# LED-plus-SHIM.net
KiCad netlist of a schematic drawn in EAGLE
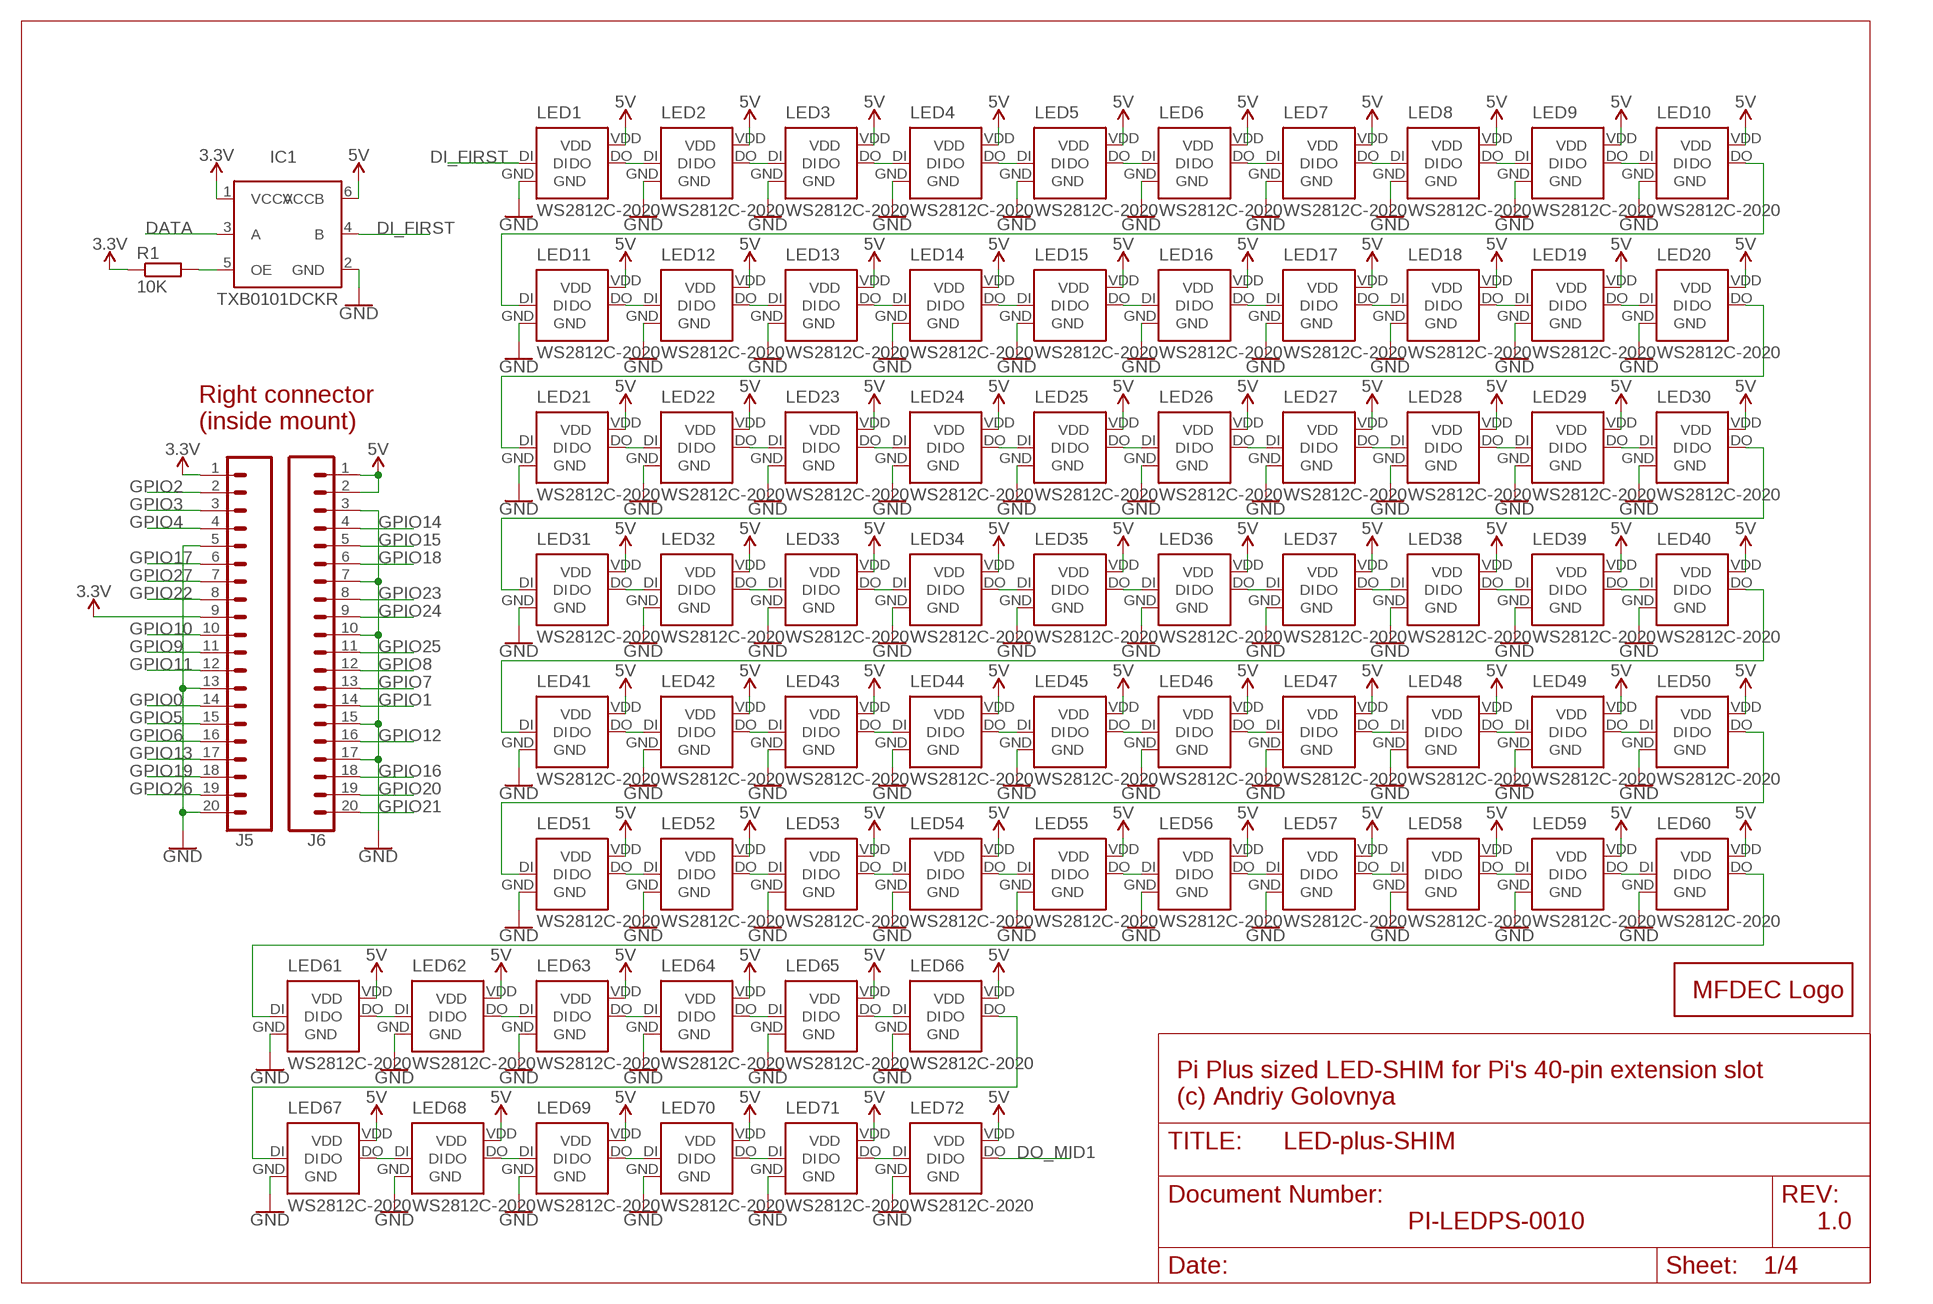
[diagram p0: schematic, sheet 1]
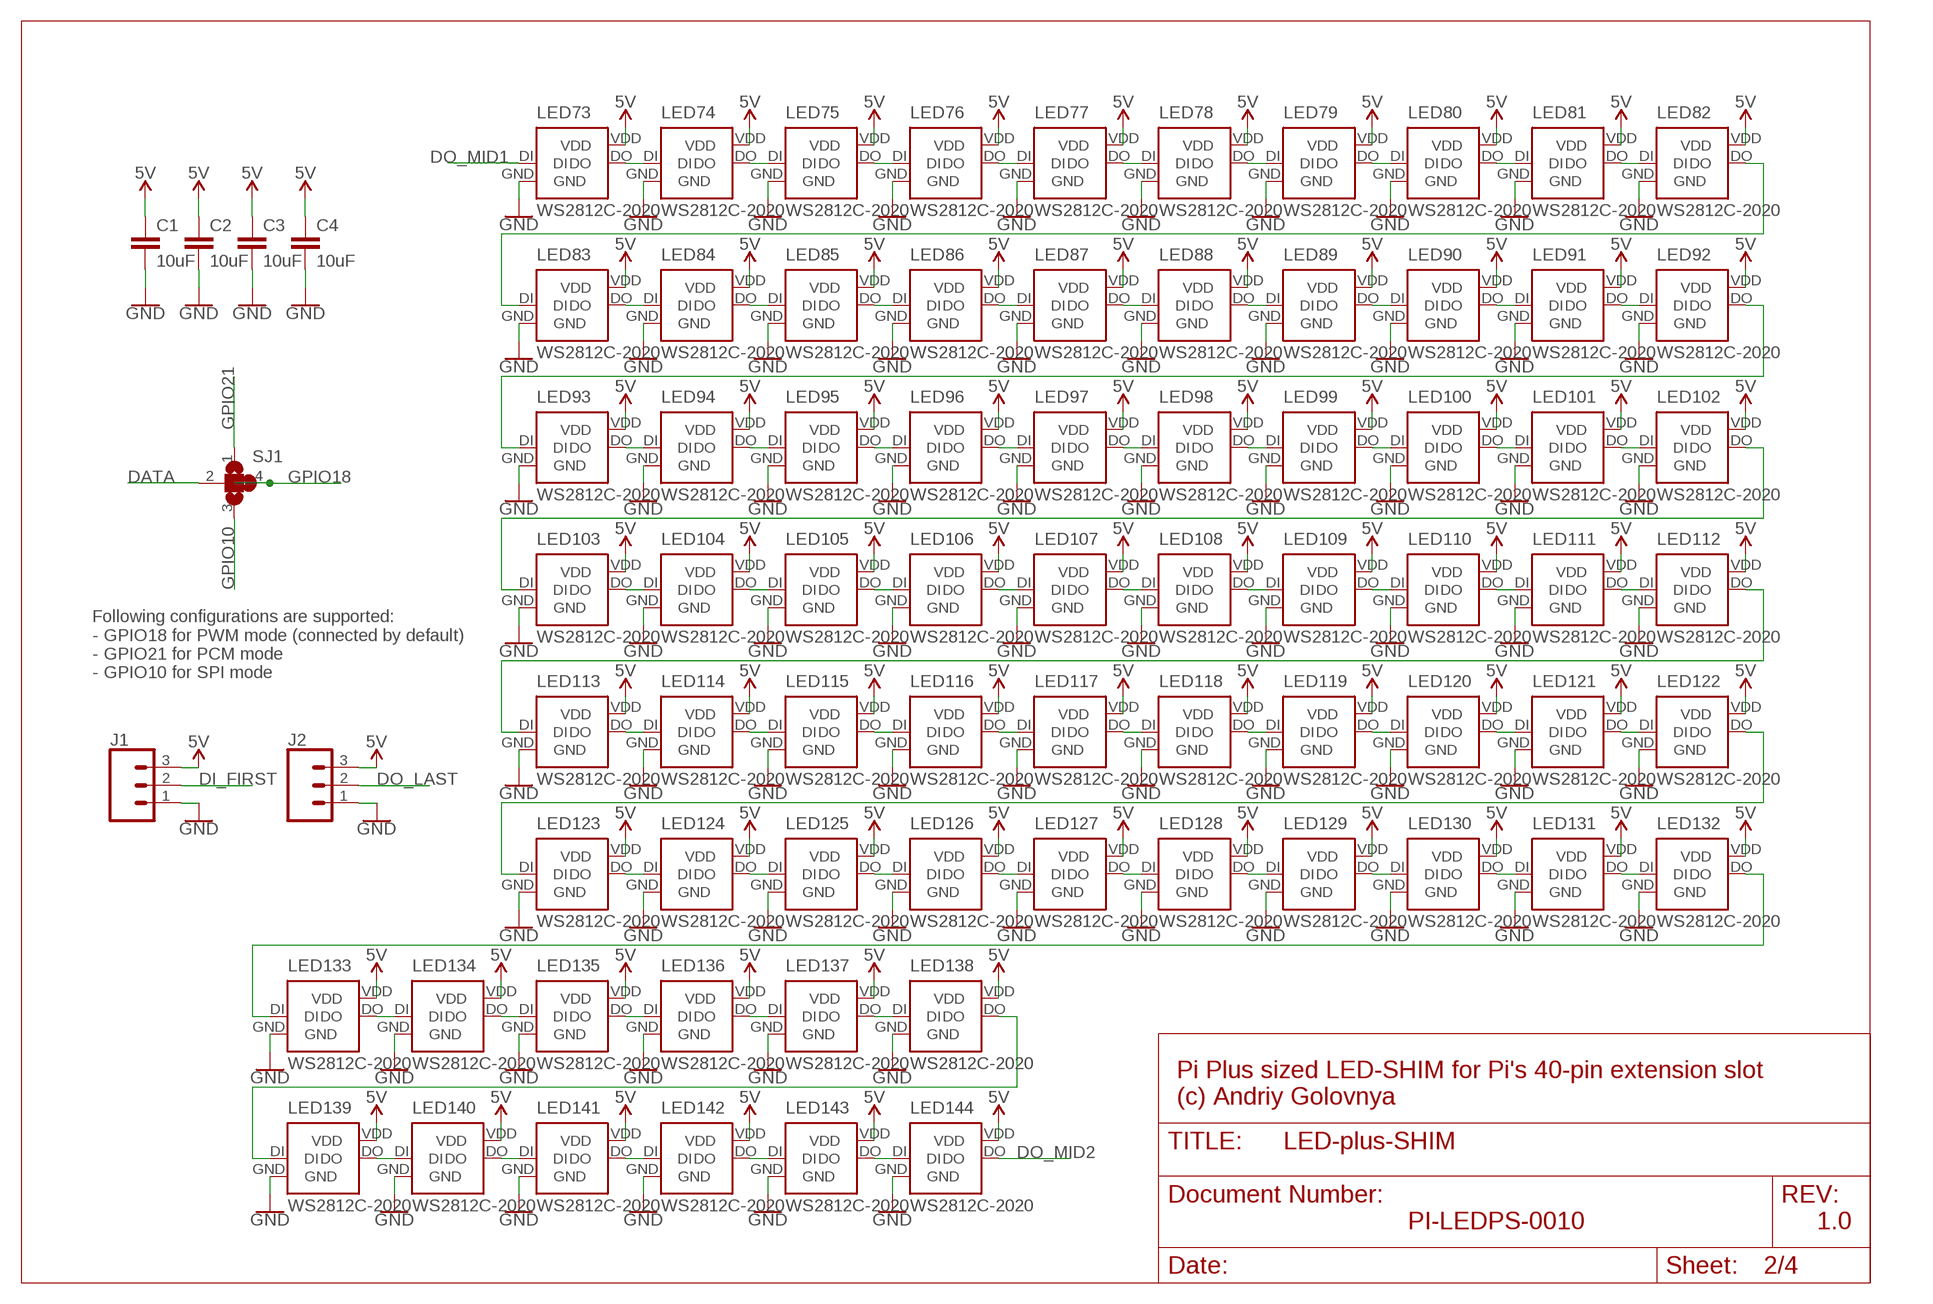
[diagram p1: schematic, sheet 2]
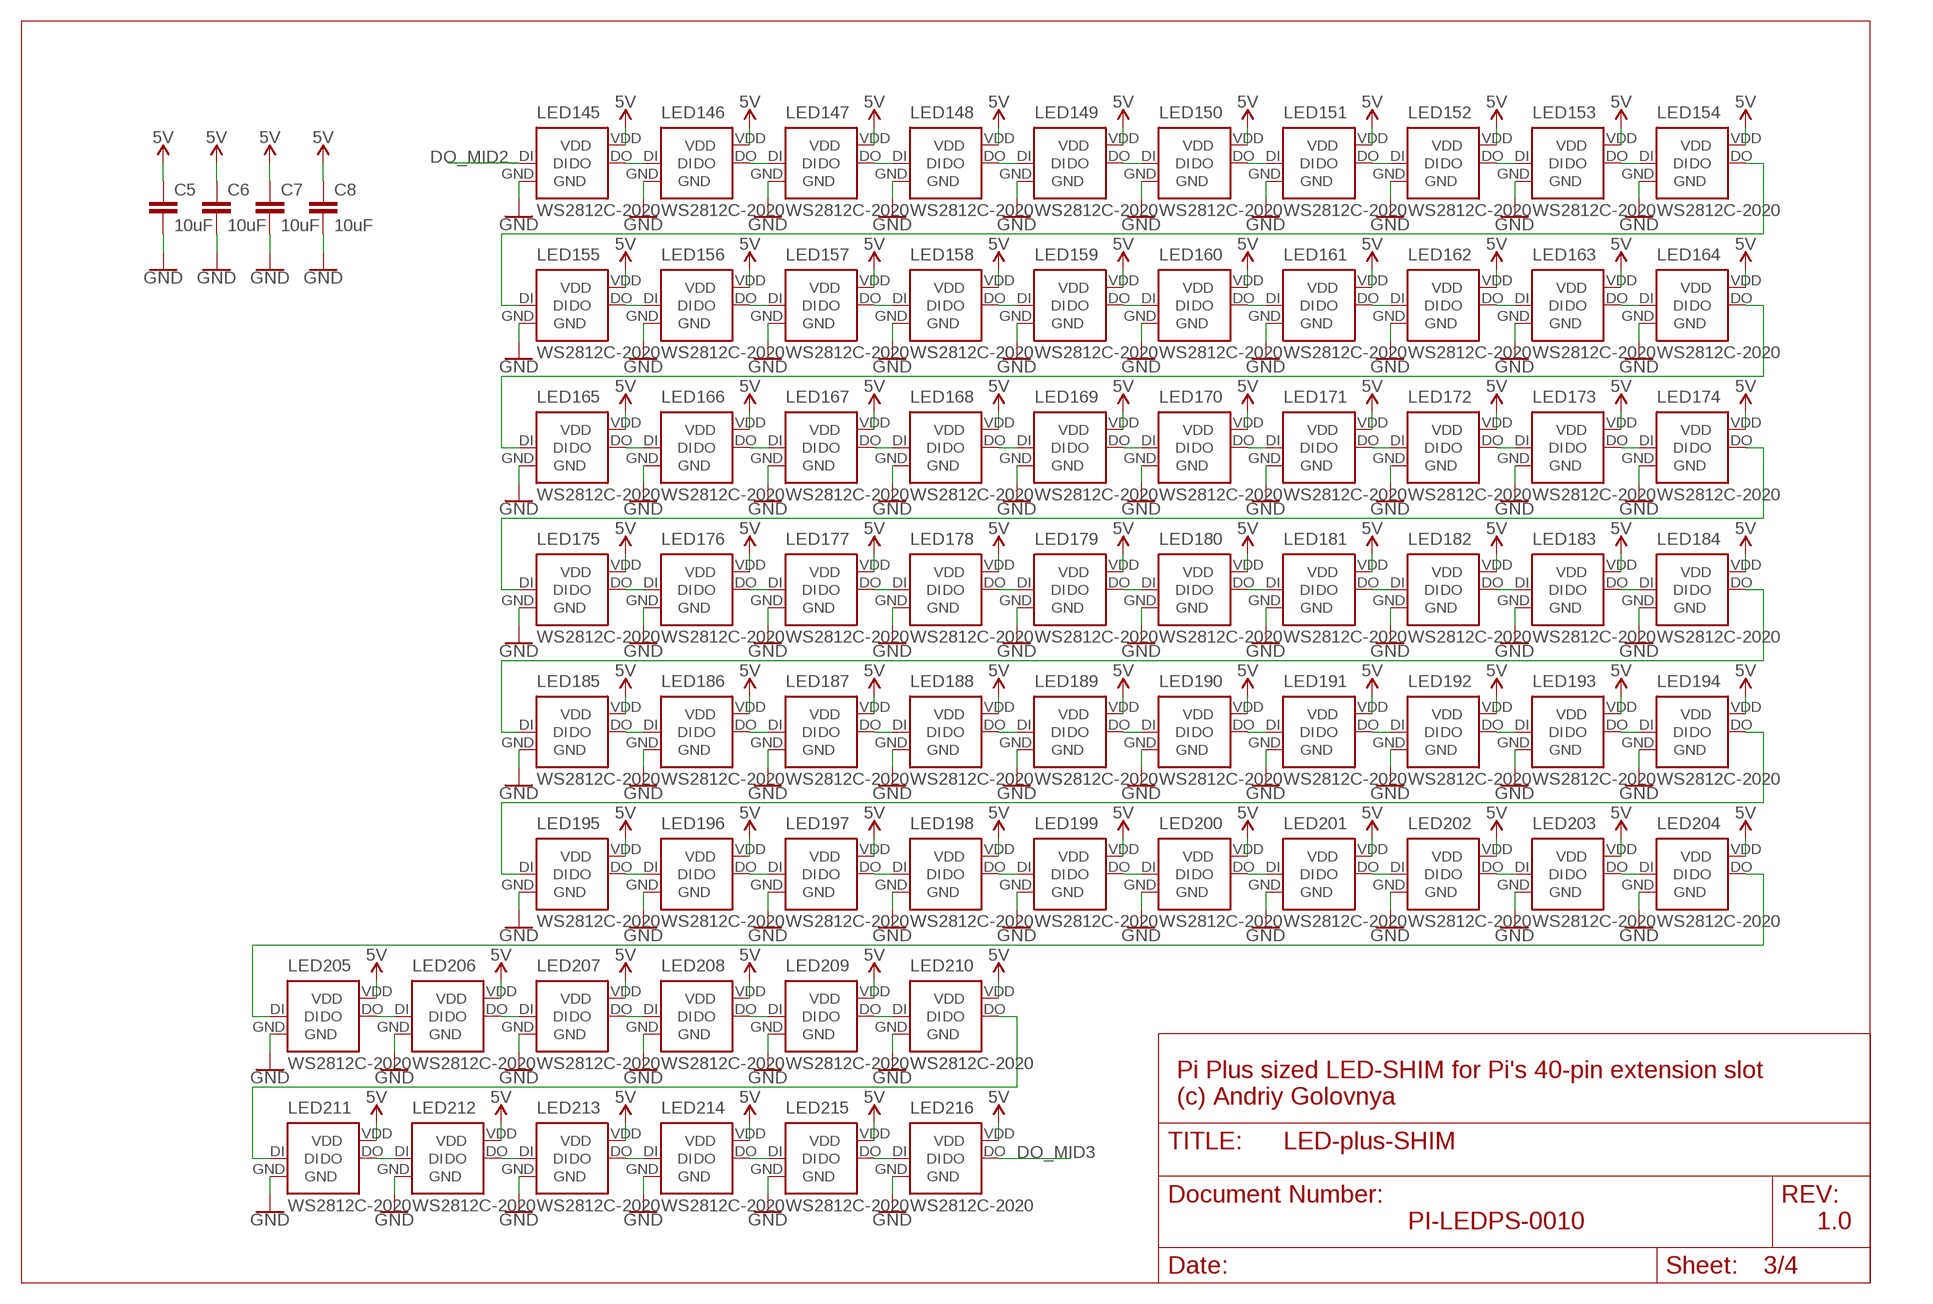
[diagram p2: schematic, sheet 3]
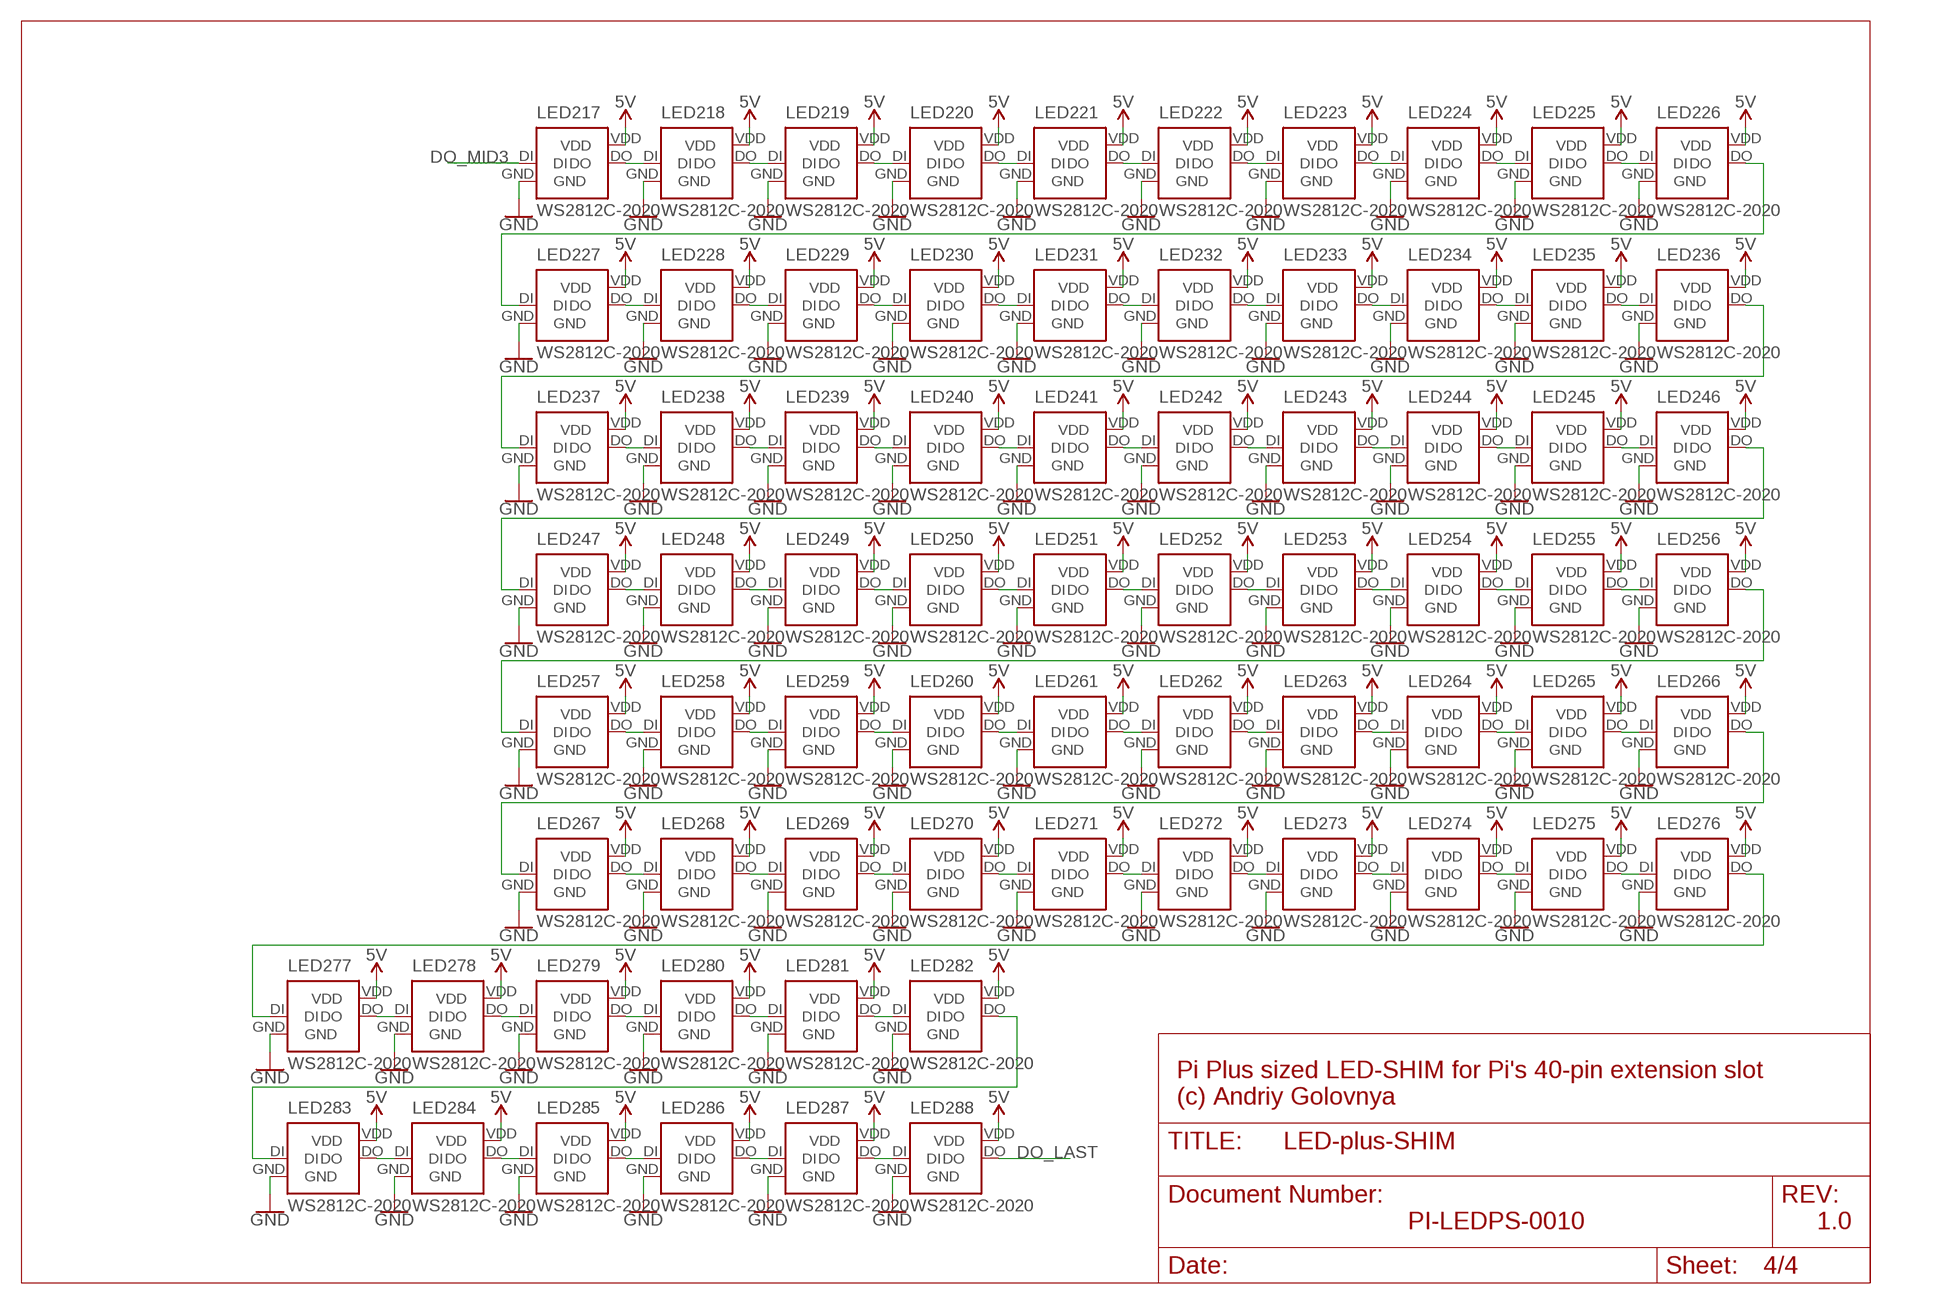
[diagram p3: schematic, sheet 4]

(export (version "E")
  (design (tool "Eeschema 10.0.6"))
  (components
    (comp (ref "IC1")
      (value "TXB0101DCKR")
      (footprint "eagle-import:SOT65P210X110-6N")
      (libsource (lib "eagle-import") (part "TXB0101DCKR"))
    )
    (comp (ref "J5")
      (value "CONN_20LOCK")
      (footprint "eagle-import:1X20_LOCK")
      (libsource (lib "eagle-import") (part "CONN_20LOCK"))
    )
    (comp (ref "J6")
      (value "CONN_20LOCK")
      (footprint "eagle-import:1X20_LOCK")
      (libsource (lib "eagle-import") (part "CONN_20LOCK"))
    )
    (comp (ref "LED1")
      (value "WS2812C-2020")
      (footprint "eagle-import:WS2812X-2020")
      (libsource (lib "eagle-import") (part "WS2812C-2020"))
    )
    (comp (ref "LED2")
      (value "WS2812C-2020")
      (footprint "eagle-import:WS2812X-2020")
      (libsource (lib "eagle-import") (part "WS2812C-2020"))
    )
    (comp (ref "LED3")
      (value "WS2812C-2020")
      (footprint "eagle-import:WS2812X-2020")
      (libsource (lib "eagle-import") (part "WS2812C-2020"))
    )
    (comp (ref "LED4")
      (value "WS2812C-2020")
      (footprint "eagle-import:WS2812X-2020")
      (libsource (lib "eagle-import") (part "WS2812C-2020"))
    )
    (comp (ref "LED5")
      (value "WS2812C-2020")
      (footprint "eagle-import:WS2812X-2020")
      (libsource (lib "eagle-import") (part "WS2812C-2020"))
    )
    (comp (ref "LED6")
      (value "WS2812C-2020")
      (footprint "eagle-import:WS2812X-2020")
      (libsource (lib "eagle-import") (part "WS2812C-2020"))
    )
    (comp (ref "LED7")
      (value "WS2812C-2020")
      (footprint "eagle-import:WS2812X-2020")
      (libsource (lib "eagle-import") (part "WS2812C-2020"))
    )
    (comp (ref "LED8")
      (value "WS2812C-2020")
      (footprint "eagle-import:WS2812X-2020")
      (libsource (lib "eagle-import") (part "WS2812C-2020"))
    )
    (comp (ref "LED9")
      (value "WS2812C-2020")
      (footprint "eagle-import:WS2812X-2020")
      (libsource (lib "eagle-import") (part "WS2812C-2020"))
    )
    (comp (ref "LED10")
      (value "WS2812C-2020")
      (footprint "eagle-import:WS2812X-2020")
      (libsource (lib "eagle-import") (part "WS2812C-2020"))
    )
    (comp (ref "LED11")
      (value "WS2812C-2020")
      (footprint "eagle-import:WS2812X-2020")
      (libsource (lib "eagle-import") (part "WS2812C-2020"))
    )
    (comp (ref "LED12")
      (value "WS2812C-2020")
      (footprint "eagle-import:WS2812X-2020")
      (libsource (lib "eagle-import") (part "WS2812C-2020"))
    )
    (comp (ref "LED13")
      (value "WS2812C-2020")
      (footprint "eagle-import:WS2812X-2020")
      (libsource (lib "eagle-import") (part "WS2812C-2020"))
    )
    (comp (ref "LED14")
      (value "WS2812C-2020")
      (footprint "eagle-import:WS2812X-2020")
      (libsource (lib "eagle-import") (part "WS2812C-2020"))
    )
    (comp (ref "LED15")
      (value "WS2812C-2020")
      (footprint "eagle-import:WS2812X-2020")
      (libsource (lib "eagle-import") (part "WS2812C-2020"))
    )
    (comp (ref "LED16")
      (value "WS2812C-2020")
      (footprint "eagle-import:WS2812X-2020")
      (libsource (lib "eagle-import") (part "WS2812C-2020"))
    )
    (comp (ref "LED17")
      (value "WS2812C-2020")
      (footprint "eagle-import:WS2812X-2020")
      (libsource (lib "eagle-import") (part "WS2812C-2020"))
    )
    (comp (ref "LED18")
      (value "WS2812C-2020")
      (footprint "eagle-import:WS2812X-2020")
      (libsource (lib "eagle-import") (part "WS2812C-2020"))
    )
    (comp (ref "LED19")
      (value "WS2812C-2020")
      (footprint "eagle-import:WS2812X-2020")
      (libsource (lib "eagle-import") (part "WS2812C-2020"))
    )
    (comp (ref "LED20")
      (value "WS2812C-2020")
      (footprint "eagle-import:WS2812X-2020")
      (libsource (lib "eagle-import") (part "WS2812C-2020"))
    )
    (comp (ref "LED21")
      (value "WS2812C-2020")
      (footprint "eagle-import:WS2812X-2020")
      (libsource (lib "eagle-import") (part "WS2812C-2020"))
    )
    (comp (ref "LED22")
      (value "WS2812C-2020")
      (footprint "eagle-import:WS2812X-2020")
      (libsource (lib "eagle-import") (part "WS2812C-2020"))
    )
    (comp (ref "LED23")
      (value "WS2812C-2020")
      (footprint "eagle-import:WS2812X-2020")
      (libsource (lib "eagle-import") (part "WS2812C-2020"))
    )
    (comp (ref "LED24")
      (value "WS2812C-2020")
      (footprint "eagle-import:WS2812X-2020")
      (libsource (lib "eagle-import") (part "WS2812C-2020"))
    )
    (comp (ref "LED25")
      (value "WS2812C-2020")
      (footprint "eagle-import:WS2812X-2020")
      (libsource (lib "eagle-import") (part "WS2812C-2020"))
    )
    (comp (ref "LED26")
      (value "WS2812C-2020")
      (footprint "eagle-import:WS2812X-2020")
      (libsource (lib "eagle-import") (part "WS2812C-2020"))
    )
    (comp (ref "LED27")
      (value "WS2812C-2020")
      (footprint "eagle-import:WS2812X-2020")
      (libsource (lib "eagle-import") (part "WS2812C-2020"))
    )
    (comp (ref "LED28")
      (value "WS2812C-2020")
      (footprint "eagle-import:WS2812X-2020")
      (libsource (lib "eagle-import") (part "WS2812C-2020"))
    )
    (comp (ref "LED29")
      (value "WS2812C-2020")
      (footprint "eagle-import:WS2812X-2020")
      (libsource (lib "eagle-import") (part "WS2812C-2020"))
    )
    (comp (ref "LED30")
      (value "WS2812C-2020")
      (footprint "eagle-import:WS2812X-2020")
      (libsource (lib "eagle-import") (part "WS2812C-2020"))
    )
    (comp (ref "LED31")
      (value "WS2812C-2020")
      (footprint "eagle-import:WS2812X-2020")
      (libsource (lib "eagle-import") (part "WS2812C-2020"))
    )
    (comp (ref "LED32")
      (value "WS2812C-2020")
      (footprint "eagle-import:WS2812X-2020")
      (libsource (lib "eagle-import") (part "WS2812C-2020"))
    )
    (comp (ref "LED33")
      (value "WS2812C-2020")
      (footprint "eagle-import:WS2812X-2020")
      (libsource (lib "eagle-import") (part "WS2812C-2020"))
    )
    (comp (ref "LED34")
      (value "WS2812C-2020")
      (footprint "eagle-import:WS2812X-2020")
      (libsource (lib "eagle-import") (part "WS2812C-2020"))
    )
    (comp (ref "LED35")
      (value "WS2812C-2020")
      (footprint "eagle-import:WS2812X-2020")
      (libsource (lib "eagle-import") (part "WS2812C-2020"))
    )
    (comp (ref "LED36")
      (value "WS2812C-2020")
      (footprint "eagle-import:WS2812X-2020")
      (libsource (lib "eagle-import") (part "WS2812C-2020"))
    )
    (comp (ref "LED37")
      (value "WS2812C-2020")
      (footprint "eagle-import:WS2812X-2020")
      (libsource (lib "eagle-import") (part "WS2812C-2020"))
    )
    (comp (ref "LED38")
      (value "WS2812C-2020")
      (footprint "eagle-import:WS2812X-2020")
      (libsource (lib "eagle-import") (part "WS2812C-2020"))
    )
    (comp (ref "LED39")
      (value "WS2812C-2020")
      (footprint "eagle-import:WS2812X-2020")
      (libsource (lib "eagle-import") (part "WS2812C-2020"))
    )
    (comp (ref "LED40")
      (value "WS2812C-2020")
      (footprint "eagle-import:WS2812X-2020")
      (libsource (lib "eagle-import") (part "WS2812C-2020"))
    )
    (comp (ref "LED41")
      (value "WS2812C-2020")
      (footprint "eagle-import:WS2812X-2020")
      (libsource (lib "eagle-import") (part "WS2812C-2020"))
    )
    (comp (ref "LED42")
      (value "WS2812C-2020")
      (footprint "eagle-import:WS2812X-2020")
      (libsource (lib "eagle-import") (part "WS2812C-2020"))
    )
    (comp (ref "LED43")
      (value "WS2812C-2020")
      (footprint "eagle-import:WS2812X-2020")
      (libsource (lib "eagle-import") (part "WS2812C-2020"))
    )
    (comp (ref "LED44")
      (value "WS2812C-2020")
      (footprint "eagle-import:WS2812X-2020")
      (libsource (lib "eagle-import") (part "WS2812C-2020"))
    )
    (comp (ref "LED45")
      (value "WS2812C-2020")
      (footprint "eagle-import:WS2812X-2020")
      (libsource (lib "eagle-import") (part "WS2812C-2020"))
    )
    (comp (ref "LED46")
      (value "WS2812C-2020")
      (footprint "eagle-import:WS2812X-2020")
      (libsource (lib "eagle-import") (part "WS2812C-2020"))
    )
    (comp (ref "LED47")
      (value "WS2812C-2020")
      (footprint "eagle-import:WS2812X-2020")
      (libsource (lib "eagle-import") (part "WS2812C-2020"))
    )
    (comp (ref "LED48")
      (value "WS2812C-2020")
      (footprint "eagle-import:WS2812X-2020")
      (libsource (lib "eagle-import") (part "WS2812C-2020"))
    )
    (comp (ref "LED49")
      (value "WS2812C-2020")
      (footprint "eagle-import:WS2812X-2020")
      (libsource (lib "eagle-import") (part "WS2812C-2020"))
    )
    (comp (ref "LED50")
      (value "WS2812C-2020")
      (footprint "eagle-import:WS2812X-2020")
      (libsource (lib "eagle-import") (part "WS2812C-2020"))
    )
    (comp (ref "LED51")
      (value "WS2812C-2020")
      (footprint "eagle-import:WS2812X-2020")
      (libsource (lib "eagle-import") (part "WS2812C-2020"))
    )
    (comp (ref "LED52")
      (value "WS2812C-2020")
      (footprint "eagle-import:WS2812X-2020")
      (libsource (lib "eagle-import") (part "WS2812C-2020"))
    )
    (comp (ref "LED53")
      (value "WS2812C-2020")
      (footprint "eagle-import:WS2812X-2020")
      (libsource (lib "eagle-import") (part "WS2812C-2020"))
    )
    (comp (ref "LED54")
      (value "WS2812C-2020")
      (footprint "eagle-import:WS2812X-2020")
      (libsource (lib "eagle-import") (part "WS2812C-2020"))
    )
    (comp (ref "LED55")
      (value "WS2812C-2020")
      (footprint "eagle-import:WS2812X-2020")
      (libsource (lib "eagle-import") (part "WS2812C-2020"))
    )
    (comp (ref "LED56")
      (value "WS2812C-2020")
      (footprint "eagle-import:WS2812X-2020")
      (libsource (lib "eagle-import") (part "WS2812C-2020"))
    )
    (comp (ref "LED57")
      (value "WS2812C-2020")
      (footprint "eagle-import:WS2812X-2020")
      (libsource (lib "eagle-import") (part "WS2812C-2020"))
    )
    (comp (ref "LED58")
      (value "WS2812C-2020")
      (footprint "eagle-import:WS2812X-2020")
      (libsource (lib "eagle-import") (part "WS2812C-2020"))
    )
    (comp (ref "LED59")
      (value "WS2812C-2020")
      (footprint "eagle-import:WS2812X-2020")
      (libsource (lib "eagle-import") (part "WS2812C-2020"))
    )
    (comp (ref "LED60")
      (value "WS2812C-2020")
      (footprint "eagle-import:WS2812X-2020")
      (libsource (lib "eagle-import") (part "WS2812C-2020"))
    )
    (comp (ref "LED61")
      (value "WS2812C-2020")
      (footprint "eagle-import:WS2812X-2020")
      (libsource (lib "eagle-import") (part "WS2812C-2020"))
    )
    (comp (ref "LED62")
      (value "WS2812C-2020")
      (footprint "eagle-import:WS2812X-2020")
      (libsource (lib "eagle-import") (part "WS2812C-2020"))
    )
    (comp (ref "LED63")
      (value "WS2812C-2020")
      (footprint "eagle-import:WS2812X-2020")
      (libsource (lib "eagle-import") (part "WS2812C-2020"))
    )
    (comp (ref "LED64")
      (value "WS2812C-2020")
      (footprint "eagle-import:WS2812X-2020")
      (libsource (lib "eagle-import") (part "WS2812C-2020"))
    )
    (comp (ref "LED65")
      (value "WS2812C-2020")
      (footprint "eagle-import:WS2812X-2020")
      (libsource (lib "eagle-import") (part "WS2812C-2020"))
    )
    (comp (ref "LED66")
      (value "WS2812C-2020")
      (footprint "eagle-import:WS2812X-2020")
      (libsource (lib "eagle-import") (part "WS2812C-2020"))
    )
    (comp (ref "LED67")
      (value "WS2812C-2020")
      (footprint "eagle-import:WS2812X-2020")
      (libsource (lib "eagle-import") (part "WS2812C-2020"))
    )
    (comp (ref "LED68")
      (value "WS2812C-2020")
      (footprint "eagle-import:WS2812X-2020")
      (libsource (lib "eagle-import") (part "WS2812C-2020"))
    )
    (comp (ref "LED69")
      (value "WS2812C-2020")
      (footprint "eagle-import:WS2812X-2020")
      (libsource (lib "eagle-import") (part "WS2812C-2020"))
    )
    (comp (ref "LED70")
      (value "WS2812C-2020")
      (footprint "eagle-import:WS2812X-2020")
      (libsource (lib "eagle-import") (part "WS2812C-2020"))
    )
    (comp (ref "LED71")
      (value "WS2812C-2020")
      (footprint "eagle-import:WS2812X-2020")
      (libsource (lib "eagle-import") (part "WS2812C-2020"))
    )
    (comp (ref "LED72")
      (value "WS2812C-2020")
      (footprint "eagle-import:WS2812X-2020")
      (libsource (lib "eagle-import") (part "WS2812C-2020"))
    )
    (comp (ref "LOGO1")
      (value "MFDECLOGO_L_30MM")
      (footprint "eagle-import:MFDEC_L_30MM")
      (libsource (lib "eagle-import") (part "MFDECLOGO_L_30MM"))
    )
    (comp (ref "R1")
      (value "10K")
      (footprint "eagle-import:R0402")
      (libsource (lib "eagle-import") (part "R-EU_R0402"))
    )
    (comp (ref "C1")
      (value "10uF")
      (footprint "eagle-import:C0805")
      (libsource (lib "eagle-import") (part "C-EUC0805"))
    )
    (comp (ref "C2")
      (value "10uF")
      (footprint "eagle-import:C0805")
      (libsource (lib "eagle-import") (part "C-EUC0805"))
    )
    (comp (ref "C3")
      (value "10uF")
      (footprint "eagle-import:C0805")
      (libsource (lib "eagle-import") (part "C-EUC0805"))
    )
    (comp (ref "C4")
      (value "10uF")
      (footprint "eagle-import:C0805")
      (libsource (lib "eagle-import") (part "C-EUC0805"))
    )
    (comp (ref "J1")
      (value "CONN_03")
      (footprint "eagle-import:1X03")
      (libsource (lib "eagle-import") (part "CONN_03"))
    )
    (comp (ref "J2")
      (value "CONN_03")
      (footprint "eagle-import:1X03")
      (libsource (lib "eagle-import") (part "CONN_03"))
    )
    (comp (ref "LED73")
      (value "WS2812C-2020")
      (footprint "eagle-import:WS2812X-2020")
      (libsource (lib "eagle-import") (part "WS2812C-2020"))
    )
    (comp (ref "LED74")
      (value "WS2812C-2020")
      (footprint "eagle-import:WS2812X-2020")
      (libsource (lib "eagle-import") (part "WS2812C-2020"))
    )
    (comp (ref "LED75")
      (value "WS2812C-2020")
      (footprint "eagle-import:WS2812X-2020")
      (libsource (lib "eagle-import") (part "WS2812C-2020"))
    )
    (comp (ref "LED76")
      (value "WS2812C-2020")
      (footprint "eagle-import:WS2812X-2020")
      (libsource (lib "eagle-import") (part "WS2812C-2020"))
    )
    (comp (ref "LED77")
      (value "WS2812C-2020")
      (footprint "eagle-import:WS2812X-2020")
      (libsource (lib "eagle-import") (part "WS2812C-2020"))
    )
    (comp (ref "LED78")
      (value "WS2812C-2020")
      (footprint "eagle-import:WS2812X-2020")
      (libsource (lib "eagle-import") (part "WS2812C-2020"))
    )
    (comp (ref "LED79")
      (value "WS2812C-2020")
      (footprint "eagle-import:WS2812X-2020")
      (libsource (lib "eagle-import") (part "WS2812C-2020"))
    )
    (comp (ref "LED80")
      (value "WS2812C-2020")
      (footprint "eagle-import:WS2812X-2020")
      (libsource (lib "eagle-import") (part "WS2812C-2020"))
    )
    (comp (ref "LED81")
      (value "WS2812C-2020")
      (footprint "eagle-import:WS2812X-2020")
      (libsource (lib "eagle-import") (part "WS2812C-2020"))
    )
    (comp (ref "LED82")
      (value "WS2812C-2020")
      (footprint "eagle-import:WS2812X-2020")
      (libsource (lib "eagle-import") (part "WS2812C-2020"))
    )
    (comp (ref "LED83")
      (value "WS2812C-2020")
      (footprint "eagle-import:WS2812X-2020")
      (libsource (lib "eagle-import") (part "WS2812C-2020"))
    )
    (comp (ref "LED84")
      (value "WS2812C-2020")
      (footprint "eagle-import:WS2812X-2020")
      (libsource (lib "eagle-import") (part "WS2812C-2020"))
    )
    (comp (ref "LED85")
      (value "WS2812C-2020")
      (footprint "eagle-import:WS2812X-2020")
      (libsource (lib "eagle-import") (part "WS2812C-2020"))
    )
    (comp (ref "LED86")
      (value "WS2812C-2020")
      (footprint "eagle-import:WS2812X-2020")
      (libsource (lib "eagle-import") (part "WS2812C-2020"))
    )
    (comp (ref "LED87")
      (value "WS2812C-2020")
      (footprint "eagle-import:WS2812X-2020")
      (libsource (lib "eagle-import") (part "WS2812C-2020"))
    )
    (comp (ref "LED88")
      (value "WS2812C-2020")
      (footprint "eagle-import:WS2812X-2020")
      (libsource (lib "eagle-import") (part "WS2812C-2020"))
    )
    (comp (ref "LED89")
      (value "WS2812C-2020")
      (footprint "eagle-import:WS2812X-2020")
      (libsource (lib "eagle-import") (part "WS2812C-2020"))
    )
    (comp (ref "LED90")
      (value "WS2812C-2020")
      (footprint "eagle-import:WS2812X-2020")
      (libsource (lib "eagle-import") (part "WS2812C-2020"))
    )
    (comp (ref "LED91")
      (value "WS2812C-2020")
      (footprint "eagle-import:WS2812X-2020")
      (libsource (lib "eagle-import") (part "WS2812C-2020"))
    )
    (comp (ref "LED92")
      (value "WS2812C-2020")
      (footprint "eagle-import:WS2812X-2020")
      (libsource (lib "eagle-import") (part "WS2812C-2020"))
    )
    (comp (ref "LED93")
      (value "WS2812C-2020")
      (footprint "eagle-import:WS2812X-2020")
      (libsource (lib "eagle-import") (part "WS2812C-2020"))
    )
    (comp (ref "LED94")
      (value "WS2812C-2020")
      (footprint "eagle-import:WS2812X-2020")
      (libsource (lib "eagle-import") (part "WS2812C-2020"))
    )
    (comp (ref "LED95")
      (value "WS2812C-2020")
      (footprint "eagle-import:WS2812X-2020")
      (libsource (lib "eagle-import") (part "WS2812C-2020"))
    )
    (comp (ref "LED96")
      (value "WS2812C-2020")
      (footprint "eagle-import:WS2812X-2020")
      (libsource (lib "eagle-import") (part "WS2812C-2020"))
    )
    (comp (ref "LED97")
      (value "WS2812C-2020")
      (footprint "eagle-import:WS2812X-2020")
      (libsource (lib "eagle-import") (part "WS2812C-2020"))
    )
    (comp (ref "LED98")
      (value "WS2812C-2020")
      (footprint "eagle-import:WS2812X-2020")
      (libsource (lib "eagle-import") (part "WS2812C-2020"))
    )
    (comp (ref "LED99")
      (value "WS2812C-2020")
      (footprint "eagle-import:WS2812X-2020")
      (libsource (lib "eagle-import") (part "WS2812C-2020"))
    )
    (comp (ref "LED100")
      (value "WS2812C-2020")
      (footprint "eagle-import:WS2812X-2020")
      (libsource (lib "eagle-import") (part "WS2812C-2020"))
    )
    (comp (ref "LED101")
      (value "WS2812C-2020")
      (footprint "eagle-import:WS2812X-2020")
      (libsource (lib "eagle-import") (part "WS2812C-2020"))
    )
    (comp (ref "LED102")
      (value "WS2812C-2020")
      (footprint "eagle-import:WS2812X-2020")
      (libsource (lib "eagle-import") (part "WS2812C-2020"))
    )
    (comp (ref "LED103")
      (value "WS2812C-2020")
      (footprint "eagle-import:WS2812X-2020")
      (libsource (lib "eagle-import") (part "WS2812C-2020"))
    )
    (comp (ref "LED104")
      (value "WS2812C-2020")
      (footprint "eagle-import:WS2812X-2020")
      (libsource (lib "eagle-import") (part "WS2812C-2020"))
    )
    (comp (ref "LED105")
      (value "WS2812C-2020")
      (footprint "eagle-import:WS2812X-2020")
      (libsource (lib "eagle-import") (part "WS2812C-2020"))
    )
    (comp (ref "LED106")
      (value "WS2812C-2020")
      (footprint "eagle-import:WS2812X-2020")
      (libsource (lib "eagle-import") (part "WS2812C-2020"))
    )
    (comp (ref "LED107")
      (value "WS2812C-2020")
      (footprint "eagle-import:WS2812X-2020")
      (libsource (lib "eagle-import") (part "WS2812C-2020"))
    )
    (comp (ref "LED108")
      (value "WS2812C-2020")
      (footprint "eagle-import:WS2812X-2020")
      (libsource (lib "eagle-import") (part "WS2812C-2020"))
    )
    (comp (ref "LED109")
      (value "WS2812C-2020")
      (footprint "eagle-import:WS2812X-2020")
      (libsource (lib "eagle-import") (part "WS2812C-2020"))
    )
    (comp (ref "LED110")
      (value "WS2812C-2020")
      (footprint "eagle-import:WS2812X-2020")
      (libsource (lib "eagle-import") (part "WS2812C-2020"))
    )
    (comp (ref "LED111")
      (value "WS2812C-2020")
      (footprint "eagle-import:WS2812X-2020")
      (libsource (lib "eagle-import") (part "WS2812C-2020"))
    )
    (comp (ref "LED112")
      (value "WS2812C-2020")
      (footprint "eagle-import:WS2812X-2020")
      (libsource (lib "eagle-import") (part "WS2812C-2020"))
    )
    (comp (ref "LED113")
      (value "WS2812C-2020")
      (footprint "eagle-import:WS2812X-2020")
      (libsource (lib "eagle-import") (part "WS2812C-2020"))
    )
    (comp (ref "LED114")
      (value "WS2812C-2020")
      (footprint "eagle-import:WS2812X-2020")
      (libsource (lib "eagle-import") (part "WS2812C-2020"))
    )
    (comp (ref "LED115")
      (value "WS2812C-2020")
      (footprint "eagle-import:WS2812X-2020")
      (libsource (lib "eagle-import") (part "WS2812C-2020"))
    )
    (comp (ref "LED116")
      (value "WS2812C-2020")
      (footprint "eagle-import:WS2812X-2020")
      (libsource (lib "eagle-import") (part "WS2812C-2020"))
    )
    (comp (ref "LED117")
      (value "WS2812C-2020")
      (footprint "eagle-import:WS2812X-2020")
      (libsource (lib "eagle-import") (part "WS2812C-2020"))
    )
    (comp (ref "LED118")
      (value "WS2812C-2020")
      (footprint "eagle-import:WS2812X-2020")
      (libsource (lib "eagle-import") (part "WS2812C-2020"))
    )
    (comp (ref "LED119")
      (value "WS2812C-2020")
      (footprint "eagle-import:WS2812X-2020")
      (libsource (lib "eagle-import") (part "WS2812C-2020"))
    )
    (comp (ref "LED120")
      (value "WS2812C-2020")
      (footprint "eagle-import:WS2812X-2020")
      (libsource (lib "eagle-import") (part "WS2812C-2020"))
    )
    (comp (ref "LED121")
      (value "WS2812C-2020")
      (footprint "eagle-import:WS2812X-2020")
      (libsource (lib "eagle-import") (part "WS2812C-2020"))
    )
    (comp (ref "LED122")
      (value "WS2812C-2020")
      (footprint "eagle-import:WS2812X-2020")
      (libsource (lib "eagle-import") (part "WS2812C-2020"))
    )
    (comp (ref "LED123")
      (value "WS2812C-2020")
      (footprint "eagle-import:WS2812X-2020")
      (libsource (lib "eagle-import") (part "WS2812C-2020"))
    )
    (comp (ref "LED124")
      (value "WS2812C-2020")
      (footprint "eagle-import:WS2812X-2020")
      (libsource (lib "eagle-import") (part "WS2812C-2020"))
    )
    (comp (ref "LED125")
      (value "WS2812C-2020")
      (footprint "eagle-import:WS2812X-2020")
      (libsource (lib "eagle-import") (part "WS2812C-2020"))
    )
    (comp (ref "LED126")
      (value "WS2812C-2020")
      (footprint "eagle-import:WS2812X-2020")
      (libsource (lib "eagle-import") (part "WS2812C-2020"))
    )
    (comp (ref "LED127")
      (value "WS2812C-2020")
      (footprint "eagle-import:WS2812X-2020")
      (libsource (lib "eagle-import") (part "WS2812C-2020"))
    )
    (comp (ref "LED128")
      (value "WS2812C-2020")
      (footprint "eagle-import:WS2812X-2020")
      (libsource (lib "eagle-import") (part "WS2812C-2020"))
    )
    (comp (ref "LED129")
      (value "WS2812C-2020")
      (footprint "eagle-import:WS2812X-2020")
      (libsource (lib "eagle-import") (part "WS2812C-2020"))
    )
    (comp (ref "LED130")
      (value "WS2812C-2020")
      (footprint "eagle-import:WS2812X-2020")
      (libsource (lib "eagle-import") (part "WS2812C-2020"))
    )
    (comp (ref "LED131")
      (value "WS2812C-2020")
      (footprint "eagle-import:WS2812X-2020")
      (libsource (lib "eagle-import") (part "WS2812C-2020"))
    )
    (comp (ref "LED132")
      (value "WS2812C-2020")
      (footprint "eagle-import:WS2812X-2020")
      (libsource (lib "eagle-import") (part "WS2812C-2020"))
    )
    (comp (ref "LED133")
      (value "WS2812C-2020")
      (footprint "eagle-import:WS2812X-2020")
      (libsource (lib "eagle-import") (part "WS2812C-2020"))
    )
    (comp (ref "LED134")
      (value "WS2812C-2020")
      (footprint "eagle-import:WS2812X-2020")
      (libsource (lib "eagle-import") (part "WS2812C-2020"))
    )
    (comp (ref "LED135")
      (value "WS2812C-2020")
      (footprint "eagle-import:WS2812X-2020")
      (libsource (lib "eagle-import") (part "WS2812C-2020"))
    )
    (comp (ref "LED136")
      (value "WS2812C-2020")
      (footprint "eagle-import:WS2812X-2020")
      (libsource (lib "eagle-import") (part "WS2812C-2020"))
    )
    (comp (ref "LED137")
      (value "WS2812C-2020")
      (footprint "eagle-import:WS2812X-2020")
      (libsource (lib "eagle-import") (part "WS2812C-2020"))
    )
    (comp (ref "LED138")
      (value "WS2812C-2020")
      (footprint "eagle-import:WS2812X-2020")
      (libsource (lib "eagle-import") (part "WS2812C-2020"))
    )
    (comp (ref "LED139")
      (value "WS2812C-2020")
      (footprint "eagle-import:WS2812X-2020")
      (libsource (lib "eagle-import") (part "WS2812C-2020"))
    )
    (comp (ref "LED140")
      (value "WS2812C-2020")
      (footprint "eagle-import:WS2812X-2020")
      (libsource (lib "eagle-import") (part "WS2812C-2020"))
    )
    (comp (ref "LED141")
      (value "WS2812C-2020")
      (footprint "eagle-import:WS2812X-2020")
      (libsource (lib "eagle-import") (part "WS2812C-2020"))
    )
    (comp (ref "LED142")
      (value "WS2812C-2020")
      (footprint "eagle-import:WS2812X-2020")
      (libsource (lib "eagle-import") (part "WS2812C-2020"))
    )
    (comp (ref "LED143")
      (value "WS2812C-2020")
      (footprint "eagle-import:WS2812X-2020")
      (libsource (lib "eagle-import") (part "WS2812C-2020"))
    )
    (comp (ref "LED144")
      (value "WS2812C-2020")
      (footprint "eagle-import:WS2812X-2020")
      (libsource (lib "eagle-import") (part "WS2812C-2020"))
    )
    (comp (ref "SJ1")
      (value "SJ3")
      (footprint "eagle-import:SJ_3")
      (libsource (lib "eagle-import") (part "SJ3"))
    )
    (comp (ref "C5")
      (value "10uF")
      (footprint "eagle-import:C0805")
      (libsource (lib "eagle-import") (part "C-EUC0805"))
    )
    (comp (ref "C6")
      (value "10uF")
      (footprint "eagle-import:C0805")
      (libsource (lib "eagle-import") (part "C-EUC0805"))
    )
    (comp (ref "C7")
      (value "10uF")
      (footprint "eagle-import:C0805")
      (libsource (lib "eagle-import") (part "C-EUC0805"))
    )
    (comp (ref "C8")
      (value "10uF")
      (footprint "eagle-import:C0805")
      (libsource (lib "eagle-import") (part "C-EUC0805"))
    )
    (comp (ref "LED145")
      (value "WS2812C-2020")
      (footprint "eagle-import:WS2812X-2020")
      (libsource (lib "eagle-import") (part "WS2812C-2020"))
    )
    (comp (ref "LED146")
      (value "WS2812C-2020")
      (footprint "eagle-import:WS2812X-2020")
      (libsource (lib "eagle-import") (part "WS2812C-2020"))
    )
    (comp (ref "LED147")
      (value "WS2812C-2020")
      (footprint "eagle-import:WS2812X-2020")
      (libsource (lib "eagle-import") (part "WS2812C-2020"))
    )
    (comp (ref "LED148")
      (value "WS2812C-2020")
      (footprint "eagle-import:WS2812X-2020")
      (libsource (lib "eagle-import") (part "WS2812C-2020"))
    )
    (comp (ref "LED149")
      (value "WS2812C-2020")
      (footprint "eagle-import:WS2812X-2020")
      (libsource (lib "eagle-import") (part "WS2812C-2020"))
    )
    (comp (ref "LED150")
      (value "WS2812C-2020")
      (footprint "eagle-import:WS2812X-2020")
      (libsource (lib "eagle-import") (part "WS2812C-2020"))
    )
    (comp (ref "LED151")
      (value "WS2812C-2020")
      (footprint "eagle-import:WS2812X-2020")
      (libsource (lib "eagle-import") (part "WS2812C-2020"))
    )
    (comp (ref "LED152")
      (value "WS2812C-2020")
      (footprint "eagle-import:WS2812X-2020")
      (libsource (lib "eagle-import") (part "WS2812C-2020"))
    )
    (comp (ref "LED153")
      (value "WS2812C-2020")
      (footprint "eagle-import:WS2812X-2020")
      (libsource (lib "eagle-import") (part "WS2812C-2020"))
    )
    (comp (ref "LED154")
      (value "WS2812C-2020")
      (footprint "eagle-import:WS2812X-2020")
      (libsource (lib "eagle-import") (part "WS2812C-2020"))
    )
    (comp (ref "LED155")
      (value "WS2812C-2020")
      (footprint "eagle-import:WS2812X-2020")
      (libsource (lib "eagle-import") (part "WS2812C-2020"))
    )
    (comp (ref "LED156")
      (value "WS2812C-2020")
      (footprint "eagle-import:WS2812X-2020")
      (libsource (lib "eagle-import") (part "WS2812C-2020"))
    )
    (comp (ref "LED157")
      (value "WS2812C-2020")
      (footprint "eagle-import:WS2812X-2020")
      (libsource (lib "eagle-import") (part "WS2812C-2020"))
    )
    (comp (ref "LED158")
      (value "WS2812C-2020")
      (footprint "eagle-import:WS2812X-2020")
      (libsource (lib "eagle-import") (part "WS2812C-2020"))
    )
    (comp (ref "LED159")
      (value "WS2812C-2020")
      (footprint "eagle-import:WS2812X-2020")
      (libsource (lib "eagle-import") (part "WS2812C-2020"))
    )
    (comp (ref "LED160")
      (value "WS2812C-2020")
      (footprint "eagle-import:WS2812X-2020")
      (libsource (lib "eagle-import") (part "WS2812C-2020"))
    )
    (comp (ref "LED161")
      (value "WS2812C-2020")
      (footprint "eagle-import:WS2812X-2020")
      (libsource (lib "eagle-import") (part "WS2812C-2020"))
    )
    (comp (ref "LED162")
      (value "WS2812C-2020")
      (footprint "eagle-import:WS2812X-2020")
      (libsource (lib "eagle-import") (part "WS2812C-2020"))
    )
    (comp (ref "LED163")
      (value "WS2812C-2020")
      (footprint "eagle-import:WS2812X-2020")
      (libsource (lib "eagle-import") (part "WS2812C-2020"))
    )
    (comp (ref "LED164")
      (value "WS2812C-2020")
      (footprint "eagle-import:WS2812X-2020")
      (libsource (lib "eagle-import") (part "WS2812C-2020"))
    )
    (comp (ref "LED165")
      (value "WS2812C-2020")
      (footprint "eagle-import:WS2812X-2020")
      (libsource (lib "eagle-import") (part "WS2812C-2020"))
    )
    (comp (ref "LED166")
      (value "WS2812C-2020")
      (footprint "eagle-import:WS2812X-2020")
      (libsource (lib "eagle-import") (part "WS2812C-2020"))
    )
    (comp (ref "LED167")
      (value "WS2812C-2020")
      (footprint "eagle-import:WS2812X-2020")
      (libsource (lib "eagle-import") (part "WS2812C-2020"))
    )
    (comp (ref "LED168")
      (value "WS2812C-2020")
      (footprint "eagle-import:WS2812X-2020")
      (libsource (lib "eagle-import") (part "WS2812C-2020"))
    )
    (comp (ref "LED169")
      (value "WS2812C-2020")
      (footprint "eagle-import:WS2812X-2020")
      (libsource (lib "eagle-import") (part "WS2812C-2020"))
    )
    (comp (ref "LED170")
      (value "WS2812C-2020")
      (footprint "eagle-import:WS2812X-2020")
      (libsource (lib "eagle-import") (part "WS2812C-2020"))
    )
    (comp (ref "LED171")
      (value "WS2812C-2020")
      (footprint "eagle-import:WS2812X-2020")
      (libsource (lib "eagle-import") (part "WS2812C-2020"))
    )
    (comp (ref "LED172")
      (value "WS2812C-2020")
      (footprint "eagle-import:WS2812X-2020")
      (libsource (lib "eagle-import") (part "WS2812C-2020"))
    )
    (comp (ref "LED173")
      (value "WS2812C-2020")
      (footprint "eagle-import:WS2812X-2020")
      (libsource (lib "eagle-import") (part "WS2812C-2020"))
    )
    (comp (ref "LED174")
      (value "WS2812C-2020")
      (footprint "eagle-import:WS2812X-2020")
      (libsource (lib "eagle-import") (part "WS2812C-2020"))
    )
    (comp (ref "LED175")
      (value "WS2812C-2020")
      (footprint "eagle-import:WS2812X-2020")
      (libsource (lib "eagle-import") (part "WS2812C-2020"))
    )
    (comp (ref "LED176")
      (value "WS2812C-2020")
      (footprint "eagle-import:WS2812X-2020")
      (libsource (lib "eagle-import") (part "WS2812C-2020"))
    )
    (comp (ref "LED177")
      (value "WS2812C-2020")
      (footprint "eagle-import:WS2812X-2020")
      (libsource (lib "eagle-import") (part "WS2812C-2020"))
    )
    (comp (ref "LED178")
      (value "WS2812C-2020")
      (footprint "eagle-import:WS2812X-2020")
      (libsource (lib "eagle-import") (part "WS2812C-2020"))
    )
    (comp (ref "LED179")
      (value "WS2812C-2020")
      (footprint "eagle-import:WS2812X-2020")
      (libsource (lib "eagle-import") (part "WS2812C-2020"))
    )
    (comp (ref "LED180")
      (value "WS2812C-2020")
      (footprint "eagle-import:WS2812X-2020")
      (libsource (lib "eagle-import") (part "WS2812C-2020"))
    )
    (comp (ref "LED181")
      (value "WS2812C-2020")
      (footprint "eagle-import:WS2812X-2020")
      (libsource (lib "eagle-import") (part "WS2812C-2020"))
    )
    (comp (ref "LED182")
      (value "WS2812C-2020")
      (footprint "eagle-import:WS2812X-2020")
      (libsource (lib "eagle-import") (part "WS2812C-2020"))
    )
    (comp (ref "LED183")
      (value "WS2812C-2020")
      (footprint "eagle-import:WS2812X-2020")
      (libsource (lib "eagle-import") (part "WS2812C-2020"))
    )
    (comp (ref "LED184")
      (value "WS2812C-2020")
      (footprint "eagle-import:WS2812X-2020")
      (libsource (lib "eagle-import") (part "WS2812C-2020"))
    )
    (comp (ref "LED185")
      (value "WS2812C-2020")
      (footprint "eagle-import:WS2812X-2020")
      (libsource (lib "eagle-import") (part "WS2812C-2020"))
    )
    (comp (ref "LED186")
      (value "WS2812C-2020")
      (footprint "eagle-import:WS2812X-2020")
      (libsource (lib "eagle-import") (part "WS2812C-2020"))
    )
    (comp (ref "LED187")
      (value "WS2812C-2020")
      (footprint "eagle-import:WS2812X-2020")
      (libsource (lib "eagle-import") (part "WS2812C-2020"))
    )
    (comp (ref "LED188")
      (value "WS2812C-2020")
      (footprint "eagle-import:WS2812X-2020")
      (libsource (lib "eagle-import") (part "WS2812C-2020"))
    )
    (comp (ref "LED189")
      (value "WS2812C-2020")
      (footprint "eagle-import:WS2812X-2020")
      (libsource (lib "eagle-import") (part "WS2812C-2020"))
    )
    (comp (ref "LED190")
      (value "WS2812C-2020")
      (footprint "eagle-import:WS2812X-2020")
      (libsource (lib "eagle-import") (part "WS2812C-2020"))
    )
    (comp (ref "LED191")
      (value "WS2812C-2020")
      (footprint "eagle-import:WS2812X-2020")
      (libsource (lib "eagle-import") (part "WS2812C-2020"))
    )
    (comp (ref "LED192")
      (value "WS2812C-2020")
      (footprint "eagle-import:WS2812X-2020")
      (libsource (lib "eagle-import") (part "WS2812C-2020"))
    )
    (comp (ref "LED193")
      (value "WS2812C-2020")
      (footprint "eagle-import:WS2812X-2020")
      (libsource (lib "eagle-import") (part "WS2812C-2020"))
    )
    (comp (ref "LED194")
      (value "WS2812C-2020")
      (footprint "eagle-import:WS2812X-2020")
      (libsource (lib "eagle-import") (part "WS2812C-2020"))
    )
    (comp (ref "LED195")
      (value "WS2812C-2020")
      (footprint "eagle-import:WS2812X-2020")
      (libsource (lib "eagle-import") (part "WS2812C-2020"))
    )
    (comp (ref "LED196")
      (value "WS2812C-2020")
      (footprint "eagle-import:WS2812X-2020")
      (libsource (lib "eagle-import") (part "WS2812C-2020"))
    )
    (comp (ref "LED197")
      (value "WS2812C-2020")
      (footprint "eagle-import:WS2812X-2020")
      (libsource (lib "eagle-import") (part "WS2812C-2020"))
    )
    (comp (ref "LED198")
      (value "WS2812C-2020")
      (footprint "eagle-import:WS2812X-2020")
      (libsource (lib "eagle-import") (part "WS2812C-2020"))
    )
    (comp (ref "LED199")
      (value "WS2812C-2020")
      (footprint "eagle-import:WS2812X-2020")
      (libsource (lib "eagle-import") (part "WS2812C-2020"))
    )
    (comp (ref "LED200")
      (value "WS2812C-2020")
      (footprint "eagle-import:WS2812X-2020")
      (libsource (lib "eagle-import") (part "WS2812C-2020"))
    )
    (comp (ref "LED201")
      (value "WS2812C-2020")
      (footprint "eagle-import:WS2812X-2020")
      (libsource (lib "eagle-import") (part "WS2812C-2020"))
    )
    (comp (ref "LED202")
      (value "WS2812C-2020")
      (footprint "eagle-import:WS2812X-2020")
      (libsource (lib "eagle-import") (part "WS2812C-2020"))
    )
    (comp (ref "LED203")
      (value "WS2812C-2020")
      (footprint "eagle-import:WS2812X-2020")
      (libsource (lib "eagle-import") (part "WS2812C-2020"))
    )
    (comp (ref "LED204")
      (value "WS2812C-2020")
      (footprint "eagle-import:WS2812X-2020")
      (libsource (lib "eagle-import") (part "WS2812C-2020"))
    )
    (comp (ref "LED205")
      (value "WS2812C-2020")
      (footprint "eagle-import:WS2812X-2020")
      (libsource (lib "eagle-import") (part "WS2812C-2020"))
    )
    (comp (ref "LED206")
      (value "WS2812C-2020")
      (footprint "eagle-import:WS2812X-2020")
      (libsource (lib "eagle-import") (part "WS2812C-2020"))
    )
    (comp (ref "LED207")
      (value "WS2812C-2020")
      (footprint "eagle-import:WS2812X-2020")
      (libsource (lib "eagle-import") (part "WS2812C-2020"))
    )
    (comp (ref "LED208")
      (value "WS2812C-2020")
      (footprint "eagle-import:WS2812X-2020")
      (libsource (lib "eagle-import") (part "WS2812C-2020"))
    )
    (comp (ref "LED209")
      (value "WS2812C-2020")
      (footprint "eagle-import:WS2812X-2020")
      (libsource (lib "eagle-import") (part "WS2812C-2020"))
    )
    (comp (ref "LED210")
      (value "WS2812C-2020")
      (footprint "eagle-import:WS2812X-2020")
      (libsource (lib "eagle-import") (part "WS2812C-2020"))
    )
    (comp (ref "LED211")
      (value "WS2812C-2020")
      (footprint "eagle-import:WS2812X-2020")
      (libsource (lib "eagle-import") (part "WS2812C-2020"))
    )
    (comp (ref "LED212")
      (value "WS2812C-2020")
      (footprint "eagle-import:WS2812X-2020")
      (libsource (lib "eagle-import") (part "WS2812C-2020"))
    )
    (comp (ref "LED213")
      (value "WS2812C-2020")
      (footprint "eagle-import:WS2812X-2020")
      (libsource (lib "eagle-import") (part "WS2812C-2020"))
    )
    (comp (ref "LED214")
      (value "WS2812C-2020")
      (footprint "eagle-import:WS2812X-2020")
      (libsource (lib "eagle-import") (part "WS2812C-2020"))
    )
    (comp (ref "LED215")
      (value "WS2812C-2020")
      (footprint "eagle-import:WS2812X-2020")
      (libsource (lib "eagle-import") (part "WS2812C-2020"))
    )
    (comp (ref "LED216")
      (value "WS2812C-2020")
      (footprint "eagle-import:WS2812X-2020")
      (libsource (lib "eagle-import") (part "WS2812C-2020"))
    )
    (comp (ref "LED217")
      (value "WS2812C-2020")
      (footprint "eagle-import:WS2812X-2020")
      (libsource (lib "eagle-import") (part "WS2812C-2020"))
    )
    (comp (ref "LED218")
      (value "WS2812C-2020")
      (footprint "eagle-import:WS2812X-2020")
      (libsource (lib "eagle-import") (part "WS2812C-2020"))
    )
    (comp (ref "LED219")
      (value "WS2812C-2020")
      (footprint "eagle-import:WS2812X-2020")
      (libsource (lib "eagle-import") (part "WS2812C-2020"))
    )
    (comp (ref "LED220")
      (value "WS2812C-2020")
      (footprint "eagle-import:WS2812X-2020")
      (libsource (lib "eagle-import") (part "WS2812C-2020"))
    )
    (comp (ref "LED221")
      (value "WS2812C-2020")
      (footprint "eagle-import:WS2812X-2020")
      (libsource (lib "eagle-import") (part "WS2812C-2020"))
    )
    (comp (ref "LED222")
      (value "WS2812C-2020")
      (footprint "eagle-import:WS2812X-2020")
      (libsource (lib "eagle-import") (part "WS2812C-2020"))
    )
    (comp (ref "LED223")
      (value "WS2812C-2020")
      (footprint "eagle-import:WS2812X-2020")
      (libsource (lib "eagle-import") (part "WS2812C-2020"))
    )
    (comp (ref "LED224")
      (value "WS2812C-2020")
      (footprint "eagle-import:WS2812X-2020")
      (libsource (lib "eagle-import") (part "WS2812C-2020"))
    )
    (comp (ref "LED225")
      (value "WS2812C-2020")
      (footprint "eagle-import:WS2812X-2020")
      (libsource (lib "eagle-import") (part "WS2812C-2020"))
    )
    (comp (ref "LED226")
      (value "WS2812C-2020")
      (footprint "eagle-import:WS2812X-2020")
      (libsource (lib "eagle-import") (part "WS2812C-2020"))
    )
    (comp (ref "LED227")
      (value "WS2812C-2020")
      (footprint "eagle-import:WS2812X-2020")
      (libsource (lib "eagle-import") (part "WS2812C-2020"))
    )
    (comp (ref "LED228")
      (value "WS2812C-2020")
      (footprint "eagle-import:WS2812X-2020")
      (libsource (lib "eagle-import") (part "WS2812C-2020"))
    )
    (comp (ref "LED229")
      (value "WS2812C-2020")
      (footprint "eagle-import:WS2812X-2020")
      (libsource (lib "eagle-import") (part "WS2812C-2020"))
    )
    (comp (ref "LED230")
      (value "WS2812C-2020")
      (footprint "eagle-import:WS2812X-2020")
      (libsource (lib "eagle-import") (part "WS2812C-2020"))
    )
    (comp (ref "LED231")
      (value "WS2812C-2020")
      (footprint "eagle-import:WS2812X-2020")
      (libsource (lib "eagle-import") (part "WS2812C-2020"))
    )
    (comp (ref "LED232")
      (value "WS2812C-2020")
      (footprint "eagle-import:WS2812X-2020")
      (libsource (lib "eagle-import") (part "WS2812C-2020"))
    )
    (comp (ref "LED233")
      (value "WS2812C-2020")
      (footprint "eagle-import:WS2812X-2020")
      (libsource (lib "eagle-import") (part "WS2812C-2020"))
    )
    (comp (ref "LED234")
      (value "WS2812C-2020")
      (footprint "eagle-import:WS2812X-2020")
      (libsource (lib "eagle-import") (part "WS2812C-2020"))
    )
    (comp (ref "LED235")
      (value "WS2812C-2020")
      (footprint "eagle-import:WS2812X-2020")
      (libsource (lib "eagle-import") (part "WS2812C-2020"))
    )
    (comp (ref "LED236")
      (value "WS2812C-2020")
      (footprint "eagle-import:WS2812X-2020")
      (libsource (lib "eagle-import") (part "WS2812C-2020"))
    )
    (comp (ref "LED237")
      (value "WS2812C-2020")
      (footprint "eagle-import:WS2812X-2020")
      (libsource (lib "eagle-import") (part "WS2812C-2020"))
    )
    (comp (ref "LED238")
      (value "WS2812C-2020")
      (footprint "eagle-import:WS2812X-2020")
      (libsource (lib "eagle-import") (part "WS2812C-2020"))
    )
    (comp (ref "LED239")
      (value "WS2812C-2020")
      (footprint "eagle-import:WS2812X-2020")
      (libsource (lib "eagle-import") (part "WS2812C-2020"))
    )
    (comp (ref "LED240")
      (value "WS2812C-2020")
      (footprint "eagle-import:WS2812X-2020")
      (libsource (lib "eagle-import") (part "WS2812C-2020"))
    )
    (comp (ref "LED241")
      (value "WS2812C-2020")
      (footprint "eagle-import:WS2812X-2020")
      (libsource (lib "eagle-import") (part "WS2812C-2020"))
    )
    (comp (ref "LED242")
      (value "WS2812C-2020")
      (footprint "eagle-import:WS2812X-2020")
      (libsource (lib "eagle-import") (part "WS2812C-2020"))
    )
    (comp (ref "LED243")
      (value "WS2812C-2020")
      (footprint "eagle-import:WS2812X-2020")
      (libsource (lib "eagle-import") (part "WS2812C-2020"))
    )
    (comp (ref "LED244")
      (value "WS2812C-2020")
      (footprint "eagle-import:WS2812X-2020")
      (libsource (lib "eagle-import") (part "WS2812C-2020"))
    )
    (comp (ref "LED245")
      (value "WS2812C-2020")
      (footprint "eagle-import:WS2812X-2020")
      (libsource (lib "eagle-import") (part "WS2812C-2020"))
    )
    (comp (ref "LED246")
      (value "WS2812C-2020")
      (footprint "eagle-import:WS2812X-2020")
      (libsource (lib "eagle-import") (part "WS2812C-2020"))
    )
    (comp (ref "LED247")
      (value "WS2812C-2020")
      (footprint "eagle-import:WS2812X-2020")
      (libsource (lib "eagle-import") (part "WS2812C-2020"))
    )
    (comp (ref "LED248")
      (value "WS2812C-2020")
      (footprint "eagle-import:WS2812X-2020")
      (libsource (lib "eagle-import") (part "WS2812C-2020"))
    )
    (comp (ref "LED249")
      (value "WS2812C-2020")
      (footprint "eagle-import:WS2812X-2020")
      (libsource (lib "eagle-import") (part "WS2812C-2020"))
    )
    (comp (ref "LED250")
      (value "WS2812C-2020")
      (footprint "eagle-import:WS2812X-2020")
      (libsource (lib "eagle-import") (part "WS2812C-2020"))
    )
    (comp (ref "LED251")
      (value "WS2812C-2020")
      (footprint "eagle-import:WS2812X-2020")
      (libsource (lib "eagle-import") (part "WS2812C-2020"))
    )
    (comp (ref "LED252")
      (value "WS2812C-2020")
      (footprint "eagle-import:WS2812X-2020")
      (libsource (lib "eagle-import") (part "WS2812C-2020"))
    )
    (comp (ref "LED253")
      (value "WS2812C-2020")
      (footprint "eagle-import:WS2812X-2020")
      (libsource (lib "eagle-import") (part "WS2812C-2020"))
    )
    (comp (ref "LED254")
      (value "WS2812C-2020")
      (footprint "eagle-import:WS2812X-2020")
      (libsource (lib "eagle-import") (part "WS2812C-2020"))
    )
    (comp (ref "LED255")
      (value "WS2812C-2020")
      (footprint "eagle-import:WS2812X-2020")
      (libsource (lib "eagle-import") (part "WS2812C-2020"))
    )
    (comp (ref "LED256")
      (value "WS2812C-2020")
      (footprint "eagle-import:WS2812X-2020")
      (libsource (lib "eagle-import") (part "WS2812C-2020"))
    )
    (comp (ref "LED257")
      (value "WS2812C-2020")
      (footprint "eagle-import:WS2812X-2020")
      (libsource (lib "eagle-import") (part "WS2812C-2020"))
    )
    (comp (ref "LED258")
      (value "WS2812C-2020")
      (footprint "eagle-import:WS2812X-2020")
      (libsource (lib "eagle-import") (part "WS2812C-2020"))
    )
    (comp (ref "LED259")
      (value "WS2812C-2020")
      (footprint "eagle-import:WS2812X-2020")
      (libsource (lib "eagle-import") (part "WS2812C-2020"))
    )
    (comp (ref "LED260")
      (value "WS2812C-2020")
      (footprint "eagle-import:WS2812X-2020")
      (libsource (lib "eagle-import") (part "WS2812C-2020"))
    )
    (comp (ref "LED261")
      (value "WS2812C-2020")
      (footprint "eagle-import:WS2812X-2020")
      (libsource (lib "eagle-import") (part "WS2812C-2020"))
    )
    (comp (ref "LED262")
      (value "WS2812C-2020")
      (footprint "eagle-import:WS2812X-2020")
      (libsource (lib "eagle-import") (part "WS2812C-2020"))
    )
    (comp (ref "LED263")
      (value "WS2812C-2020")
      (footprint "eagle-import:WS2812X-2020")
      (libsource (lib "eagle-import") (part "WS2812C-2020"))
    )
    (comp (ref "LED264")
      (value "WS2812C-2020")
      (footprint "eagle-import:WS2812X-2020")
      (libsource (lib "eagle-import") (part "WS2812C-2020"))
    )
    (comp (ref "LED265")
      (value "WS2812C-2020")
      (footprint "eagle-import:WS2812X-2020")
      (libsource (lib "eagle-import") (part "WS2812C-2020"))
    )
    (comp (ref "LED266")
      (value "WS2812C-2020")
      (footprint "eagle-import:WS2812X-2020")
      (libsource (lib "eagle-import") (part "WS2812C-2020"))
    )
    (comp (ref "LED267")
      (value "WS2812C-2020")
      (footprint "eagle-import:WS2812X-2020")
      (libsource (lib "eagle-import") (part "WS2812C-2020"))
    )
    (comp (ref "LED268")
      (value "WS2812C-2020")
      (footprint "eagle-import:WS2812X-2020")
      (libsource (lib "eagle-import") (part "WS2812C-2020"))
    )
    (comp (ref "LED269")
      (value "WS2812C-2020")
      (footprint "eagle-import:WS2812X-2020")
      (libsource (lib "eagle-import") (part "WS2812C-2020"))
    )
    (comp (ref "LED270")
      (value "WS2812C-2020")
      (footprint "eagle-import:WS2812X-2020")
      (libsource (lib "eagle-import") (part "WS2812C-2020"))
    )
    (comp (ref "LED271")
      (value "WS2812C-2020")
      (footprint "eagle-import:WS2812X-2020")
      (libsource (lib "eagle-import") (part "WS2812C-2020"))
    )
    (comp (ref "LED272")
      (value "WS2812C-2020")
      (footprint "eagle-import:WS2812X-2020")
      (libsource (lib "eagle-import") (part "WS2812C-2020"))
    )
    (comp (ref "LED273")
      (value "WS2812C-2020")
      (footprint "eagle-import:WS2812X-2020")
      (libsource (lib "eagle-import") (part "WS2812C-2020"))
    )
    (comp (ref "LED274")
      (value "WS2812C-2020")
      (footprint "eagle-import:WS2812X-2020")
      (libsource (lib "eagle-import") (part "WS2812C-2020"))
    )
    (comp (ref "LED275")
      (value "WS2812C-2020")
      (footprint "eagle-import:WS2812X-2020")
      (libsource (lib "eagle-import") (part "WS2812C-2020"))
    )
    (comp (ref "LED276")
      (value "WS2812C-2020")
      (footprint "eagle-import:WS2812X-2020")
      (libsource (lib "eagle-import") (part "WS2812C-2020"))
    )
    (comp (ref "LED277")
      (value "WS2812C-2020")
      (footprint "eagle-import:WS2812X-2020")
      (libsource (lib "eagle-import") (part "WS2812C-2020"))
    )
    (comp (ref "LED278")
      (value "WS2812C-2020")
      (footprint "eagle-import:WS2812X-2020")
      (libsource (lib "eagle-import") (part "WS2812C-2020"))
    )
    (comp (ref "LED279")
      (value "WS2812C-2020")
      (footprint "eagle-import:WS2812X-2020")
      (libsource (lib "eagle-import") (part "WS2812C-2020"))
    )
    (comp (ref "LED280")
      (value "WS2812C-2020")
      (footprint "eagle-import:WS2812X-2020")
      (libsource (lib "eagle-import") (part "WS2812C-2020"))
    )
    (comp (ref "LED281")
      (value "WS2812C-2020")
      (footprint "eagle-import:WS2812X-2020")
      (libsource (lib "eagle-import") (part "WS2812C-2020"))
    )
    (comp (ref "LED282")
      (value "WS2812C-2020")
      (footprint "eagle-import:WS2812X-2020")
      (libsource (lib "eagle-import") (part "WS2812C-2020"))
    )
    (comp (ref "LED283")
      (value "WS2812C-2020")
      (footprint "eagle-import:WS2812X-2020")
      (libsource (lib "eagle-import") (part "WS2812C-2020"))
    )
    (comp (ref "LED284")
      (value "WS2812C-2020")
      (footprint "eagle-import:WS2812X-2020")
      (libsource (lib "eagle-import") (part "WS2812C-2020"))
    )
    (comp (ref "LED285")
      (value "WS2812C-2020")
      (footprint "eagle-import:WS2812X-2020")
      (libsource (lib "eagle-import") (part "WS2812C-2020"))
    )
    (comp (ref "LED286")
      (value "WS2812C-2020")
      (footprint "eagle-import:WS2812X-2020")
      (libsource (lib "eagle-import") (part "WS2812C-2020"))
    )
    (comp (ref "LED287")
      (value "WS2812C-2020")
      (footprint "eagle-import:WS2812X-2020")
      (libsource (lib "eagle-import") (part "WS2812C-2020"))
    )
    (comp (ref "LED288")
      (value "WS2812C-2020")
      (footprint "eagle-import:WS2812X-2020")
      (libsource (lib "eagle-import") (part "WS2812C-2020"))
    )
  )
  (nets
    (net (code "1") (name "3.3V") (class "Default")
      (node (ref "IC1") (pin "1") (pinfunction "VCCA_1") (pintype "power_in"))
      (node (ref "J5") (pin "1") (pinfunction "1_1") (pintype "passive"))
      (node (ref "J5") (pin "9") (pinfunction "9_9") (pintype "passive"))
      (node (ref "R1") (pin "1") (pinfunction "1_1") (pintype "passive"))
    )
    (net (code "2") (name "5V") (class "Default")
      (node (ref "C1") (pin "1") (pinfunction "1_1") (pintype "passive"))
      (node (ref "C2") (pin "1") (pinfunction "1_1") (pintype "passive"))
      (node (ref "C3") (pin "1") (pinfunction "1_1") (pintype "passive"))
      (node (ref "C4") (pin "1") (pinfunction "1_1") (pintype "passive"))
      (node (ref "C5") (pin "1") (pinfunction "1_1") (pintype "passive"))
      (node (ref "C6") (pin "1") (pinfunction "1_1") (pintype "passive"))
      (node (ref "C7") (pin "1") (pinfunction "1_1") (pintype "passive"))
      (node (ref "C8") (pin "1") (pinfunction "1_1") (pintype "passive"))
      (node (ref "IC1") (pin "6") (pinfunction "VCCB_6") (pintype "power_in"))
      (node (ref "J1") (pin "3") (pinfunction "3_3") (pintype "passive"))
      (node (ref "J2") (pin "3") (pinfunction "3_3") (pintype "passive"))
      (node (ref "J6") (pin "1") (pinfunction "1_1") (pintype "passive"))
      (node (ref "J6") (pin "2") (pinfunction "2_2") (pintype "passive"))
      (node (ref "LED1") (pin "VDD") (pinfunction "VDD_VDD") (pintype "power_in"))
      (node (ref "LED10") (pin "VDD") (pinfunction "VDD_VDD") (pintype "power_in"))
      (node (ref "LED100") (pin "VDD") (pinfunction "VDD_VDD") (pintype "power_in"))
      (node (ref "LED101") (pin "VDD") (pinfunction "VDD_VDD") (pintype "power_in"))
      (node (ref "LED102") (pin "VDD") (pinfunction "VDD_VDD") (pintype "power_in"))
      (node (ref "LED103") (pin "VDD") (pinfunction "VDD_VDD") (pintype "power_in"))
      (node (ref "LED104") (pin "VDD") (pinfunction "VDD_VDD") (pintype "power_in"))
      (node (ref "LED105") (pin "VDD") (pinfunction "VDD_VDD") (pintype "power_in"))
      (node (ref "LED106") (pin "VDD") (pinfunction "VDD_VDD") (pintype "power_in"))
      (node (ref "LED107") (pin "VDD") (pinfunction "VDD_VDD") (pintype "power_in"))
      (node (ref "LED108") (pin "VDD") (pinfunction "VDD_VDD") (pintype "power_in"))
      (node (ref "LED109") (pin "VDD") (pinfunction "VDD_VDD") (pintype "power_in"))
      (node (ref "LED11") (pin "VDD") (pinfunction "VDD_VDD") (pintype "power_in"))
      (node (ref "LED110") (pin "VDD") (pinfunction "VDD_VDD") (pintype "power_in"))
      (node (ref "LED111") (pin "VDD") (pinfunction "VDD_VDD") (pintype "power_in"))
      (node (ref "LED112") (pin "VDD") (pinfunction "VDD_VDD") (pintype "power_in"))
      (node (ref "LED113") (pin "VDD") (pinfunction "VDD_VDD") (pintype "power_in"))
      (node (ref "LED114") (pin "VDD") (pinfunction "VDD_VDD") (pintype "power_in"))
      (node (ref "LED115") (pin "VDD") (pinfunction "VDD_VDD") (pintype "power_in"))
      (node (ref "LED116") (pin "VDD") (pinfunction "VDD_VDD") (pintype "power_in"))
      (node (ref "LED117") (pin "VDD") (pinfunction "VDD_VDD") (pintype "power_in"))
      (node (ref "LED118") (pin "VDD") (pinfunction "VDD_VDD") (pintype "power_in"))
      (node (ref "LED119") (pin "VDD") (pinfunction "VDD_VDD") (pintype "power_in"))
      (node (ref "LED12") (pin "VDD") (pinfunction "VDD_VDD") (pintype "power_in"))
      (node (ref "LED120") (pin "VDD") (pinfunction "VDD_VDD") (pintype "power_in"))
      (node (ref "LED121") (pin "VDD") (pinfunction "VDD_VDD") (pintype "power_in"))
      (node (ref "LED122") (pin "VDD") (pinfunction "VDD_VDD") (pintype "power_in"))
      (node (ref "LED123") (pin "VDD") (pinfunction "VDD_VDD") (pintype "power_in"))
      (node (ref "LED124") (pin "VDD") (pinfunction "VDD_VDD") (pintype "power_in"))
      (node (ref "LED125") (pin "VDD") (pinfunction "VDD_VDD") (pintype "power_in"))
      (node (ref "LED126") (pin "VDD") (pinfunction "VDD_VDD") (pintype "power_in"))
      (node (ref "LED127") (pin "VDD") (pinfunction "VDD_VDD") (pintype "power_in"))
      (node (ref "LED128") (pin "VDD") (pinfunction "VDD_VDD") (pintype "power_in"))
      (node (ref "LED129") (pin "VDD") (pinfunction "VDD_VDD") (pintype "power_in"))
      (node (ref "LED13") (pin "VDD") (pinfunction "VDD_VDD") (pintype "power_in"))
      (node (ref "LED130") (pin "VDD") (pinfunction "VDD_VDD") (pintype "power_in"))
      (node (ref "LED131") (pin "VDD") (pinfunction "VDD_VDD") (pintype "power_in"))
      (node (ref "LED132") (pin "VDD") (pinfunction "VDD_VDD") (pintype "power_in"))
      (node (ref "LED133") (pin "VDD") (pinfunction "VDD_VDD") (pintype "power_in"))
      (node (ref "LED134") (pin "VDD") (pinfunction "VDD_VDD") (pintype "power_in"))
      (node (ref "LED135") (pin "VDD") (pinfunction "VDD_VDD") (pintype "power_in"))
      (node (ref "LED136") (pin "VDD") (pinfunction "VDD_VDD") (pintype "power_in"))
      (node (ref "LED137") (pin "VDD") (pinfunction "VDD_VDD") (pintype "power_in"))
      (node (ref "LED138") (pin "VDD") (pinfunction "VDD_VDD") (pintype "power_in"))
      (node (ref "LED139") (pin "VDD") (pinfunction "VDD_VDD") (pintype "power_in"))
      (node (ref "LED14") (pin "VDD") (pinfunction "VDD_VDD") (pintype "power_in"))
      (node (ref "LED140") (pin "VDD") (pinfunction "VDD_VDD") (pintype "power_in"))
      (node (ref "LED141") (pin "VDD") (pinfunction "VDD_VDD") (pintype "power_in"))
      (node (ref "LED142") (pin "VDD") (pinfunction "VDD_VDD") (pintype "power_in"))
      (node (ref "LED143") (pin "VDD") (pinfunction "VDD_VDD") (pintype "power_in"))
      (node (ref "LED144") (pin "VDD") (pinfunction "VDD_VDD") (pintype "power_in"))
      (node (ref "LED145") (pin "VDD") (pinfunction "VDD_VDD") (pintype "power_in"))
      (node (ref "LED146") (pin "VDD") (pinfunction "VDD_VDD") (pintype "power_in"))
      (node (ref "LED147") (pin "VDD") (pinfunction "VDD_VDD") (pintype "power_in"))
      (node (ref "LED148") (pin "VDD") (pinfunction "VDD_VDD") (pintype "power_in"))
      (node (ref "LED149") (pin "VDD") (pinfunction "VDD_VDD") (pintype "power_in"))
      (node (ref "LED15") (pin "VDD") (pinfunction "VDD_VDD") (pintype "power_in"))
      (node (ref "LED150") (pin "VDD") (pinfunction "VDD_VDD") (pintype "power_in"))
      (node (ref "LED151") (pin "VDD") (pinfunction "VDD_VDD") (pintype "power_in"))
      (node (ref "LED152") (pin "VDD") (pinfunction "VDD_VDD") (pintype "power_in"))
      (node (ref "LED153") (pin "VDD") (pinfunction "VDD_VDD") (pintype "power_in"))
      (node (ref "LED154") (pin "VDD") (pinfunction "VDD_VDD") (pintype "power_in"))
      (node (ref "LED155") (pin "VDD") (pinfunction "VDD_VDD") (pintype "power_in"))
      (node (ref "LED156") (pin "VDD") (pinfunction "VDD_VDD") (pintype "power_in"))
      (node (ref "LED157") (pin "VDD") (pinfunction "VDD_VDD") (pintype "power_in"))
      (node (ref "LED158") (pin "VDD") (pinfunction "VDD_VDD") (pintype "power_in"))
      (node (ref "LED159") (pin "VDD") (pinfunction "VDD_VDD") (pintype "power_in"))
      (node (ref "LED16") (pin "VDD") (pinfunction "VDD_VDD") (pintype "power_in"))
      (node (ref "LED160") (pin "VDD") (pinfunction "VDD_VDD") (pintype "power_in"))
      (node (ref "LED161") (pin "VDD") (pinfunction "VDD_VDD") (pintype "power_in"))
      (node (ref "LED162") (pin "VDD") (pinfunction "VDD_VDD") (pintype "power_in"))
      (node (ref "LED163") (pin "VDD") (pinfunction "VDD_VDD") (pintype "power_in"))
      (node (ref "LED164") (pin "VDD") (pinfunction "VDD_VDD") (pintype "power_in"))
      (node (ref "LED165") (pin "VDD") (pinfunction "VDD_VDD") (pintype "power_in"))
      (node (ref "LED166") (pin "VDD") (pinfunction "VDD_VDD") (pintype "power_in"))
      (node (ref "LED167") (pin "VDD") (pinfunction "VDD_VDD") (pintype "power_in"))
      (node (ref "LED168") (pin "VDD") (pinfunction "VDD_VDD") (pintype "power_in"))
      (node (ref "LED169") (pin "VDD") (pinfunction "VDD_VDD") (pintype "power_in"))
      (node (ref "LED17") (pin "VDD") (pinfunction "VDD_VDD") (pintype "power_in"))
      (node (ref "LED170") (pin "VDD") (pinfunction "VDD_VDD") (pintype "power_in"))
      (node (ref "LED171") (pin "VDD") (pinfunction "VDD_VDD") (pintype "power_in"))
      (node (ref "LED172") (pin "VDD") (pinfunction "VDD_VDD") (pintype "power_in"))
      (node (ref "LED173") (pin "VDD") (pinfunction "VDD_VDD") (pintype "power_in"))
      (node (ref "LED174") (pin "VDD") (pinfunction "VDD_VDD") (pintype "power_in"))
      (node (ref "LED175") (pin "VDD") (pinfunction "VDD_VDD") (pintype "power_in"))
      (node (ref "LED176") (pin "VDD") (pinfunction "VDD_VDD") (pintype "power_in"))
      (node (ref "LED177") (pin "VDD") (pinfunction "VDD_VDD") (pintype "power_in"))
      (node (ref "LED178") (pin "VDD") (pinfunction "VDD_VDD") (pintype "power_in"))
      (node (ref "LED179") (pin "VDD") (pinfunction "VDD_VDD") (pintype "power_in"))
      (node (ref "LED18") (pin "VDD") (pinfunction "VDD_VDD") (pintype "power_in"))
      (node (ref "LED180") (pin "VDD") (pinfunction "VDD_VDD") (pintype "power_in"))
      (node (ref "LED181") (pin "VDD") (pinfunction "VDD_VDD") (pintype "power_in"))
      (node (ref "LED182") (pin "VDD") (pinfunction "VDD_VDD") (pintype "power_in"))
      (node (ref "LED183") (pin "VDD") (pinfunction "VDD_VDD") (pintype "power_in"))
      (node (ref "LED184") (pin "VDD") (pinfunction "VDD_VDD") (pintype "power_in"))
      (node (ref "LED185") (pin "VDD") (pinfunction "VDD_VDD") (pintype "power_in"))
      (node (ref "LED186") (pin "VDD") (pinfunction "VDD_VDD") (pintype "power_in"))
      (node (ref "LED187") (pin "VDD") (pinfunction "VDD_VDD") (pintype "power_in"))
      (node (ref "LED188") (pin "VDD") (pinfunction "VDD_VDD") (pintype "power_in"))
      (node (ref "LED189") (pin "VDD") (pinfunction "VDD_VDD") (pintype "power_in"))
      (node (ref "LED19") (pin "VDD") (pinfunction "VDD_VDD") (pintype "power_in"))
      (node (ref "LED190") (pin "VDD") (pinfunction "VDD_VDD") (pintype "power_in"))
      (node (ref "LED191") (pin "VDD") (pinfunction "VDD_VDD") (pintype "power_in"))
      (node (ref "LED192") (pin "VDD") (pinfunction "VDD_VDD") (pintype "power_in"))
      (node (ref "LED193") (pin "VDD") (pinfunction "VDD_VDD") (pintype "power_in"))
      (node (ref "LED194") (pin "VDD") (pinfunction "VDD_VDD") (pintype "power_in"))
      (node (ref "LED195") (pin "VDD") (pinfunction "VDD_VDD") (pintype "power_in"))
      (node (ref "LED196") (pin "VDD") (pinfunction "VDD_VDD") (pintype "power_in"))
      (node (ref "LED197") (pin "VDD") (pinfunction "VDD_VDD") (pintype "power_in"))
      (node (ref "LED198") (pin "VDD") (pinfunction "VDD_VDD") (pintype "power_in"))
      (node (ref "LED199") (pin "VDD") (pinfunction "VDD_VDD") (pintype "power_in"))
      (node (ref "LED2") (pin "VDD") (pinfunction "VDD_VDD") (pintype "power_in"))
      (node (ref "LED20") (pin "VDD") (pinfunction "VDD_VDD") (pintype "power_in"))
      (node (ref "LED200") (pin "VDD") (pinfunction "VDD_VDD") (pintype "power_in"))
      (node (ref "LED201") (pin "VDD") (pinfunction "VDD_VDD") (pintype "power_in"))
      (node (ref "LED202") (pin "VDD") (pinfunction "VDD_VDD") (pintype "power_in"))
      (node (ref "LED203") (pin "VDD") (pinfunction "VDD_VDD") (pintype "power_in"))
      (node (ref "LED204") (pin "VDD") (pinfunction "VDD_VDD") (pintype "power_in"))
      (node (ref "LED205") (pin "VDD") (pinfunction "VDD_VDD") (pintype "power_in"))
      (node (ref "LED206") (pin "VDD") (pinfunction "VDD_VDD") (pintype "power_in"))
      (node (ref "LED207") (pin "VDD") (pinfunction "VDD_VDD") (pintype "power_in"))
      (node (ref "LED208") (pin "VDD") (pinfunction "VDD_VDD") (pintype "power_in"))
      (node (ref "LED209") (pin "VDD") (pinfunction "VDD_VDD") (pintype "power_in"))
      (node (ref "LED21") (pin "VDD") (pinfunction "VDD_VDD") (pintype "power_in"))
      (node (ref "LED210") (pin "VDD") (pinfunction "VDD_VDD") (pintype "power_in"))
      (node (ref "LED211") (pin "VDD") (pinfunction "VDD_VDD") (pintype "power_in"))
      (node (ref "LED212") (pin "VDD") (pinfunction "VDD_VDD") (pintype "power_in"))
      (node (ref "LED213") (pin "VDD") (pinfunction "VDD_VDD") (pintype "power_in"))
      (node (ref "LED214") (pin "VDD") (pinfunction "VDD_VDD") (pintype "power_in"))
      (node (ref "LED215") (pin "VDD") (pinfunction "VDD_VDD") (pintype "power_in"))
      (node (ref "LED216") (pin "VDD") (pinfunction "VDD_VDD") (pintype "power_in"))
      (node (ref "LED217") (pin "VDD") (pinfunction "VDD_VDD") (pintype "power_in"))
      (node (ref "LED218") (pin "VDD") (pinfunction "VDD_VDD") (pintype "power_in"))
      (node (ref "LED219") (pin "VDD") (pinfunction "VDD_VDD") (pintype "power_in"))
      (node (ref "LED22") (pin "VDD") (pinfunction "VDD_VDD") (pintype "power_in"))
      (node (ref "LED220") (pin "VDD") (pinfunction "VDD_VDD") (pintype "power_in"))
      (node (ref "LED221") (pin "VDD") (pinfunction "VDD_VDD") (pintype "power_in"))
      (node (ref "LED222") (pin "VDD") (pinfunction "VDD_VDD") (pintype "power_in"))
      (node (ref "LED223") (pin "VDD") (pinfunction "VDD_VDD") (pintype "power_in"))
      (node (ref "LED224") (pin "VDD") (pinfunction "VDD_VDD") (pintype "power_in"))
      (node (ref "LED225") (pin "VDD") (pinfunction "VDD_VDD") (pintype "power_in"))
      (node (ref "LED226") (pin "VDD") (pinfunction "VDD_VDD") (pintype "power_in"))
      (node (ref "LED227") (pin "VDD") (pinfunction "VDD_VDD") (pintype "power_in"))
      (node (ref "LED228") (pin "VDD") (pinfunction "VDD_VDD") (pintype "power_in"))
      (node (ref "LED229") (pin "VDD") (pinfunction "VDD_VDD") (pintype "power_in"))
      (node (ref "LED23") (pin "VDD") (pinfunction "VDD_VDD") (pintype "power_in"))
      (node (ref "LED230") (pin "VDD") (pinfunction "VDD_VDD") (pintype "power_in"))
      (node (ref "LED231") (pin "VDD") (pinfunction "VDD_VDD") (pintype "power_in"))
      (node (ref "LED232") (pin "VDD") (pinfunction "VDD_VDD") (pintype "power_in"))
      (node (ref "LED233") (pin "VDD") (pinfunction "VDD_VDD") (pintype "power_in"))
      (node (ref "LED234") (pin "VDD") (pinfunction "VDD_VDD") (pintype "power_in"))
      (node (ref "LED235") (pin "VDD") (pinfunction "VDD_VDD") (pintype "power_in"))
      (node (ref "LED236") (pin "VDD") (pinfunction "VDD_VDD") (pintype "power_in"))
      (node (ref "LED237") (pin "VDD") (pinfunction "VDD_VDD") (pintype "power_in"))
      (node (ref "LED238") (pin "VDD") (pinfunction "VDD_VDD") (pintype "power_in"))
      (node (ref "LED239") (pin "VDD") (pinfunction "VDD_VDD") (pintype "power_in"))
      (node (ref "LED24") (pin "VDD") (pinfunction "VDD_VDD") (pintype "power_in"))
      (node (ref "LED240") (pin "VDD") (pinfunction "VDD_VDD") (pintype "power_in"))
      (node (ref "LED241") (pin "VDD") (pinfunction "VDD_VDD") (pintype "power_in"))
      (node (ref "LED242") (pin "VDD") (pinfunction "VDD_VDD") (pintype "power_in"))
      (node (ref "LED243") (pin "VDD") (pinfunction "VDD_VDD") (pintype "power_in"))
      (node (ref "LED244") (pin "VDD") (pinfunction "VDD_VDD") (pintype "power_in"))
      (node (ref "LED245") (pin "VDD") (pinfunction "VDD_VDD") (pintype "power_in"))
      (node (ref "LED246") (pin "VDD") (pinfunction "VDD_VDD") (pintype "power_in"))
      (node (ref "LED247") (pin "VDD") (pinfunction "VDD_VDD") (pintype "power_in"))
      (node (ref "LED248") (pin "VDD") (pinfunction "VDD_VDD") (pintype "power_in"))
      (node (ref "LED249") (pin "VDD") (pinfunction "VDD_VDD") (pintype "power_in"))
      (node (ref "LED25") (pin "VDD") (pinfunction "VDD_VDD") (pintype "power_in"))
      (node (ref "LED250") (pin "VDD") (pinfunction "VDD_VDD") (pintype "power_in"))
      (node (ref "LED251") (pin "VDD") (pinfunction "VDD_VDD") (pintype "power_in"))
      (node (ref "LED252") (pin "VDD") (pinfunction "VDD_VDD") (pintype "power_in"))
      (node (ref "LED253") (pin "VDD") (pinfunction "VDD_VDD") (pintype "power_in"))
      (node (ref "LED254") (pin "VDD") (pinfunction "VDD_VDD") (pintype "power_in"))
      (node (ref "LED255") (pin "VDD") (pinfunction "VDD_VDD") (pintype "power_in"))
      (node (ref "LED256") (pin "VDD") (pinfunction "VDD_VDD") (pintype "power_in"))
      (node (ref "LED257") (pin "VDD") (pinfunction "VDD_VDD") (pintype "power_in"))
      (node (ref "LED258") (pin "VDD") (pinfunction "VDD_VDD") (pintype "power_in"))
      (node (ref "LED259") (pin "VDD") (pinfunction "VDD_VDD") (pintype "power_in"))
      (node (ref "LED26") (pin "VDD") (pinfunction "VDD_VDD") (pintype "power_in"))
      (node (ref "LED260") (pin "VDD") (pinfunction "VDD_VDD") (pintype "power_in"))
      (node (ref "LED261") (pin "VDD") (pinfunction "VDD_VDD") (pintype "power_in"))
      (node (ref "LED262") (pin "VDD") (pinfunction "VDD_VDD") (pintype "power_in"))
      (node (ref "LED263") (pin "VDD") (pinfunction "VDD_VDD") (pintype "power_in"))
      (node (ref "LED264") (pin "VDD") (pinfunction "VDD_VDD") (pintype "power_in"))
      (node (ref "LED265") (pin "VDD") (pinfunction "VDD_VDD") (pintype "power_in"))
      (node (ref "LED266") (pin "VDD") (pinfunction "VDD_VDD") (pintype "power_in"))
      (node (ref "LED267") (pin "VDD") (pinfunction "VDD_VDD") (pintype "power_in"))
      (node (ref "LED268") (pin "VDD") (pinfunction "VDD_VDD") (pintype "power_in"))
      (node (ref "LED269") (pin "VDD") (pinfunction "VDD_VDD") (pintype "power_in"))
      (node (ref "LED27") (pin "VDD") (pinfunction "VDD_VDD") (pintype "power_in"))
      (node (ref "LED270") (pin "VDD") (pinfunction "VDD_VDD") (pintype "power_in"))
      (node (ref "LED271") (pin "VDD") (pinfunction "VDD_VDD") (pintype "power_in"))
      (node (ref "LED272") (pin "VDD") (pinfunction "VDD_VDD") (pintype "power_in"))
      (node (ref "LED273") (pin "VDD") (pinfunction "VDD_VDD") (pintype "power_in"))
      (node (ref "LED274") (pin "VDD") (pinfunction "VDD_VDD") (pintype "power_in"))
      (node (ref "LED275") (pin "VDD") (pinfunction "VDD_VDD") (pintype "power_in"))
      (node (ref "LED276") (pin "VDD") (pinfunction "VDD_VDD") (pintype "power_in"))
      (node (ref "LED277") (pin "VDD") (pinfunction "VDD_VDD") (pintype "power_in"))
      (node (ref "LED278") (pin "VDD") (pinfunction "VDD_VDD") (pintype "power_in"))
      (node (ref "LED279") (pin "VDD") (pinfunction "VDD_VDD") (pintype "power_in"))
      (node (ref "LED28") (pin "VDD") (pinfunction "VDD_VDD") (pintype "power_in"))
      (node (ref "LED280") (pin "VDD") (pinfunction "VDD_VDD") (pintype "power_in"))
      (node (ref "LED281") (pin "VDD") (pinfunction "VDD_VDD") (pintype "power_in"))
      (node (ref "LED282") (pin "VDD") (pinfunction "VDD_VDD") (pintype "power_in"))
      (node (ref "LED283") (pin "VDD") (pinfunction "VDD_VDD") (pintype "power_in"))
      (node (ref "LED284") (pin "VDD") (pinfunction "VDD_VDD") (pintype "power_in"))
      (node (ref "LED285") (pin "VDD") (pinfunction "VDD_VDD") (pintype "power_in"))
      (node (ref "LED286") (pin "VDD") (pinfunction "VDD_VDD") (pintype "power_in"))
      (node (ref "LED287") (pin "VDD") (pinfunction "VDD_VDD") (pintype "power_in"))
      (node (ref "LED288") (pin "VDD") (pinfunction "VDD_VDD") (pintype "power_in"))
      (node (ref "LED29") (pin "VDD") (pinfunction "VDD_VDD") (pintype "power_in"))
      (node (ref "LED3") (pin "VDD") (pinfunction "VDD_VDD") (pintype "power_in"))
      (node (ref "LED30") (pin "VDD") (pinfunction "VDD_VDD") (pintype "power_in"))
      (node (ref "LED31") (pin "VDD") (pinfunction "VDD_VDD") (pintype "power_in"))
      (node (ref "LED32") (pin "VDD") (pinfunction "VDD_VDD") (pintype "power_in"))
      (node (ref "LED33") (pin "VDD") (pinfunction "VDD_VDD") (pintype "power_in"))
      (node (ref "LED34") (pin "VDD") (pinfunction "VDD_VDD") (pintype "power_in"))
      (node (ref "LED35") (pin "VDD") (pinfunction "VDD_VDD") (pintype "power_in"))
      (node (ref "LED36") (pin "VDD") (pinfunction "VDD_VDD") (pintype "power_in"))
      (node (ref "LED37") (pin "VDD") (pinfunction "VDD_VDD") (pintype "power_in"))
      (node (ref "LED38") (pin "VDD") (pinfunction "VDD_VDD") (pintype "power_in"))
      (node (ref "LED39") (pin "VDD") (pinfunction "VDD_VDD") (pintype "power_in"))
      (node (ref "LED4") (pin "VDD") (pinfunction "VDD_VDD") (pintype "power_in"))
      (node (ref "LED40") (pin "VDD") (pinfunction "VDD_VDD") (pintype "power_in"))
      (node (ref "LED41") (pin "VDD") (pinfunction "VDD_VDD") (pintype "power_in"))
      (node (ref "LED42") (pin "VDD") (pinfunction "VDD_VDD") (pintype "power_in"))
      (node (ref "LED43") (pin "VDD") (pinfunction "VDD_VDD") (pintype "power_in"))
      (node (ref "LED44") (pin "VDD") (pinfunction "VDD_VDD") (pintype "power_in"))
      (node (ref "LED45") (pin "VDD") (pinfunction "VDD_VDD") (pintype "power_in"))
      (node (ref "LED46") (pin "VDD") (pinfunction "VDD_VDD") (pintype "power_in"))
      (node (ref "LED47") (pin "VDD") (pinfunction "VDD_VDD") (pintype "power_in"))
      (node (ref "LED48") (pin "VDD") (pinfunction "VDD_VDD") (pintype "power_in"))
      (node (ref "LED49") (pin "VDD") (pinfunction "VDD_VDD") (pintype "power_in"))
      (node (ref "LED5") (pin "VDD") (pinfunction "VDD_VDD") (pintype "power_in"))
      (node (ref "LED50") (pin "VDD") (pinfunction "VDD_VDD") (pintype "power_in"))
      (node (ref "LED51") (pin "VDD") (pinfunction "VDD_VDD") (pintype "power_in"))
      (node (ref "LED52") (pin "VDD") (pinfunction "VDD_VDD") (pintype "power_in"))
      (node (ref "LED53") (pin "VDD") (pinfunction "VDD_VDD") (pintype "power_in"))
      (node (ref "LED54") (pin "VDD") (pinfunction "VDD_VDD") (pintype "power_in"))
      (node (ref "LED55") (pin "VDD") (pinfunction "VDD_VDD") (pintype "power_in"))
      (node (ref "LED56") (pin "VDD") (pinfunction "VDD_VDD") (pintype "power_in"))
      (node (ref "LED57") (pin "VDD") (pinfunction "VDD_VDD") (pintype "power_in"))
      (node (ref "LED58") (pin "VDD") (pinfunction "VDD_VDD") (pintype "power_in"))
      (node (ref "LED59") (pin "VDD") (pinfunction "VDD_VDD") (pintype "power_in"))
      (node (ref "LED6") (pin "VDD") (pinfunction "VDD_VDD") (pintype "power_in"))
      (node (ref "LED60") (pin "VDD") (pinfunction "VDD_VDD") (pintype "power_in"))
      (node (ref "LED61") (pin "VDD") (pinfunction "VDD_VDD") (pintype "power_in"))
      (node (ref "LED62") (pin "VDD") (pinfunction "VDD_VDD") (pintype "power_in"))
      (node (ref "LED63") (pin "VDD") (pinfunction "VDD_VDD") (pintype "power_in"))
      (node (ref "LED64") (pin "VDD") (pinfunction "VDD_VDD") (pintype "power_in"))
      (node (ref "LED65") (pin "VDD") (pinfunction "VDD_VDD") (pintype "power_in"))
      (node (ref "LED66") (pin "VDD") (pinfunction "VDD_VDD") (pintype "power_in"))
      (node (ref "LED67") (pin "VDD") (pinfunction "VDD_VDD") (pintype "power_in"))
      (node (ref "LED68") (pin "VDD") (pinfunction "VDD_VDD") (pintype "power_in"))
      (node (ref "LED69") (pin "VDD") (pinfunction "VDD_VDD") (pintype "power_in"))
      (node (ref "LED7") (pin "VDD") (pinfunction "VDD_VDD") (pintype "power_in"))
      (node (ref "LED70") (pin "VDD") (pinfunction "VDD_VDD") (pintype "power_in"))
      (node (ref "LED71") (pin "VDD") (pinfunction "VDD_VDD") (pintype "power_in"))
      (node (ref "LED72") (pin "VDD") (pinfunction "VDD_VDD") (pintype "power_in"))
      (node (ref "LED73") (pin "VDD") (pinfunction "VDD_VDD") (pintype "power_in"))
      (node (ref "LED74") (pin "VDD") (pinfunction "VDD_VDD") (pintype "power_in"))
      (node (ref "LED75") (pin "VDD") (pinfunction "VDD_VDD") (pintype "power_in"))
      (node (ref "LED76") (pin "VDD") (pinfunction "VDD_VDD") (pintype "power_in"))
      (node (ref "LED77") (pin "VDD") (pinfunction "VDD_VDD") (pintype "power_in"))
      (node (ref "LED78") (pin "VDD") (pinfunction "VDD_VDD") (pintype "power_in"))
      (node (ref "LED79") (pin "VDD") (pinfunction "VDD_VDD") (pintype "power_in"))
      (node (ref "LED8") (pin "VDD") (pinfunction "VDD_VDD") (pintype "power_in"))
      (node (ref "LED80") (pin "VDD") (pinfunction "VDD_VDD") (pintype "power_in"))
      (node (ref "LED81") (pin "VDD") (pinfunction "VDD_VDD") (pintype "power_in"))
      (node (ref "LED82") (pin "VDD") (pinfunction "VDD_VDD") (pintype "power_in"))
      (node (ref "LED83") (pin "VDD") (pinfunction "VDD_VDD") (pintype "power_in"))
      (node (ref "LED84") (pin "VDD") (pinfunction "VDD_VDD") (pintype "power_in"))
      (node (ref "LED85") (pin "VDD") (pinfunction "VDD_VDD") (pintype "power_in"))
      (node (ref "LED86") (pin "VDD") (pinfunction "VDD_VDD") (pintype "power_in"))
      (node (ref "LED87") (pin "VDD") (pinfunction "VDD_VDD") (pintype "power_in"))
      (node (ref "LED88") (pin "VDD") (pinfunction "VDD_VDD") (pintype "power_in"))
      (node (ref "LED89") (pin "VDD") (pinfunction "VDD_VDD") (pintype "power_in"))
      (node (ref "LED9") (pin "VDD") (pinfunction "VDD_VDD") (pintype "power_in"))
      (node (ref "LED90") (pin "VDD") (pinfunction "VDD_VDD") (pintype "power_in"))
      (node (ref "LED91") (pin "VDD") (pinfunction "VDD_VDD") (pintype "power_in"))
      (node (ref "LED92") (pin "VDD") (pinfunction "VDD_VDD") (pintype "power_in"))
      (node (ref "LED93") (pin "VDD") (pinfunction "VDD_VDD") (pintype "power_in"))
      (node (ref "LED94") (pin "VDD") (pinfunction "VDD_VDD") (pintype "power_in"))
      (node (ref "LED95") (pin "VDD") (pinfunction "VDD_VDD") (pintype "power_in"))
      (node (ref "LED96") (pin "VDD") (pinfunction "VDD_VDD") (pintype "power_in"))
      (node (ref "LED97") (pin "VDD") (pinfunction "VDD_VDD") (pintype "power_in"))
      (node (ref "LED98") (pin "VDD") (pinfunction "VDD_VDD") (pintype "power_in"))
      (node (ref "LED99") (pin "VDD") (pinfunction "VDD_VDD") (pintype "power_in"))
    )
    (net (code "3") (name "DATA") (class "Default")
      (node (ref "IC1") (pin "3") (pinfunction "A_3") (pintype "bidirectional"))
      (node (ref "SJ1") (pin "2") (pinfunction "2_2") (pintype "passive"))
    )
    (net (code "4") (name "DI_FIRST") (class "Default")
      (node (ref "IC1") (pin "4") (pinfunction "B_4") (pintype "bidirectional"))
      (node (ref "J1") (pin "2") (pinfunction "2_2") (pintype "passive"))
      (node (ref "LED1") (pin "DI") (pinfunction "DI_DI") (pintype "input"))
    )
    (net (code "5") (name "DO_LAST") (class "Default")
      (node (ref "J2") (pin "2") (pinfunction "2_2") (pintype "passive"))
      (node (ref "LED288") (pin "DO") (pinfunction "DO_DO") (pintype "output"))
    )
    (net (code "6") (name "DO_MID1") (class "Default")
      (node (ref "LED72") (pin "DO") (pinfunction "DO_DO") (pintype "output"))
      (node (ref "LED73") (pin "DI") (pinfunction "DI_DI") (pintype "input"))
    )
    (net (code "7") (name "DO_MID2") (class "Default")
      (node (ref "LED144") (pin "DO") (pinfunction "DO_DO") (pintype "output"))
      (node (ref "LED145") (pin "DI") (pinfunction "DI_DI") (pintype "input"))
    )
    (net (code "8") (name "DO_MID3") (class "Default")
      (node (ref "LED216") (pin "DO") (pinfunction "DO_DO") (pintype "output"))
      (node (ref "LED217") (pin "DI") (pinfunction "DI_DI") (pintype "input"))
    )
    (net (code "9") (name "GND") (class "Default")
      (node (ref "C1") (pin "2") (pinfunction "2_2") (pintype "passive"))
      (node (ref "C2") (pin "2") (pinfunction "2_2") (pintype "passive"))
      (node (ref "C3") (pin "2") (pinfunction "2_2") (pintype "passive"))
      (node (ref "C4") (pin "2") (pinfunction "2_2") (pintype "passive"))
      (node (ref "C5") (pin "2") (pinfunction "2_2") (pintype "passive"))
      (node (ref "C6") (pin "2") (pinfunction "2_2") (pintype "passive"))
      (node (ref "C7") (pin "2") (pinfunction "2_2") (pintype "passive"))
      (node (ref "C8") (pin "2") (pinfunction "2_2") (pintype "passive"))
      (node (ref "IC1") (pin "2") (pinfunction "GND_2") (pintype "power_in"))
      (node (ref "J1") (pin "1") (pinfunction "1_1") (pintype "passive"))
      (node (ref "J2") (pin "1") (pinfunction "1_1") (pintype "passive"))
      (node (ref "J5") (pin "13") (pinfunction "13_13") (pintype "passive"))
      (node (ref "J5") (pin "20") (pinfunction "20_20") (pintype "passive"))
      (node (ref "J5") (pin "5") (pinfunction "5_5") (pintype "passive"))
      (node (ref "J6") (pin "10") (pinfunction "10_10") (pintype "passive"))
      (node (ref "J6") (pin "15") (pinfunction "15_15") (pintype "passive"))
      (node (ref "J6") (pin "17") (pinfunction "17_17") (pintype "passive"))
      (node (ref "J6") (pin "3") (pinfunction "3_3") (pintype "passive"))
      (node (ref "J6") (pin "7") (pinfunction "7_7") (pintype "passive"))
      (node (ref "LED1") (pin "GND") (pinfunction "GND_GND") (pintype "power_in"))
      (node (ref "LED10") (pin "GND") (pinfunction "GND_GND") (pintype "power_in"))
      (node (ref "LED100") (pin "GND") (pinfunction "GND_GND") (pintype "power_in"))
      (node (ref "LED101") (pin "GND") (pinfunction "GND_GND") (pintype "power_in"))
      (node (ref "LED102") (pin "GND") (pinfunction "GND_GND") (pintype "power_in"))
      (node (ref "LED103") (pin "GND") (pinfunction "GND_GND") (pintype "power_in"))
      (node (ref "LED104") (pin "GND") (pinfunction "GND_GND") (pintype "power_in"))
      (node (ref "LED105") (pin "GND") (pinfunction "GND_GND") (pintype "power_in"))
      (node (ref "LED106") (pin "GND") (pinfunction "GND_GND") (pintype "power_in"))
      (node (ref "LED107") (pin "GND") (pinfunction "GND_GND") (pintype "power_in"))
      (node (ref "LED108") (pin "GND") (pinfunction "GND_GND") (pintype "power_in"))
      (node (ref "LED109") (pin "GND") (pinfunction "GND_GND") (pintype "power_in"))
      (node (ref "LED11") (pin "GND") (pinfunction "GND_GND") (pintype "power_in"))
      (node (ref "LED110") (pin "GND") (pinfunction "GND_GND") (pintype "power_in"))
      (node (ref "LED111") (pin "GND") (pinfunction "GND_GND") (pintype "power_in"))
      (node (ref "LED112") (pin "GND") (pinfunction "GND_GND") (pintype "power_in"))
      (node (ref "LED113") (pin "GND") (pinfunction "GND_GND") (pintype "power_in"))
      (node (ref "LED114") (pin "GND") (pinfunction "GND_GND") (pintype "power_in"))
      (node (ref "LED115") (pin "GND") (pinfunction "GND_GND") (pintype "power_in"))
      (node (ref "LED116") (pin "GND") (pinfunction "GND_GND") (pintype "power_in"))
      (node (ref "LED117") (pin "GND") (pinfunction "GND_GND") (pintype "power_in"))
      (node (ref "LED118") (pin "GND") (pinfunction "GND_GND") (pintype "power_in"))
      (node (ref "LED119") (pin "GND") (pinfunction "GND_GND") (pintype "power_in"))
      (node (ref "LED12") (pin "GND") (pinfunction "GND_GND") (pintype "power_in"))
      (node (ref "LED120") (pin "GND") (pinfunction "GND_GND") (pintype "power_in"))
      (node (ref "LED121") (pin "GND") (pinfunction "GND_GND") (pintype "power_in"))
      (node (ref "LED122") (pin "GND") (pinfunction "GND_GND") (pintype "power_in"))
      (node (ref "LED123") (pin "GND") (pinfunction "GND_GND") (pintype "power_in"))
      (node (ref "LED124") (pin "GND") (pinfunction "GND_GND") (pintype "power_in"))
      (node (ref "LED125") (pin "GND") (pinfunction "GND_GND") (pintype "power_in"))
      (node (ref "LED126") (pin "GND") (pinfunction "GND_GND") (pintype "power_in"))
      (node (ref "LED127") (pin "GND") (pinfunction "GND_GND") (pintype "power_in"))
      (node (ref "LED128") (pin "GND") (pinfunction "GND_GND") (pintype "power_in"))
      (node (ref "LED129") (pin "GND") (pinfunction "GND_GND") (pintype "power_in"))
      (node (ref "LED13") (pin "GND") (pinfunction "GND_GND") (pintype "power_in"))
      (node (ref "LED130") (pin "GND") (pinfunction "GND_GND") (pintype "power_in"))
      (node (ref "LED131") (pin "GND") (pinfunction "GND_GND") (pintype "power_in"))
      (node (ref "LED132") (pin "GND") (pinfunction "GND_GND") (pintype "power_in"))
      (node (ref "LED133") (pin "GND") (pinfunction "GND_GND") (pintype "power_in"))
      (node (ref "LED134") (pin "GND") (pinfunction "GND_GND") (pintype "power_in"))
      (node (ref "LED135") (pin "GND") (pinfunction "GND_GND") (pintype "power_in"))
      (node (ref "LED136") (pin "GND") (pinfunction "GND_GND") (pintype "power_in"))
      (node (ref "LED137") (pin "GND") (pinfunction "GND_GND") (pintype "power_in"))
      (node (ref "LED138") (pin "GND") (pinfunction "GND_GND") (pintype "power_in"))
      (node (ref "LED139") (pin "GND") (pinfunction "GND_GND") (pintype "power_in"))
      (node (ref "LED14") (pin "GND") (pinfunction "GND_GND") (pintype "power_in"))
      (node (ref "LED140") (pin "GND") (pinfunction "GND_GND") (pintype "power_in"))
      (node (ref "LED141") (pin "GND") (pinfunction "GND_GND") (pintype "power_in"))
      (node (ref "LED142") (pin "GND") (pinfunction "GND_GND") (pintype "power_in"))
      (node (ref "LED143") (pin "GND") (pinfunction "GND_GND") (pintype "power_in"))
      (node (ref "LED144") (pin "GND") (pinfunction "GND_GND") (pintype "power_in"))
      (node (ref "LED145") (pin "GND") (pinfunction "GND_GND") (pintype "power_in"))
      (node (ref "LED146") (pin "GND") (pinfunction "GND_GND") (pintype "power_in"))
      (node (ref "LED147") (pin "GND") (pinfunction "GND_GND") (pintype "power_in"))
      (node (ref "LED148") (pin "GND") (pinfunction "GND_GND") (pintype "power_in"))
      (node (ref "LED149") (pin "GND") (pinfunction "GND_GND") (pintype "power_in"))
      (node (ref "LED15") (pin "GND") (pinfunction "GND_GND") (pintype "power_in"))
      (node (ref "LED150") (pin "GND") (pinfunction "GND_GND") (pintype "power_in"))
      (node (ref "LED151") (pin "GND") (pinfunction "GND_GND") (pintype "power_in"))
      (node (ref "LED152") (pin "GND") (pinfunction "GND_GND") (pintype "power_in"))
      (node (ref "LED153") (pin "GND") (pinfunction "GND_GND") (pintype "power_in"))
      (node (ref "LED154") (pin "GND") (pinfunction "GND_GND") (pintype "power_in"))
      (node (ref "LED155") (pin "GND") (pinfunction "GND_GND") (pintype "power_in"))
      (node (ref "LED156") (pin "GND") (pinfunction "GND_GND") (pintype "power_in"))
      (node (ref "LED157") (pin "GND") (pinfunction "GND_GND") (pintype "power_in"))
      (node (ref "LED158") (pin "GND") (pinfunction "GND_GND") (pintype "power_in"))
      (node (ref "LED159") (pin "GND") (pinfunction "GND_GND") (pintype "power_in"))
      (node (ref "LED16") (pin "GND") (pinfunction "GND_GND") (pintype "power_in"))
      (node (ref "LED160") (pin "GND") (pinfunction "GND_GND") (pintype "power_in"))
      (node (ref "LED161") (pin "GND") (pinfunction "GND_GND") (pintype "power_in"))
      (node (ref "LED162") (pin "GND") (pinfunction "GND_GND") (pintype "power_in"))
      (node (ref "LED163") (pin "GND") (pinfunction "GND_GND") (pintype "power_in"))
      (node (ref "LED164") (pin "GND") (pinfunction "GND_GND") (pintype "power_in"))
      (node (ref "LED165") (pin "GND") (pinfunction "GND_GND") (pintype "power_in"))
      (node (ref "LED166") (pin "GND") (pinfunction "GND_GND") (pintype "power_in"))
      (node (ref "LED167") (pin "GND") (pinfunction "GND_GND") (pintype "power_in"))
      (node (ref "LED168") (pin "GND") (pinfunction "GND_GND") (pintype "power_in"))
      (node (ref "LED169") (pin "GND") (pinfunction "GND_GND") (pintype "power_in"))
      (node (ref "LED17") (pin "GND") (pinfunction "GND_GND") (pintype "power_in"))
      (node (ref "LED170") (pin "GND") (pinfunction "GND_GND") (pintype "power_in"))
      (node (ref "LED171") (pin "GND") (pinfunction "GND_GND") (pintype "power_in"))
      (node (ref "LED172") (pin "GND") (pinfunction "GND_GND") (pintype "power_in"))
      (node (ref "LED173") (pin "GND") (pinfunction "GND_GND") (pintype "power_in"))
      (node (ref "LED174") (pin "GND") (pinfunction "GND_GND") (pintype "power_in"))
      (node (ref "LED175") (pin "GND") (pinfunction "GND_GND") (pintype "power_in"))
      (node (ref "LED176") (pin "GND") (pinfunction "GND_GND") (pintype "power_in"))
      (node (ref "LED177") (pin "GND") (pinfunction "GND_GND") (pintype "power_in"))
      (node (ref "LED178") (pin "GND") (pinfunction "GND_GND") (pintype "power_in"))
      (node (ref "LED179") (pin "GND") (pinfunction "GND_GND") (pintype "power_in"))
      (node (ref "LED18") (pin "GND") (pinfunction "GND_GND") (pintype "power_in"))
      (node (ref "LED180") (pin "GND") (pinfunction "GND_GND") (pintype "power_in"))
      (node (ref "LED181") (pin "GND") (pinfunction "GND_GND") (pintype "power_in"))
      (node (ref "LED182") (pin "GND") (pinfunction "GND_GND") (pintype "power_in"))
      (node (ref "LED183") (pin "GND") (pinfunction "GND_GND") (pintype "power_in"))
      (node (ref "LED184") (pin "GND") (pinfunction "GND_GND") (pintype "power_in"))
      (node (ref "LED185") (pin "GND") (pinfunction "GND_GND") (pintype "power_in"))
      (node (ref "LED186") (pin "GND") (pinfunction "GND_GND") (pintype "power_in"))
      (node (ref "LED187") (pin "GND") (pinfunction "GND_GND") (pintype "power_in"))
      (node (ref "LED188") (pin "GND") (pinfunction "GND_GND") (pintype "power_in"))
      (node (ref "LED189") (pin "GND") (pinfunction "GND_GND") (pintype "power_in"))
      (node (ref "LED19") (pin "GND") (pinfunction "GND_GND") (pintype "power_in"))
      (node (ref "LED190") (pin "GND") (pinfunction "GND_GND") (pintype "power_in"))
      (node (ref "LED191") (pin "GND") (pinfunction "GND_GND") (pintype "power_in"))
      (node (ref "LED192") (pin "GND") (pinfunction "GND_GND") (pintype "power_in"))
      (node (ref "LED193") (pin "GND") (pinfunction "GND_GND") (pintype "power_in"))
      (node (ref "LED194") (pin "GND") (pinfunction "GND_GND") (pintype "power_in"))
      (node (ref "LED195") (pin "GND") (pinfunction "GND_GND") (pintype "power_in"))
      (node (ref "LED196") (pin "GND") (pinfunction "GND_GND") (pintype "power_in"))
      (node (ref "LED197") (pin "GND") (pinfunction "GND_GND") (pintype "power_in"))
      (node (ref "LED198") (pin "GND") (pinfunction "GND_GND") (pintype "power_in"))
      (node (ref "LED199") (pin "GND") (pinfunction "GND_GND") (pintype "power_in"))
      (node (ref "LED2") (pin "GND") (pinfunction "GND_GND") (pintype "power_in"))
      (node (ref "LED20") (pin "GND") (pinfunction "GND_GND") (pintype "power_in"))
      (node (ref "LED200") (pin "GND") (pinfunction "GND_GND") (pintype "power_in"))
      (node (ref "LED201") (pin "GND") (pinfunction "GND_GND") (pintype "power_in"))
      (node (ref "LED202") (pin "GND") (pinfunction "GND_GND") (pintype "power_in"))
      (node (ref "LED203") (pin "GND") (pinfunction "GND_GND") (pintype "power_in"))
      (node (ref "LED204") (pin "GND") (pinfunction "GND_GND") (pintype "power_in"))
      (node (ref "LED205") (pin "GND") (pinfunction "GND_GND") (pintype "power_in"))
      (node (ref "LED206") (pin "GND") (pinfunction "GND_GND") (pintype "power_in"))
      (node (ref "LED207") (pin "GND") (pinfunction "GND_GND") (pintype "power_in"))
      (node (ref "LED208") (pin "GND") (pinfunction "GND_GND") (pintype "power_in"))
      (node (ref "LED209") (pin "GND") (pinfunction "GND_GND") (pintype "power_in"))
      (node (ref "LED21") (pin "GND") (pinfunction "GND_GND") (pintype "power_in"))
      (node (ref "LED210") (pin "GND") (pinfunction "GND_GND") (pintype "power_in"))
      (node (ref "LED211") (pin "GND") (pinfunction "GND_GND") (pintype "power_in"))
      (node (ref "LED212") (pin "GND") (pinfunction "GND_GND") (pintype "power_in"))
      (node (ref "LED213") (pin "GND") (pinfunction "GND_GND") (pintype "power_in"))
      (node (ref "LED214") (pin "GND") (pinfunction "GND_GND") (pintype "power_in"))
      (node (ref "LED215") (pin "GND") (pinfunction "GND_GND") (pintype "power_in"))
      (node (ref "LED216") (pin "GND") (pinfunction "GND_GND") (pintype "power_in"))
      (node (ref "LED217") (pin "GND") (pinfunction "GND_GND") (pintype "power_in"))
      (node (ref "LED218") (pin "GND") (pinfunction "GND_GND") (pintype "power_in"))
      (node (ref "LED219") (pin "GND") (pinfunction "GND_GND") (pintype "power_in"))
      (node (ref "LED22") (pin "GND") (pinfunction "GND_GND") (pintype "power_in"))
      (node (ref "LED220") (pin "GND") (pinfunction "GND_GND") (pintype "power_in"))
      (node (ref "LED221") (pin "GND") (pinfunction "GND_GND") (pintype "power_in"))
      (node (ref "LED222") (pin "GND") (pinfunction "GND_GND") (pintype "power_in"))
      (node (ref "LED223") (pin "GND") (pinfunction "GND_GND") (pintype "power_in"))
      (node (ref "LED224") (pin "GND") (pinfunction "GND_GND") (pintype "power_in"))
      (node (ref "LED225") (pin "GND") (pinfunction "GND_GND") (pintype "power_in"))
      (node (ref "LED226") (pin "GND") (pinfunction "GND_GND") (pintype "power_in"))
      (node (ref "LED227") (pin "GND") (pinfunction "GND_GND") (pintype "power_in"))
      (node (ref "LED228") (pin "GND") (pinfunction "GND_GND") (pintype "power_in"))
      (node (ref "LED229") (pin "GND") (pinfunction "GND_GND") (pintype "power_in"))
      (node (ref "LED23") (pin "GND") (pinfunction "GND_GND") (pintype "power_in"))
      (node (ref "LED230") (pin "GND") (pinfunction "GND_GND") (pintype "power_in"))
      (node (ref "LED231") (pin "GND") (pinfunction "GND_GND") (pintype "power_in"))
      (node (ref "LED232") (pin "GND") (pinfunction "GND_GND") (pintype "power_in"))
      (node (ref "LED233") (pin "GND") (pinfunction "GND_GND") (pintype "power_in"))
      (node (ref "LED234") (pin "GND") (pinfunction "GND_GND") (pintype "power_in"))
      (node (ref "LED235") (pin "GND") (pinfunction "GND_GND") (pintype "power_in"))
      (node (ref "LED236") (pin "GND") (pinfunction "GND_GND") (pintype "power_in"))
      (node (ref "LED237") (pin "GND") (pinfunction "GND_GND") (pintype "power_in"))
      (node (ref "LED238") (pin "GND") (pinfunction "GND_GND") (pintype "power_in"))
      (node (ref "LED239") (pin "GND") (pinfunction "GND_GND") (pintype "power_in"))
      (node (ref "LED24") (pin "GND") (pinfunction "GND_GND") (pintype "power_in"))
      (node (ref "LED240") (pin "GND") (pinfunction "GND_GND") (pintype "power_in"))
      (node (ref "LED241") (pin "GND") (pinfunction "GND_GND") (pintype "power_in"))
      (node (ref "LED242") (pin "GND") (pinfunction "GND_GND") (pintype "power_in"))
      (node (ref "LED243") (pin "GND") (pinfunction "GND_GND") (pintype "power_in"))
      (node (ref "LED244") (pin "GND") (pinfunction "GND_GND") (pintype "power_in"))
      (node (ref "LED245") (pin "GND") (pinfunction "GND_GND") (pintype "power_in"))
      (node (ref "LED246") (pin "GND") (pinfunction "GND_GND") (pintype "power_in"))
      (node (ref "LED247") (pin "GND") (pinfunction "GND_GND") (pintype "power_in"))
      (node (ref "LED248") (pin "GND") (pinfunction "GND_GND") (pintype "power_in"))
      (node (ref "LED249") (pin "GND") (pinfunction "GND_GND") (pintype "power_in"))
      (node (ref "LED25") (pin "GND") (pinfunction "GND_GND") (pintype "power_in"))
      (node (ref "LED250") (pin "GND") (pinfunction "GND_GND") (pintype "power_in"))
      (node (ref "LED251") (pin "GND") (pinfunction "GND_GND") (pintype "power_in"))
      (node (ref "LED252") (pin "GND") (pinfunction "GND_GND") (pintype "power_in"))
      (node (ref "LED253") (pin "GND") (pinfunction "GND_GND") (pintype "power_in"))
      (node (ref "LED254") (pin "GND") (pinfunction "GND_GND") (pintype "power_in"))
      (node (ref "LED255") (pin "GND") (pinfunction "GND_GND") (pintype "power_in"))
      (node (ref "LED256") (pin "GND") (pinfunction "GND_GND") (pintype "power_in"))
      (node (ref "LED257") (pin "GND") (pinfunction "GND_GND") (pintype "power_in"))
      (node (ref "LED258") (pin "GND") (pinfunction "GND_GND") (pintype "power_in"))
      (node (ref "LED259") (pin "GND") (pinfunction "GND_GND") (pintype "power_in"))
      (node (ref "LED26") (pin "GND") (pinfunction "GND_GND") (pintype "power_in"))
      (node (ref "LED260") (pin "GND") (pinfunction "GND_GND") (pintype "power_in"))
      (node (ref "LED261") (pin "GND") (pinfunction "GND_GND") (pintype "power_in"))
      (node (ref "LED262") (pin "GND") (pinfunction "GND_GND") (pintype "power_in"))
      (node (ref "LED263") (pin "GND") (pinfunction "GND_GND") (pintype "power_in"))
      (node (ref "LED264") (pin "GND") (pinfunction "GND_GND") (pintype "power_in"))
      (node (ref "LED265") (pin "GND") (pinfunction "GND_GND") (pintype "power_in"))
      (node (ref "LED266") (pin "GND") (pinfunction "GND_GND") (pintype "power_in"))
      (node (ref "LED267") (pin "GND") (pinfunction "GND_GND") (pintype "power_in"))
      (node (ref "LED268") (pin "GND") (pinfunction "GND_GND") (pintype "power_in"))
      (node (ref "LED269") (pin "GND") (pinfunction "GND_GND") (pintype "power_in"))
      (node (ref "LED27") (pin "GND") (pinfunction "GND_GND") (pintype "power_in"))
      (node (ref "LED270") (pin "GND") (pinfunction "GND_GND") (pintype "power_in"))
      (node (ref "LED271") (pin "GND") (pinfunction "GND_GND") (pintype "power_in"))
      (node (ref "LED272") (pin "GND") (pinfunction "GND_GND") (pintype "power_in"))
      (node (ref "LED273") (pin "GND") (pinfunction "GND_GND") (pintype "power_in"))
      (node (ref "LED274") (pin "GND") (pinfunction "GND_GND") (pintype "power_in"))
      (node (ref "LED275") (pin "GND") (pinfunction "GND_GND") (pintype "power_in"))
      (node (ref "LED276") (pin "GND") (pinfunction "GND_GND") (pintype "power_in"))
      (node (ref "LED277") (pin "GND") (pinfunction "GND_GND") (pintype "power_in"))
      (node (ref "LED278") (pin "GND") (pinfunction "GND_GND") (pintype "power_in"))
      (node (ref "LED279") (pin "GND") (pinfunction "GND_GND") (pintype "power_in"))
      (node (ref "LED28") (pin "GND") (pinfunction "GND_GND") (pintype "power_in"))
      (node (ref "LED280") (pin "GND") (pinfunction "GND_GND") (pintype "power_in"))
      (node (ref "LED281") (pin "GND") (pinfunction "GND_GND") (pintype "power_in"))
      (node (ref "LED282") (pin "GND") (pinfunction "GND_GND") (pintype "power_in"))
      (node (ref "LED283") (pin "GND") (pinfunction "GND_GND") (pintype "power_in"))
      (node (ref "LED284") (pin "GND") (pinfunction "GND_GND") (pintype "power_in"))
      (node (ref "LED285") (pin "GND") (pinfunction "GND_GND") (pintype "power_in"))
      (node (ref "LED286") (pin "GND") (pinfunction "GND_GND") (pintype "power_in"))
      (node (ref "LED287") (pin "GND") (pinfunction "GND_GND") (pintype "power_in"))
      (node (ref "LED288") (pin "GND") (pinfunction "GND_GND") (pintype "power_in"))
      (node (ref "LED29") (pin "GND") (pinfunction "GND_GND") (pintype "power_in"))
      (node (ref "LED3") (pin "GND") (pinfunction "GND_GND") (pintype "power_in"))
      (node (ref "LED30") (pin "GND") (pinfunction "GND_GND") (pintype "power_in"))
      (node (ref "LED31") (pin "GND") (pinfunction "GND_GND") (pintype "power_in"))
      (node (ref "LED32") (pin "GND") (pinfunction "GND_GND") (pintype "power_in"))
      (node (ref "LED33") (pin "GND") (pinfunction "GND_GND") (pintype "power_in"))
      (node (ref "LED34") (pin "GND") (pinfunction "GND_GND") (pintype "power_in"))
      (node (ref "LED35") (pin "GND") (pinfunction "GND_GND") (pintype "power_in"))
      (node (ref "LED36") (pin "GND") (pinfunction "GND_GND") (pintype "power_in"))
      (node (ref "LED37") (pin "GND") (pinfunction "GND_GND") (pintype "power_in"))
      (node (ref "LED38") (pin "GND") (pinfunction "GND_GND") (pintype "power_in"))
      (node (ref "LED39") (pin "GND") (pinfunction "GND_GND") (pintype "power_in"))
      (node (ref "LED4") (pin "GND") (pinfunction "GND_GND") (pintype "power_in"))
      (node (ref "LED40") (pin "GND") (pinfunction "GND_GND") (pintype "power_in"))
      (node (ref "LED41") (pin "GND") (pinfunction "GND_GND") (pintype "power_in"))
      (node (ref "LED42") (pin "GND") (pinfunction "GND_GND") (pintype "power_in"))
      (node (ref "LED43") (pin "GND") (pinfunction "GND_GND") (pintype "power_in"))
      (node (ref "LED44") (pin "GND") (pinfunction "GND_GND") (pintype "power_in"))
      (node (ref "LED45") (pin "GND") (pinfunction "GND_GND") (pintype "power_in"))
      (node (ref "LED46") (pin "GND") (pinfunction "GND_GND") (pintype "power_in"))
      (node (ref "LED47") (pin "GND") (pinfunction "GND_GND") (pintype "power_in"))
      (node (ref "LED48") (pin "GND") (pinfunction "GND_GND") (pintype "power_in"))
      (node (ref "LED49") (pin "GND") (pinfunction "GND_GND") (pintype "power_in"))
      (node (ref "LED5") (pin "GND") (pinfunction "GND_GND") (pintype "power_in"))
      (node (ref "LED50") (pin "GND") (pinfunction "GND_GND") (pintype "power_in"))
      (node (ref "LED51") (pin "GND") (pinfunction "GND_GND") (pintype "power_in"))
      (node (ref "LED52") (pin "GND") (pinfunction "GND_GND") (pintype "power_in"))
      (node (ref "LED53") (pin "GND") (pinfunction "GND_GND") (pintype "power_in"))
      (node (ref "LED54") (pin "GND") (pinfunction "GND_GND") (pintype "power_in"))
      (node (ref "LED55") (pin "GND") (pinfunction "GND_GND") (pintype "power_in"))
      (node (ref "LED56") (pin "GND") (pinfunction "GND_GND") (pintype "power_in"))
      (node (ref "LED57") (pin "GND") (pinfunction "GND_GND") (pintype "power_in"))
      (node (ref "LED58") (pin "GND") (pinfunction "GND_GND") (pintype "power_in"))
      (node (ref "LED59") (pin "GND") (pinfunction "GND_GND") (pintype "power_in"))
      (node (ref "LED6") (pin "GND") (pinfunction "GND_GND") (pintype "power_in"))
      (node (ref "LED60") (pin "GND") (pinfunction "GND_GND") (pintype "power_in"))
      (node (ref "LED61") (pin "GND") (pinfunction "GND_GND") (pintype "power_in"))
      (node (ref "LED62") (pin "GND") (pinfunction "GND_GND") (pintype "power_in"))
      (node (ref "LED63") (pin "GND") (pinfunction "GND_GND") (pintype "power_in"))
      (node (ref "LED64") (pin "GND") (pinfunction "GND_GND") (pintype "power_in"))
      (node (ref "LED65") (pin "GND") (pinfunction "GND_GND") (pintype "power_in"))
      (node (ref "LED66") (pin "GND") (pinfunction "GND_GND") (pintype "power_in"))
      (node (ref "LED67") (pin "GND") (pinfunction "GND_GND") (pintype "power_in"))
      (node (ref "LED68") (pin "GND") (pinfunction "GND_GND") (pintype "power_in"))
      (node (ref "LED69") (pin "GND") (pinfunction "GND_GND") (pintype "power_in"))
      (node (ref "LED7") (pin "GND") (pinfunction "GND_GND") (pintype "power_in"))
      (node (ref "LED70") (pin "GND") (pinfunction "GND_GND") (pintype "power_in"))
      (node (ref "LED71") (pin "GND") (pinfunction "GND_GND") (pintype "power_in"))
      (node (ref "LED72") (pin "GND") (pinfunction "GND_GND") (pintype "power_in"))
      (node (ref "LED73") (pin "GND") (pinfunction "GND_GND") (pintype "power_in"))
      (node (ref "LED74") (pin "GND") (pinfunction "GND_GND") (pintype "power_in"))
      (node (ref "LED75") (pin "GND") (pinfunction "GND_GND") (pintype "power_in"))
      (node (ref "LED76") (pin "GND") (pinfunction "GND_GND") (pintype "power_in"))
      (node (ref "LED77") (pin "GND") (pinfunction "GND_GND") (pintype "power_in"))
      (node (ref "LED78") (pin "GND") (pinfunction "GND_GND") (pintype "power_in"))
      (node (ref "LED79") (pin "GND") (pinfunction "GND_GND") (pintype "power_in"))
      (node (ref "LED8") (pin "GND") (pinfunction "GND_GND") (pintype "power_in"))
      (node (ref "LED80") (pin "GND") (pinfunction "GND_GND") (pintype "power_in"))
      (node (ref "LED81") (pin "GND") (pinfunction "GND_GND") (pintype "power_in"))
      (node (ref "LED82") (pin "GND") (pinfunction "GND_GND") (pintype "power_in"))
      (node (ref "LED83") (pin "GND") (pinfunction "GND_GND") (pintype "power_in"))
      (node (ref "LED84") (pin "GND") (pinfunction "GND_GND") (pintype "power_in"))
      (node (ref "LED85") (pin "GND") (pinfunction "GND_GND") (pintype "power_in"))
      (node (ref "LED86") (pin "GND") (pinfunction "GND_GND") (pintype "power_in"))
      (node (ref "LED87") (pin "GND") (pinfunction "GND_GND") (pintype "power_in"))
      (node (ref "LED88") (pin "GND") (pinfunction "GND_GND") (pintype "power_in"))
      (node (ref "LED89") (pin "GND") (pinfunction "GND_GND") (pintype "power_in"))
      (node (ref "LED9") (pin "GND") (pinfunction "GND_GND") (pintype "power_in"))
      (node (ref "LED90") (pin "GND") (pinfunction "GND_GND") (pintype "power_in"))
      (node (ref "LED91") (pin "GND") (pinfunction "GND_GND") (pintype "power_in"))
      (node (ref "LED92") (pin "GND") (pinfunction "GND_GND") (pintype "power_in"))
      (node (ref "LED93") (pin "GND") (pinfunction "GND_GND") (pintype "power_in"))
      (node (ref "LED94") (pin "GND") (pinfunction "GND_GND") (pintype "power_in"))
      (node (ref "LED95") (pin "GND") (pinfunction "GND_GND") (pintype "power_in"))
      (node (ref "LED96") (pin "GND") (pinfunction "GND_GND") (pintype "power_in"))
      (node (ref "LED97") (pin "GND") (pinfunction "GND_GND") (pintype "power_in"))
      (node (ref "LED98") (pin "GND") (pinfunction "GND_GND") (pintype "power_in"))
      (node (ref "LED99") (pin "GND") (pinfunction "GND_GND") (pintype "power_in"))
    )
    (net (code "10") (name "GPIO0") (class "Default")
      (node (ref "J5") (pin "14") (pinfunction "14_14") (pintype "passive"))
    )
    (net (code "11") (name "GPIO1") (class "Default")
      (node (ref "J6") (pin "14") (pinfunction "14_14") (pintype "passive"))
    )
    (net (code "12") (name "GPIO2") (class "Default")
      (node (ref "J5") (pin "2") (pinfunction "2_2") (pintype "passive"))
    )
    (net (code "13") (name "GPIO3") (class "Default")
      (node (ref "J5") (pin "3") (pinfunction "3_3") (pintype "passive"))
    )
    (net (code "14") (name "GPIO4") (class "Default")
      (node (ref "J5") (pin "4") (pinfunction "4_4") (pintype "passive"))
    )
    (net (code "15") (name "GPIO5") (class "Default")
      (node (ref "J5") (pin "15") (pinfunction "15_15") (pintype "passive"))
    )
    (net (code "16") (name "GPIO6") (class "Default")
      (node (ref "J5") (pin "16") (pinfunction "16_16") (pintype "passive"))
    )
    (net (code "17") (name "GPIO7") (class "Default")
      (node (ref "J6") (pin "13") (pinfunction "13_13") (pintype "passive"))
    )
    (net (code "18") (name "GPIO8") (class "Default")
      (node (ref "J6") (pin "12") (pinfunction "12_12") (pintype "passive"))
    )
    (net (code "19") (name "GPIO9") (class "Default")
      (node (ref "J5") (pin "11") (pinfunction "11_11") (pintype "passive"))
    )
    (net (code "20") (name "GPIO10") (class "Default")
      (node (ref "J5") (pin "10") (pinfunction "10_10") (pintype "passive"))
      (node (ref "SJ1") (pin "3") (pinfunction "3_3") (pintype "passive"))
    )
    (net (code "21") (name "GPIO11") (class "Default")
      (node (ref "J5") (pin "12") (pinfunction "12_12") (pintype "passive"))
    )
    (net (code "22") (name "GPIO12") (class "Default")
      (node (ref "J6") (pin "16") (pinfunction "16_16") (pintype "passive"))
    )
    (net (code "23") (name "GPIO13") (class "Default")
      (node (ref "J5") (pin "17") (pinfunction "17_17") (pintype "passive"))
    )
    (net (code "24") (name "GPIO14") (class "Default")
      (node (ref "J6") (pin "4") (pinfunction "4_4") (pintype "passive"))
    )
    (net (code "25") (name "GPIO15") (class "Default")
      (node (ref "J6") (pin "5") (pinfunction "5_5") (pintype "passive"))
    )
    (net (code "26") (name "GPIO16") (class "Default")
      (node (ref "J6") (pin "18") (pinfunction "18_18") (pintype "passive"))
    )
    (net (code "27") (name "GPIO17") (class "Default")
      (node (ref "J5") (pin "6") (pinfunction "6_6") (pintype "passive"))
    )
    (net (code "28") (name "GPIO18") (class "Default")
      (node (ref "J6") (pin "6") (pinfunction "6_6") (pintype "passive"))
      (node (ref "SJ1") (pin "4") (pinfunction "4_4") (pintype "passive"))
    )
    (net (code "29") (name "GPIO19") (class "Default")
      (node (ref "J5") (pin "18") (pinfunction "18_18") (pintype "passive"))
    )
    (net (code "30") (name "GPIO20") (class "Default")
      (node (ref "J6") (pin "19") (pinfunction "19_19") (pintype "passive"))
    )
    (net (code "31") (name "GPIO21") (class "Default")
      (node (ref "J6") (pin "20") (pinfunction "20_20") (pintype "passive"))
      (node (ref "SJ1") (pin "1") (pinfunction "1_1") (pintype "passive"))
    )
    (net (code "32") (name "GPIO22") (class "Default")
      (node (ref "J5") (pin "8") (pinfunction "8_8") (pintype "passive"))
    )
    (net (code "33") (name "GPIO23") (class "Default")
      (node (ref "J6") (pin "8") (pinfunction "8_8") (pintype "passive"))
    )
    (net (code "34") (name "GPIO24") (class "Default")
      (node (ref "J6") (pin "9") (pinfunction "9_9") (pintype "passive"))
    )
    (net (code "35") (name "GPIO25") (class "Default")
      (node (ref "J6") (pin "11") (pinfunction "11_11") (pintype "passive"))
    )
    (net (code "36") (name "GPIO26") (class "Default")
      (node (ref "J5") (pin "19") (pinfunction "19_19") (pintype "passive"))
    )
    (net (code "37") (name "GPIO27") (class "Default")
      (node (ref "J5") (pin "7") (pinfunction "7_7") (pintype "passive"))
    )
    (net (code "38") (name "Net-(IC1-OE)") (class "Default")
      (node (ref "IC1") (pin "5") (pinfunction "OE_5") (pintype "input"))
      (node (ref "R1") (pin "2") (pinfunction "2_2") (pintype "passive"))
    )
    (net (code "39") (name "Net-(LED1-PadDO)") (class "Default")
      (node (ref "LED1") (pin "DO") (pinfunction "DO_DO") (pintype "output"))
      (node (ref "LED2") (pin "DI") (pinfunction "DI_DI") (pintype "input"))
    )
    (net (code "40") (name "Net-(LED2-PadDO)") (class "Default")
      (node (ref "LED2") (pin "DO") (pinfunction "DO_DO") (pintype "output"))
      (node (ref "LED3") (pin "DI") (pinfunction "DI_DI") (pintype "input"))
    )
    (net (code "41") (name "Net-(LED3-PadDO)") (class "Default")
      (node (ref "LED3") (pin "DO") (pinfunction "DO_DO") (pintype "output"))
      (node (ref "LED4") (pin "DI") (pinfunction "DI_DI") (pintype "input"))
    )
    (net (code "42") (name "Net-(LED4-PadDO)") (class "Default")
      (node (ref "LED4") (pin "DO") (pinfunction "DO_DO") (pintype "output"))
      (node (ref "LED5") (pin "DI") (pinfunction "DI_DI") (pintype "input"))
    )
    (net (code "43") (name "Net-(LED5-PadDO)") (class "Default")
      (node (ref "LED5") (pin "DO") (pinfunction "DO_DO") (pintype "output"))
      (node (ref "LED6") (pin "DI") (pinfunction "DI_DI") (pintype "input"))
    )
    (net (code "44") (name "Net-(LED6-PadDO)") (class "Default")
      (node (ref "LED6") (pin "DO") (pinfunction "DO_DO") (pintype "output"))
      (node (ref "LED7") (pin "DI") (pinfunction "DI_DI") (pintype "input"))
    )
    (net (code "45") (name "Net-(LED7-PadDO)") (class "Default")
      (node (ref "LED7") (pin "DO") (pinfunction "DO_DO") (pintype "output"))
      (node (ref "LED8") (pin "DI") (pinfunction "DI_DI") (pintype "input"))
    )
    (net (code "46") (name "Net-(LED8-PadDO)") (class "Default")
      (node (ref "LED8") (pin "DO") (pinfunction "DO_DO") (pintype "output"))
      (node (ref "LED9") (pin "DI") (pinfunction "DI_DI") (pintype "input"))
    )
    (net (code "47") (name "Net-(LED10-PadDI)") (class "Default")
      (node (ref "LED10") (pin "DI") (pinfunction "DI_DI") (pintype "input"))
      (node (ref "LED9") (pin "DO") (pinfunction "DO_DO") (pintype "output"))
    )
    (net (code "48") (name "Net-(LED10-PadDO)") (class "Default")
      (node (ref "LED10") (pin "DO") (pinfunction "DO_DO") (pintype "output"))
      (node (ref "LED11") (pin "DI") (pinfunction "DI_DI") (pintype "input"))
    )
    (net (code "49") (name "Net-(LED11-PadDO)") (class "Default")
      (node (ref "LED11") (pin "DO") (pinfunction "DO_DO") (pintype "output"))
      (node (ref "LED12") (pin "DI") (pinfunction "DI_DI") (pintype "input"))
    )
    (net (code "50") (name "Net-(LED12-PadDO)") (class "Default")
      (node (ref "LED12") (pin "DO") (pinfunction "DO_DO") (pintype "output"))
      (node (ref "LED13") (pin "DI") (pinfunction "DI_DI") (pintype "input"))
    )
    (net (code "51") (name "Net-(LED13-PadDO)") (class "Default")
      (node (ref "LED13") (pin "DO") (pinfunction "DO_DO") (pintype "output"))
      (node (ref "LED14") (pin "DI") (pinfunction "DI_DI") (pintype "input"))
    )
    (net (code "52") (name "Net-(LED14-PadDO)") (class "Default")
      (node (ref "LED14") (pin "DO") (pinfunction "DO_DO") (pintype "output"))
      (node (ref "LED15") (pin "DI") (pinfunction "DI_DI") (pintype "input"))
    )
    (net (code "53") (name "Net-(LED15-PadDO)") (class "Default")
      (node (ref "LED15") (pin "DO") (pinfunction "DO_DO") (pintype "output"))
      (node (ref "LED16") (pin "DI") (pinfunction "DI_DI") (pintype "input"))
    )
    (net (code "54") (name "Net-(LED16-PadDO)") (class "Default")
      (node (ref "LED16") (pin "DO") (pinfunction "DO_DO") (pintype "output"))
      (node (ref "LED17") (pin "DI") (pinfunction "DI_DI") (pintype "input"))
    )
    (net (code "55") (name "Net-(LED17-PadDO)") (class "Default")
      (node (ref "LED17") (pin "DO") (pinfunction "DO_DO") (pintype "output"))
      (node (ref "LED18") (pin "DI") (pinfunction "DI_DI") (pintype "input"))
    )
    (net (code "56") (name "Net-(LED18-PadDO)") (class "Default")
      (node (ref "LED18") (pin "DO") (pinfunction "DO_DO") (pintype "output"))
      (node (ref "LED19") (pin "DI") (pinfunction "DI_DI") (pintype "input"))
    )
    (net (code "57") (name "Net-(LED19-PadDO)") (class "Default")
      (node (ref "LED19") (pin "DO") (pinfunction "DO_DO") (pintype "output"))
      (node (ref "LED20") (pin "DI") (pinfunction "DI_DI") (pintype "input"))
    )
    (net (code "58") (name "Net-(LED20-PadDO)") (class "Default")
      (node (ref "LED20") (pin "DO") (pinfunction "DO_DO") (pintype "output"))
      (node (ref "LED21") (pin "DI") (pinfunction "DI_DI") (pintype "input"))
    )
    (net (code "59") (name "Net-(LED21-PadDO)") (class "Default")
      (node (ref "LED21") (pin "DO") (pinfunction "DO_DO") (pintype "output"))
      (node (ref "LED22") (pin "DI") (pinfunction "DI_DI") (pintype "input"))
    )
    (net (code "60") (name "Net-(LED22-PadDO)") (class "Default")
      (node (ref "LED22") (pin "DO") (pinfunction "DO_DO") (pintype "output"))
      (node (ref "LED23") (pin "DI") (pinfunction "DI_DI") (pintype "input"))
    )
    (net (code "61") (name "Net-(LED23-PadDO)") (class "Default")
      (node (ref "LED23") (pin "DO") (pinfunction "DO_DO") (pintype "output"))
      (node (ref "LED24") (pin "DI") (pinfunction "DI_DI") (pintype "input"))
    )
    (net (code "62") (name "Net-(LED24-PadDO)") (class "Default")
      (node (ref "LED24") (pin "DO") (pinfunction "DO_DO") (pintype "output"))
      (node (ref "LED25") (pin "DI") (pinfunction "DI_DI") (pintype "input"))
    )
    (net (code "63") (name "Net-(LED25-PadDO)") (class "Default")
      (node (ref "LED25") (pin "DO") (pinfunction "DO_DO") (pintype "output"))
      (node (ref "LED26") (pin "DI") (pinfunction "DI_DI") (pintype "input"))
    )
    (net (code "64") (name "Net-(LED26-PadDO)") (class "Default")
      (node (ref "LED26") (pin "DO") (pinfunction "DO_DO") (pintype "output"))
      (node (ref "LED27") (pin "DI") (pinfunction "DI_DI") (pintype "input"))
    )
    (net (code "65") (name "Net-(LED27-PadDO)") (class "Default")
      (node (ref "LED27") (pin "DO") (pinfunction "DO_DO") (pintype "output"))
      (node (ref "LED28") (pin "DI") (pinfunction "DI_DI") (pintype "input"))
    )
    (net (code "66") (name "Net-(LED28-PadDO)") (class "Default")
      (node (ref "LED28") (pin "DO") (pinfunction "DO_DO") (pintype "output"))
      (node (ref "LED29") (pin "DI") (pinfunction "DI_DI") (pintype "input"))
    )
    (net (code "67") (name "Net-(LED29-PadDO)") (class "Default")
      (node (ref "LED29") (pin "DO") (pinfunction "DO_DO") (pintype "output"))
      (node (ref "LED30") (pin "DI") (pinfunction "DI_DI") (pintype "input"))
    )
    (net (code "68") (name "Net-(LED30-PadDO)") (class "Default")
      (node (ref "LED30") (pin "DO") (pinfunction "DO_DO") (pintype "output"))
      (node (ref "LED31") (pin "DI") (pinfunction "DI_DI") (pintype "input"))
    )
    (net (code "69") (name "Net-(LED31-PadDO)") (class "Default")
      (node (ref "LED31") (pin "DO") (pinfunction "DO_DO") (pintype "output"))
      (node (ref "LED32") (pin "DI") (pinfunction "DI_DI") (pintype "input"))
    )
    (net (code "70") (name "Net-(LED32-PadDO)") (class "Default")
      (node (ref "LED32") (pin "DO") (pinfunction "DO_DO") (pintype "output"))
      (node (ref "LED33") (pin "DI") (pinfunction "DI_DI") (pintype "input"))
    )
    (net (code "71") (name "Net-(LED33-PadDO)") (class "Default")
      (node (ref "LED33") (pin "DO") (pinfunction "DO_DO") (pintype "output"))
      (node (ref "LED34") (pin "DI") (pinfunction "DI_DI") (pintype "input"))
    )
    (net (code "72") (name "Net-(LED34-PadDO)") (class "Default")
      (node (ref "LED34") (pin "DO") (pinfunction "DO_DO") (pintype "output"))
      (node (ref "LED35") (pin "DI") (pinfunction "DI_DI") (pintype "input"))
    )
    (net (code "73") (name "Net-(LED35-PadDO)") (class "Default")
      (node (ref "LED35") (pin "DO") (pinfunction "DO_DO") (pintype "output"))
      (node (ref "LED36") (pin "DI") (pinfunction "DI_DI") (pintype "input"))
    )
    (net (code "74") (name "Net-(LED36-PadDO)") (class "Default")
      (node (ref "LED36") (pin "DO") (pinfunction "DO_DO") (pintype "output"))
      (node (ref "LED37") (pin "DI") (pinfunction "DI_DI") (pintype "input"))
    )
    (net (code "75") (name "Net-(LED37-PadDO)") (class "Default")
      (node (ref "LED37") (pin "DO") (pinfunction "DO_DO") (pintype "output"))
      (node (ref "LED38") (pin "DI") (pinfunction "DI_DI") (pintype "input"))
    )
    (net (code "76") (name "Net-(LED38-PadDO)") (class "Default")
      (node (ref "LED38") (pin "DO") (pinfunction "DO_DO") (pintype "output"))
      (node (ref "LED39") (pin "DI") (pinfunction "DI_DI") (pintype "input"))
    )
    (net (code "77") (name "Net-(LED39-PadDO)") (class "Default")
      (node (ref "LED39") (pin "DO") (pinfunction "DO_DO") (pintype "output"))
      (node (ref "LED40") (pin "DI") (pinfunction "DI_DI") (pintype "input"))
    )
    (net (code "78") (name "Net-(LED40-PadDO)") (class "Default")
      (node (ref "LED40") (pin "DO") (pinfunction "DO_DO") (pintype "output"))
      (node (ref "LED41") (pin "DI") (pinfunction "DI_DI") (pintype "input"))
    )
    (net (code "79") (name "Net-(LED41-PadDO)") (class "Default")
      (node (ref "LED41") (pin "DO") (pinfunction "DO_DO") (pintype "output"))
      (node (ref "LED42") (pin "DI") (pinfunction "DI_DI") (pintype "input"))
    )
    (net (code "80") (name "Net-(LED42-PadDO)") (class "Default")
      (node (ref "LED42") (pin "DO") (pinfunction "DO_DO") (pintype "output"))
      (node (ref "LED43") (pin "DI") (pinfunction "DI_DI") (pintype "input"))
    )
    (net (code "81") (name "Net-(LED43-PadDO)") (class "Default")
      (node (ref "LED43") (pin "DO") (pinfunction "DO_DO") (pintype "output"))
      (node (ref "LED44") (pin "DI") (pinfunction "DI_DI") (pintype "input"))
    )
    (net (code "82") (name "Net-(LED44-PadDO)") (class "Default")
      (node (ref "LED44") (pin "DO") (pinfunction "DO_DO") (pintype "output"))
      (node (ref "LED45") (pin "DI") (pinfunction "DI_DI") (pintype "input"))
    )
    (net (code "83") (name "Net-(LED45-PadDO)") (class "Default")
      (node (ref "LED45") (pin "DO") (pinfunction "DO_DO") (pintype "output"))
      (node (ref "LED46") (pin "DI") (pinfunction "DI_DI") (pintype "input"))
    )
    (net (code "84") (name "Net-(LED46-PadDO)") (class "Default")
      (node (ref "LED46") (pin "DO") (pinfunction "DO_DO") (pintype "output"))
      (node (ref "LED47") (pin "DI") (pinfunction "DI_DI") (pintype "input"))
    )
    (net (code "85") (name "Net-(LED47-PadDO)") (class "Default")
      (node (ref "LED47") (pin "DO") (pinfunction "DO_DO") (pintype "output"))
      (node (ref "LED48") (pin "DI") (pinfunction "DI_DI") (pintype "input"))
    )
    (net (code "86") (name "Net-(LED48-PadDO)") (class "Default")
      (node (ref "LED48") (pin "DO") (pinfunction "DO_DO") (pintype "output"))
      (node (ref "LED49") (pin "DI") (pinfunction "DI_DI") (pintype "input"))
    )
    (net (code "87") (name "Net-(LED49-PadDO)") (class "Default")
      (node (ref "LED49") (pin "DO") (pinfunction "DO_DO") (pintype "output"))
      (node (ref "LED50") (pin "DI") (pinfunction "DI_DI") (pintype "input"))
    )
    (net (code "88") (name "Net-(LED50-PadDO)") (class "Default")
      (node (ref "LED50") (pin "DO") (pinfunction "DO_DO") (pintype "output"))
      (node (ref "LED51") (pin "DI") (pinfunction "DI_DI") (pintype "input"))
    )
    (net (code "89") (name "Net-(LED51-PadDO)") (class "Default")
      (node (ref "LED51") (pin "DO") (pinfunction "DO_DO") (pintype "output"))
      (node (ref "LED52") (pin "DI") (pinfunction "DI_DI") (pintype "input"))
    )
    (net (code "90") (name "Net-(LED52-PadDO)") (class "Default")
      (node (ref "LED52") (pin "DO") (pinfunction "DO_DO") (pintype "output"))
      (node (ref "LED53") (pin "DI") (pinfunction "DI_DI") (pintype "input"))
    )
    (net (code "91") (name "Net-(LED53-PadDO)") (class "Default")
      (node (ref "LED53") (pin "DO") (pinfunction "DO_DO") (pintype "output"))
      (node (ref "LED54") (pin "DI") (pinfunction "DI_DI") (pintype "input"))
    )
    (net (code "92") (name "Net-(LED54-PadDO)") (class "Default")
      (node (ref "LED54") (pin "DO") (pinfunction "DO_DO") (pintype "output"))
      (node (ref "LED55") (pin "DI") (pinfunction "DI_DI") (pintype "input"))
    )
    (net (code "93") (name "Net-(LED55-PadDO)") (class "Default")
      (node (ref "LED55") (pin "DO") (pinfunction "DO_DO") (pintype "output"))
      (node (ref "LED56") (pin "DI") (pinfunction "DI_DI") (pintype "input"))
    )
    (net (code "94") (name "Net-(LED56-PadDO)") (class "Default")
      (node (ref "LED56") (pin "DO") (pinfunction "DO_DO") (pintype "output"))
      (node (ref "LED57") (pin "DI") (pinfunction "DI_DI") (pintype "input"))
    )
    (net (code "95") (name "Net-(LED57-PadDO)") (class "Default")
      (node (ref "LED57") (pin "DO") (pinfunction "DO_DO") (pintype "output"))
      (node (ref "LED58") (pin "DI") (pinfunction "DI_DI") (pintype "input"))
    )
    (net (code "96") (name "Net-(LED58-PadDO)") (class "Default")
      (node (ref "LED58") (pin "DO") (pinfunction "DO_DO") (pintype "output"))
      (node (ref "LED59") (pin "DI") (pinfunction "DI_DI") (pintype "input"))
    )
    (net (code "97") (name "Net-(LED59-PadDO)") (class "Default")
      (node (ref "LED59") (pin "DO") (pinfunction "DO_DO") (pintype "output"))
      (node (ref "LED60") (pin "DI") (pinfunction "DI_DI") (pintype "input"))
    )
    (net (code "98") (name "Net-(LED60-PadDO)") (class "Default")
      (node (ref "LED60") (pin "DO") (pinfunction "DO_DO") (pintype "output"))
      (node (ref "LED61") (pin "DI") (pinfunction "DI_DI") (pintype "input"))
    )
    (net (code "99") (name "Net-(LED61-PadDO)") (class "Default")
      (node (ref "LED61") (pin "DO") (pinfunction "DO_DO") (pintype "output"))
      (node (ref "LED62") (pin "DI") (pinfunction "DI_DI") (pintype "input"))
    )
    (net (code "100") (name "Net-(LED62-PadDO)") (class "Default")
      (node (ref "LED62") (pin "DO") (pinfunction "DO_DO") (pintype "output"))
      (node (ref "LED63") (pin "DI") (pinfunction "DI_DI") (pintype "input"))
    )
    (net (code "101") (name "Net-(LED63-PadDO)") (class "Default")
      (node (ref "LED63") (pin "DO") (pinfunction "DO_DO") (pintype "output"))
      (node (ref "LED64") (pin "DI") (pinfunction "DI_DI") (pintype "input"))
    )
    (net (code "102") (name "Net-(LED64-PadDO)") (class "Default")
      (node (ref "LED64") (pin "DO") (pinfunction "DO_DO") (pintype "output"))
      (node (ref "LED65") (pin "DI") (pinfunction "DI_DI") (pintype "input"))
    )
    (net (code "103") (name "Net-(LED65-PadDO)") (class "Default")
      (node (ref "LED65") (pin "DO") (pinfunction "DO_DO") (pintype "output"))
      (node (ref "LED66") (pin "DI") (pinfunction "DI_DI") (pintype "input"))
    )
    (net (code "104") (name "Net-(LED66-PadDO)") (class "Default")
      (node (ref "LED66") (pin "DO") (pinfunction "DO_DO") (pintype "output"))
      (node (ref "LED67") (pin "DI") (pinfunction "DI_DI") (pintype "input"))
    )
    (net (code "105") (name "Net-(LED67-PadDO)") (class "Default")
      (node (ref "LED67") (pin "DO") (pinfunction "DO_DO") (pintype "output"))
      (node (ref "LED68") (pin "DI") (pinfunction "DI_DI") (pintype "input"))
    )
    (net (code "106") (name "Net-(LED68-PadDO)") (class "Default")
      (node (ref "LED68") (pin "DO") (pinfunction "DO_DO") (pintype "output"))
      (node (ref "LED69") (pin "DI") (pinfunction "DI_DI") (pintype "input"))
    )
    (net (code "107") (name "Net-(LED69-PadDO)") (class "Default")
      (node (ref "LED69") (pin "DO") (pinfunction "DO_DO") (pintype "output"))
      (node (ref "LED70") (pin "DI") (pinfunction "DI_DI") (pintype "input"))
    )
    (net (code "108") (name "Net-(LED70-PadDO)") (class "Default")
      (node (ref "LED70") (pin "DO") (pinfunction "DO_DO") (pintype "output"))
      (node (ref "LED71") (pin "DI") (pinfunction "DI_DI") (pintype "input"))
    )
    (net (code "109") (name "Net-(LED71-PadDO)") (class "Default")
      (node (ref "LED71") (pin "DO") (pinfunction "DO_DO") (pintype "output"))
      (node (ref "LED72") (pin "DI") (pinfunction "DI_DI") (pintype "input"))
    )
    (net (code "110") (name "Net-(LED73-PadDO)") (class "Default")
      (node (ref "LED73") (pin "DO") (pinfunction "DO_DO") (pintype "output"))
      (node (ref "LED74") (pin "DI") (pinfunction "DI_DI") (pintype "input"))
    )
    (net (code "111") (name "Net-(LED74-PadDO)") (class "Default")
      (node (ref "LED74") (pin "DO") (pinfunction "DO_DO") (pintype "output"))
      (node (ref "LED75") (pin "DI") (pinfunction "DI_DI") (pintype "input"))
    )
    (net (code "112") (name "Net-(LED75-PadDO)") (class "Default")
      (node (ref "LED75") (pin "DO") (pinfunction "DO_DO") (pintype "output"))
      (node (ref "LED76") (pin "DI") (pinfunction "DI_DI") (pintype "input"))
    )
    (net (code "113") (name "Net-(LED76-PadDO)") (class "Default")
      (node (ref "LED76") (pin "DO") (pinfunction "DO_DO") (pintype "output"))
      (node (ref "LED77") (pin "DI") (pinfunction "DI_DI") (pintype "input"))
    )
    (net (code "114") (name "Net-(LED77-PadDO)") (class "Default")
      (node (ref "LED77") (pin "DO") (pinfunction "DO_DO") (pintype "output"))
      (node (ref "LED78") (pin "DI") (pinfunction "DI_DI") (pintype "input"))
    )
    (net (code "115") (name "Net-(LED78-PadDO)") (class "Default")
      (node (ref "LED78") (pin "DO") (pinfunction "DO_DO") (pintype "output"))
      (node (ref "LED79") (pin "DI") (pinfunction "DI_DI") (pintype "input"))
    )
    (net (code "116") (name "Net-(LED79-PadDO)") (class "Default")
      (node (ref "LED79") (pin "DO") (pinfunction "DO_DO") (pintype "output"))
      (node (ref "LED80") (pin "DI") (pinfunction "DI_DI") (pintype "input"))
    )
    (net (code "117") (name "Net-(LED80-PadDO)") (class "Default")
      (node (ref "LED80") (pin "DO") (pinfunction "DO_DO") (pintype "output"))
      (node (ref "LED81") (pin "DI") (pinfunction "DI_DI") (pintype "input"))
    )
    (net (code "118") (name "Net-(LED81-PadDO)") (class "Default")
      (node (ref "LED81") (pin "DO") (pinfunction "DO_DO") (pintype "output"))
      (node (ref "LED82") (pin "DI") (pinfunction "DI_DI") (pintype "input"))
    )
    (net (code "119") (name "Net-(LED82-PadDO)") (class "Default")
      (node (ref "LED82") (pin "DO") (pinfunction "DO_DO") (pintype "output"))
      (node (ref "LED83") (pin "DI") (pinfunction "DI_DI") (pintype "input"))
    )
    (net (code "120") (name "Net-(LED83-PadDO)") (class "Default")
      (node (ref "LED83") (pin "DO") (pinfunction "DO_DO") (pintype "output"))
      (node (ref "LED84") (pin "DI") (pinfunction "DI_DI") (pintype "input"))
    )
    (net (code "121") (name "Net-(LED84-PadDO)") (class "Default")
      (node (ref "LED84") (pin "DO") (pinfunction "DO_DO") (pintype "output"))
      (node (ref "LED85") (pin "DI") (pinfunction "DI_DI") (pintype "input"))
    )
    (net (code "122") (name "Net-(LED85-PadDO)") (class "Default")
      (node (ref "LED85") (pin "DO") (pinfunction "DO_DO") (pintype "output"))
      (node (ref "LED86") (pin "DI") (pinfunction "DI_DI") (pintype "input"))
    )
    (net (code "123") (name "Net-(LED86-PadDO)") (class "Default")
      (node (ref "LED86") (pin "DO") (pinfunction "DO_DO") (pintype "output"))
      (node (ref "LED87") (pin "DI") (pinfunction "DI_DI") (pintype "input"))
    )
    (net (code "124") (name "Net-(LED87-PadDO)") (class "Default")
      (node (ref "LED87") (pin "DO") (pinfunction "DO_DO") (pintype "output"))
      (node (ref "LED88") (pin "DI") (pinfunction "DI_DI") (pintype "input"))
    )
    (net (code "125") (name "Net-(LED88-PadDO)") (class "Default")
      (node (ref "LED88") (pin "DO") (pinfunction "DO_DO") (pintype "output"))
      (node (ref "LED89") (pin "DI") (pinfunction "DI_DI") (pintype "input"))
    )
    (net (code "126") (name "Net-(LED89-PadDO)") (class "Default")
      (node (ref "LED89") (pin "DO") (pinfunction "DO_DO") (pintype "output"))
      (node (ref "LED90") (pin "DI") (pinfunction "DI_DI") (pintype "input"))
    )
    (net (code "127") (name "Net-(LED90-PadDO)") (class "Default")
      (node (ref "LED90") (pin "DO") (pinfunction "DO_DO") (pintype "output"))
      (node (ref "LED91") (pin "DI") (pinfunction "DI_DI") (pintype "input"))
    )
    (net (code "128") (name "Net-(LED91-PadDO)") (class "Default")
      (node (ref "LED91") (pin "DO") (pinfunction "DO_DO") (pintype "output"))
      (node (ref "LED92") (pin "DI") (pinfunction "DI_DI") (pintype "input"))
    )
    (net (code "129") (name "Net-(LED92-PadDO)") (class "Default")
      (node (ref "LED92") (pin "DO") (pinfunction "DO_DO") (pintype "output"))
      (node (ref "LED93") (pin "DI") (pinfunction "DI_DI") (pintype "input"))
    )
    (net (code "130") (name "Net-(LED93-PadDO)") (class "Default")
      (node (ref "LED93") (pin "DO") (pinfunction "DO_DO") (pintype "output"))
      (node (ref "LED94") (pin "DI") (pinfunction "DI_DI") (pintype "input"))
    )
    (net (code "131") (name "Net-(LED94-PadDO)") (class "Default")
      (node (ref "LED94") (pin "DO") (pinfunction "DO_DO") (pintype "output"))
      (node (ref "LED95") (pin "DI") (pinfunction "DI_DI") (pintype "input"))
    )
    (net (code "132") (name "Net-(LED95-PadDO)") (class "Default")
      (node (ref "LED95") (pin "DO") (pinfunction "DO_DO") (pintype "output"))
      (node (ref "LED96") (pin "DI") (pinfunction "DI_DI") (pintype "input"))
    )
    (net (code "133") (name "Net-(LED96-PadDO)") (class "Default")
      (node (ref "LED96") (pin "DO") (pinfunction "DO_DO") (pintype "output"))
      (node (ref "LED97") (pin "DI") (pinfunction "DI_DI") (pintype "input"))
    )
    (net (code "134") (name "Net-(LED97-PadDO)") (class "Default")
      (node (ref "LED97") (pin "DO") (pinfunction "DO_DO") (pintype "output"))
      (node (ref "LED98") (pin "DI") (pinfunction "DI_DI") (pintype "input"))
    )
    (net (code "135") (name "Net-(LED98-PadDO)") (class "Default")
      (node (ref "LED98") (pin "DO") (pinfunction "DO_DO") (pintype "output"))
      (node (ref "LED99") (pin "DI") (pinfunction "DI_DI") (pintype "input"))
    )
    (net (code "136") (name "Net-(LED100-PadDI)") (class "Default")
      (node (ref "LED100") (pin "DI") (pinfunction "DI_DI") (pintype "input"))
      (node (ref "LED99") (pin "DO") (pinfunction "DO_DO") (pintype "output"))
    )
    (net (code "137") (name "Net-(LED100-PadDO)") (class "Default")
      (node (ref "LED100") (pin "DO") (pinfunction "DO_DO") (pintype "output"))
      (node (ref "LED101") (pin "DI") (pinfunction "DI_DI") (pintype "input"))
    )
    (net (code "138") (name "Net-(LED101-PadDO)") (class "Default")
      (node (ref "LED101") (pin "DO") (pinfunction "DO_DO") (pintype "output"))
      (node (ref "LED102") (pin "DI") (pinfunction "DI_DI") (pintype "input"))
    )
    (net (code "139") (name "Net-(LED102-PadDO)") (class "Default")
      (node (ref "LED102") (pin "DO") (pinfunction "DO_DO") (pintype "output"))
      (node (ref "LED103") (pin "DI") (pinfunction "DI_DI") (pintype "input"))
    )
    (net (code "140") (name "Net-(LED103-PadDO)") (class "Default")
      (node (ref "LED103") (pin "DO") (pinfunction "DO_DO") (pintype "output"))
      (node (ref "LED104") (pin "DI") (pinfunction "DI_DI") (pintype "input"))
    )
    (net (code "141") (name "Net-(LED104-PadDO)") (class "Default")
      (node (ref "LED104") (pin "DO") (pinfunction "DO_DO") (pintype "output"))
      (node (ref "LED105") (pin "DI") (pinfunction "DI_DI") (pintype "input"))
    )
    (net (code "142") (name "Net-(LED105-PadDO)") (class "Default")
      (node (ref "LED105") (pin "DO") (pinfunction "DO_DO") (pintype "output"))
      (node (ref "LED106") (pin "DI") (pinfunction "DI_DI") (pintype "input"))
    )
    (net (code "143") (name "Net-(LED106-PadDO)") (class "Default")
      (node (ref "LED106") (pin "DO") (pinfunction "DO_DO") (pintype "output"))
      (node (ref "LED107") (pin "DI") (pinfunction "DI_DI") (pintype "input"))
    )
    (net (code "144") (name "Net-(LED107-PadDO)") (class "Default")
      (node (ref "LED107") (pin "DO") (pinfunction "DO_DO") (pintype "output"))
      (node (ref "LED108") (pin "DI") (pinfunction "DI_DI") (pintype "input"))
    )
    (net (code "145") (name "Net-(LED108-PadDO)") (class "Default")
      (node (ref "LED108") (pin "DO") (pinfunction "DO_DO") (pintype "output"))
      (node (ref "LED109") (pin "DI") (pinfunction "DI_DI") (pintype "input"))
    )
    (net (code "146") (name "Net-(LED109-PadDO)") (class "Default")
      (node (ref "LED109") (pin "DO") (pinfunction "DO_DO") (pintype "output"))
      (node (ref "LED110") (pin "DI") (pinfunction "DI_DI") (pintype "input"))
    )
    (net (code "147") (name "Net-(LED110-PadDO)") (class "Default")
      (node (ref "LED110") (pin "DO") (pinfunction "DO_DO") (pintype "output"))
      (node (ref "LED111") (pin "DI") (pinfunction "DI_DI") (pintype "input"))
    )
    (net (code "148") (name "Net-(LED111-PadDO)") (class "Default")
      (node (ref "LED111") (pin "DO") (pinfunction "DO_DO") (pintype "output"))
      (node (ref "LED112") (pin "DI") (pinfunction "DI_DI") (pintype "input"))
    )
    (net (code "149") (name "Net-(LED112-PadDO)") (class "Default")
      (node (ref "LED112") (pin "DO") (pinfunction "DO_DO") (pintype "output"))
      (node (ref "LED113") (pin "DI") (pinfunction "DI_DI") (pintype "input"))
    )
    (net (code "150") (name "Net-(LED113-PadDO)") (class "Default")
      (node (ref "LED113") (pin "DO") (pinfunction "DO_DO") (pintype "output"))
      (node (ref "LED114") (pin "DI") (pinfunction "DI_DI") (pintype "input"))
    )
    (net (code "151") (name "Net-(LED114-PadDO)") (class "Default")
      (node (ref "LED114") (pin "DO") (pinfunction "DO_DO") (pintype "output"))
      (node (ref "LED115") (pin "DI") (pinfunction "DI_DI") (pintype "input"))
    )
    (net (code "152") (name "Net-(LED115-PadDO)") (class "Default")
      (node (ref "LED115") (pin "DO") (pinfunction "DO_DO") (pintype "output"))
      (node (ref "LED116") (pin "DI") (pinfunction "DI_DI") (pintype "input"))
    )
    (net (code "153") (name "Net-(LED116-PadDO)") (class "Default")
      (node (ref "LED116") (pin "DO") (pinfunction "DO_DO") (pintype "output"))
      (node (ref "LED117") (pin "DI") (pinfunction "DI_DI") (pintype "input"))
    )
    (net (code "154") (name "Net-(LED117-PadDO)") (class "Default")
      (node (ref "LED117") (pin "DO") (pinfunction "DO_DO") (pintype "output"))
      (node (ref "LED118") (pin "DI") (pinfunction "DI_DI") (pintype "input"))
    )
    (net (code "155") (name "Net-(LED118-PadDO)") (class "Default")
      (node (ref "LED118") (pin "DO") (pinfunction "DO_DO") (pintype "output"))
      (node (ref "LED119") (pin "DI") (pinfunction "DI_DI") (pintype "input"))
    )
    (net (code "156") (name "Net-(LED119-PadDO)") (class "Default")
      (node (ref "LED119") (pin "DO") (pinfunction "DO_DO") (pintype "output"))
      (node (ref "LED120") (pin "DI") (pinfunction "DI_DI") (pintype "input"))
    )
    (net (code "157") (name "Net-(LED120-PadDO)") (class "Default")
      (node (ref "LED120") (pin "DO") (pinfunction "DO_DO") (pintype "output"))
      (node (ref "LED121") (pin "DI") (pinfunction "DI_DI") (pintype "input"))
    )
    (net (code "158") (name "Net-(LED121-PadDO)") (class "Default")
      (node (ref "LED121") (pin "DO") (pinfunction "DO_DO") (pintype "output"))
      (node (ref "LED122") (pin "DI") (pinfunction "DI_DI") (pintype "input"))
    )
    (net (code "159") (name "Net-(LED122-PadDO)") (class "Default")
      (node (ref "LED122") (pin "DO") (pinfunction "DO_DO") (pintype "output"))
      (node (ref "LED123") (pin "DI") (pinfunction "DI_DI") (pintype "input"))
    )
    (net (code "160") (name "Net-(LED123-PadDO)") (class "Default")
      (node (ref "LED123") (pin "DO") (pinfunction "DO_DO") (pintype "output"))
      (node (ref "LED124") (pin "DI") (pinfunction "DI_DI") (pintype "input"))
    )
    (net (code "161") (name "Net-(LED124-PadDO)") (class "Default")
      (node (ref "LED124") (pin "DO") (pinfunction "DO_DO") (pintype "output"))
      (node (ref "LED125") (pin "DI") (pinfunction "DI_DI") (pintype "input"))
    )
    (net (code "162") (name "Net-(LED125-PadDO)") (class "Default")
      (node (ref "LED125") (pin "DO") (pinfunction "DO_DO") (pintype "output"))
      (node (ref "LED126") (pin "DI") (pinfunction "DI_DI") (pintype "input"))
    )
    (net (code "163") (name "Net-(LED126-PadDO)") (class "Default")
      (node (ref "LED126") (pin "DO") (pinfunction "DO_DO") (pintype "output"))
      (node (ref "LED127") (pin "DI") (pinfunction "DI_DI") (pintype "input"))
    )
    (net (code "164") (name "Net-(LED127-PadDO)") (class "Default")
      (node (ref "LED127") (pin "DO") (pinfunction "DO_DO") (pintype "output"))
      (node (ref "LED128") (pin "DI") (pinfunction "DI_DI") (pintype "input"))
    )
    (net (code "165") (name "Net-(LED128-PadDO)") (class "Default")
      (node (ref "LED128") (pin "DO") (pinfunction "DO_DO") (pintype "output"))
      (node (ref "LED129") (pin "DI") (pinfunction "DI_DI") (pintype "input"))
    )
    (net (code "166") (name "Net-(LED129-PadDO)") (class "Default")
      (node (ref "LED129") (pin "DO") (pinfunction "DO_DO") (pintype "output"))
      (node (ref "LED130") (pin "DI") (pinfunction "DI_DI") (pintype "input"))
    )
    (net (code "167") (name "Net-(LED130-PadDO)") (class "Default")
      (node (ref "LED130") (pin "DO") (pinfunction "DO_DO") (pintype "output"))
      (node (ref "LED131") (pin "DI") (pinfunction "DI_DI") (pintype "input"))
    )
    (net (code "168") (name "Net-(LED131-PadDO)") (class "Default")
      (node (ref "LED131") (pin "DO") (pinfunction "DO_DO") (pintype "output"))
      (node (ref "LED132") (pin "DI") (pinfunction "DI_DI") (pintype "input"))
    )
    (net (code "169") (name "Net-(LED132-PadDO)") (class "Default")
      (node (ref "LED132") (pin "DO") (pinfunction "DO_DO") (pintype "output"))
      (node (ref "LED133") (pin "DI") (pinfunction "DI_DI") (pintype "input"))
    )
    (net (code "170") (name "Net-(LED133-PadDO)") (class "Default")
      (node (ref "LED133") (pin "DO") (pinfunction "DO_DO") (pintype "output"))
      (node (ref "LED134") (pin "DI") (pinfunction "DI_DI") (pintype "input"))
    )
    (net (code "171") (name "Net-(LED134-PadDO)") (class "Default")
      (node (ref "LED134") (pin "DO") (pinfunction "DO_DO") (pintype "output"))
      (node (ref "LED135") (pin "DI") (pinfunction "DI_DI") (pintype "input"))
    )
    (net (code "172") (name "Net-(LED135-PadDO)") (class "Default")
      (node (ref "LED135") (pin "DO") (pinfunction "DO_DO") (pintype "output"))
      (node (ref "LED136") (pin "DI") (pinfunction "DI_DI") (pintype "input"))
    )
    (net (code "173") (name "Net-(LED136-PadDO)") (class "Default")
      (node (ref "LED136") (pin "DO") (pinfunction "DO_DO") (pintype "output"))
      (node (ref "LED137") (pin "DI") (pinfunction "DI_DI") (pintype "input"))
    )
    (net (code "174") (name "Net-(LED137-PadDO)") (class "Default")
      (node (ref "LED137") (pin "DO") (pinfunction "DO_DO") (pintype "output"))
      (node (ref "LED138") (pin "DI") (pinfunction "DI_DI") (pintype "input"))
    )
    (net (code "175") (name "Net-(LED138-PadDO)") (class "Default")
      (node (ref "LED138") (pin "DO") (pinfunction "DO_DO") (pintype "output"))
      (node (ref "LED139") (pin "DI") (pinfunction "DI_DI") (pintype "input"))
    )
    (net (code "176") (name "Net-(LED139-PadDO)") (class "Default")
      (node (ref "LED139") (pin "DO") (pinfunction "DO_DO") (pintype "output"))
      (node (ref "LED140") (pin "DI") (pinfunction "DI_DI") (pintype "input"))
    )
    (net (code "177") (name "Net-(LED140-PadDO)") (class "Default")
      (node (ref "LED140") (pin "DO") (pinfunction "DO_DO") (pintype "output"))
      (node (ref "LED141") (pin "DI") (pinfunction "DI_DI") (pintype "input"))
    )
    (net (code "178") (name "Net-(LED141-PadDO)") (class "Default")
      (node (ref "LED141") (pin "DO") (pinfunction "DO_DO") (pintype "output"))
      (node (ref "LED142") (pin "DI") (pinfunction "DI_DI") (pintype "input"))
    )
    (net (code "179") (name "Net-(LED142-PadDO)") (class "Default")
      (node (ref "LED142") (pin "DO") (pinfunction "DO_DO") (pintype "output"))
      (node (ref "LED143") (pin "DI") (pinfunction "DI_DI") (pintype "input"))
    )
    (net (code "180") (name "Net-(LED143-PadDO)") (class "Default")
      (node (ref "LED143") (pin "DO") (pinfunction "DO_DO") (pintype "output"))
      (node (ref "LED144") (pin "DI") (pinfunction "DI_DI") (pintype "input"))
    )
    (net (code "181") (name "Net-(LED145-PadDO)") (class "Default")
      (node (ref "LED145") (pin "DO") (pinfunction "DO_DO") (pintype "output"))
      (node (ref "LED146") (pin "DI") (pinfunction "DI_DI") (pintype "input"))
    )
    (net (code "182") (name "Net-(LED146-PadDO)") (class "Default")
      (node (ref "LED146") (pin "DO") (pinfunction "DO_DO") (pintype "output"))
      (node (ref "LED147") (pin "DI") (pinfunction "DI_DI") (pintype "input"))
    )
    (net (code "183") (name "Net-(LED147-PadDO)") (class "Default")
      (node (ref "LED147") (pin "DO") (pinfunction "DO_DO") (pintype "output"))
      (node (ref "LED148") (pin "DI") (pinfunction "DI_DI") (pintype "input"))
    )
    (net (code "184") (name "Net-(LED148-PadDO)") (class "Default")
      (node (ref "LED148") (pin "DO") (pinfunction "DO_DO") (pintype "output"))
      (node (ref "LED149") (pin "DI") (pinfunction "DI_DI") (pintype "input"))
    )
    (net (code "185") (name "Net-(LED149-PadDO)") (class "Default")
      (node (ref "LED149") (pin "DO") (pinfunction "DO_DO") (pintype "output"))
      (node (ref "LED150") (pin "DI") (pinfunction "DI_DI") (pintype "input"))
    )
    (net (code "186") (name "Net-(LED150-PadDO)") (class "Default")
      (node (ref "LED150") (pin "DO") (pinfunction "DO_DO") (pintype "output"))
      (node (ref "LED151") (pin "DI") (pinfunction "DI_DI") (pintype "input"))
    )
    (net (code "187") (name "Net-(LED151-PadDO)") (class "Default")
      (node (ref "LED151") (pin "DO") (pinfunction "DO_DO") (pintype "output"))
      (node (ref "LED152") (pin "DI") (pinfunction "DI_DI") (pintype "input"))
    )
    (net (code "188") (name "Net-(LED152-PadDO)") (class "Default")
      (node (ref "LED152") (pin "DO") (pinfunction "DO_DO") (pintype "output"))
      (node (ref "LED153") (pin "DI") (pinfunction "DI_DI") (pintype "input"))
    )
    (net (code "189") (name "Net-(LED153-PadDO)") (class "Default")
      (node (ref "LED153") (pin "DO") (pinfunction "DO_DO") (pintype "output"))
      (node (ref "LED154") (pin "DI") (pinfunction "DI_DI") (pintype "input"))
    )
    (net (code "190") (name "Net-(LED154-PadDO)") (class "Default")
      (node (ref "LED154") (pin "DO") (pinfunction "DO_DO") (pintype "output"))
      (node (ref "LED155") (pin "DI") (pinfunction "DI_DI") (pintype "input"))
    )
    (net (code "191") (name "Net-(LED155-PadDO)") (class "Default")
      (node (ref "LED155") (pin "DO") (pinfunction "DO_DO") (pintype "output"))
      (node (ref "LED156") (pin "DI") (pinfunction "DI_DI") (pintype "input"))
    )
    (net (code "192") (name "Net-(LED156-PadDO)") (class "Default")
      (node (ref "LED156") (pin "DO") (pinfunction "DO_DO") (pintype "output"))
      (node (ref "LED157") (pin "DI") (pinfunction "DI_DI") (pintype "input"))
    )
    (net (code "193") (name "Net-(LED157-PadDO)") (class "Default")
      (node (ref "LED157") (pin "DO") (pinfunction "DO_DO") (pintype "output"))
      (node (ref "LED158") (pin "DI") (pinfunction "DI_DI") (pintype "input"))
    )
    (net (code "194") (name "Net-(LED158-PadDO)") (class "Default")
      (node (ref "LED158") (pin "DO") (pinfunction "DO_DO") (pintype "output"))
      (node (ref "LED159") (pin "DI") (pinfunction "DI_DI") (pintype "input"))
    )
    (net (code "195") (name "Net-(LED159-PadDO)") (class "Default")
      (node (ref "LED159") (pin "DO") (pinfunction "DO_DO") (pintype "output"))
      (node (ref "LED160") (pin "DI") (pinfunction "DI_DI") (pintype "input"))
    )
    (net (code "196") (name "Net-(LED160-PadDO)") (class "Default")
      (node (ref "LED160") (pin "DO") (pinfunction "DO_DO") (pintype "output"))
      (node (ref "LED161") (pin "DI") (pinfunction "DI_DI") (pintype "input"))
    )
    (net (code "197") (name "Net-(LED161-PadDO)") (class "Default")
      (node (ref "LED161") (pin "DO") (pinfunction "DO_DO") (pintype "output"))
      (node (ref "LED162") (pin "DI") (pinfunction "DI_DI") (pintype "input"))
    )
    (net (code "198") (name "Net-(LED162-PadDO)") (class "Default")
      (node (ref "LED162") (pin "DO") (pinfunction "DO_DO") (pintype "output"))
      (node (ref "LED163") (pin "DI") (pinfunction "DI_DI") (pintype "input"))
    )
    (net (code "199") (name "Net-(LED163-PadDO)") (class "Default")
      (node (ref "LED163") (pin "DO") (pinfunction "DO_DO") (pintype "output"))
      (node (ref "LED164") (pin "DI") (pinfunction "DI_DI") (pintype "input"))
    )
    (net (code "200") (name "Net-(LED164-PadDO)") (class "Default")
      (node (ref "LED164") (pin "DO") (pinfunction "DO_DO") (pintype "output"))
      (node (ref "LED165") (pin "DI") (pinfunction "DI_DI") (pintype "input"))
    )
    (net (code "201") (name "Net-(LED165-PadDO)") (class "Default")
      (node (ref "LED165") (pin "DO") (pinfunction "DO_DO") (pintype "output"))
      (node (ref "LED166") (pin "DI") (pinfunction "DI_DI") (pintype "input"))
    )
    (net (code "202") (name "Net-(LED166-PadDO)") (class "Default")
      (node (ref "LED166") (pin "DO") (pinfunction "DO_DO") (pintype "output"))
      (node (ref "LED167") (pin "DI") (pinfunction "DI_DI") (pintype "input"))
    )
    (net (code "203") (name "Net-(LED167-PadDO)") (class "Default")
      (node (ref "LED167") (pin "DO") (pinfunction "DO_DO") (pintype "output"))
      (node (ref "LED168") (pin "DI") (pinfunction "DI_DI") (pintype "input"))
    )
    (net (code "204") (name "Net-(LED168-PadDO)") (class "Default")
      (node (ref "LED168") (pin "DO") (pinfunction "DO_DO") (pintype "output"))
      (node (ref "LED169") (pin "DI") (pinfunction "DI_DI") (pintype "input"))
    )
    (net (code "205") (name "Net-(LED169-PadDO)") (class "Default")
      (node (ref "LED169") (pin "DO") (pinfunction "DO_DO") (pintype "output"))
      (node (ref "LED170") (pin "DI") (pinfunction "DI_DI") (pintype "input"))
    )
    (net (code "206") (name "Net-(LED170-PadDO)") (class "Default")
      (node (ref "LED170") (pin "DO") (pinfunction "DO_DO") (pintype "output"))
      (node (ref "LED171") (pin "DI") (pinfunction "DI_DI") (pintype "input"))
    )
    (net (code "207") (name "Net-(LED171-PadDO)") (class "Default")
      (node (ref "LED171") (pin "DO") (pinfunction "DO_DO") (pintype "output"))
      (node (ref "LED172") (pin "DI") (pinfunction "DI_DI") (pintype "input"))
    )
    (net (code "208") (name "Net-(LED172-PadDO)") (class "Default")
      (node (ref "LED172") (pin "DO") (pinfunction "DO_DO") (pintype "output"))
      (node (ref "LED173") (pin "DI") (pinfunction "DI_DI") (pintype "input"))
    )
    (net (code "209") (name "Net-(LED173-PadDO)") (class "Default")
      (node (ref "LED173") (pin "DO") (pinfunction "DO_DO") (pintype "output"))
      (node (ref "LED174") (pin "DI") (pinfunction "DI_DI") (pintype "input"))
    )
    (net (code "210") (name "Net-(LED174-PadDO)") (class "Default")
      (node (ref "LED174") (pin "DO") (pinfunction "DO_DO") (pintype "output"))
      (node (ref "LED175") (pin "DI") (pinfunction "DI_DI") (pintype "input"))
    )
    (net (code "211") (name "Net-(LED175-PadDO)") (class "Default")
      (node (ref "LED175") (pin "DO") (pinfunction "DO_DO") (pintype "output"))
      (node (ref "LED176") (pin "DI") (pinfunction "DI_DI") (pintype "input"))
    )
    (net (code "212") (name "Net-(LED176-PadDO)") (class "Default")
      (node (ref "LED176") (pin "DO") (pinfunction "DO_DO") (pintype "output"))
      (node (ref "LED177") (pin "DI") (pinfunction "DI_DI") (pintype "input"))
    )
    (net (code "213") (name "Net-(LED177-PadDO)") (class "Default")
      (node (ref "LED177") (pin "DO") (pinfunction "DO_DO") (pintype "output"))
      (node (ref "LED178") (pin "DI") (pinfunction "DI_DI") (pintype "input"))
    )
    (net (code "214") (name "Net-(LED178-PadDO)") (class "Default")
      (node (ref "LED178") (pin "DO") (pinfunction "DO_DO") (pintype "output"))
      (node (ref "LED179") (pin "DI") (pinfunction "DI_DI") (pintype "input"))
    )
    (net (code "215") (name "Net-(LED179-PadDO)") (class "Default")
      (node (ref "LED179") (pin "DO") (pinfunction "DO_DO") (pintype "output"))
      (node (ref "LED180") (pin "DI") (pinfunction "DI_DI") (pintype "input"))
    )
    (net (code "216") (name "Net-(LED180-PadDO)") (class "Default")
      (node (ref "LED180") (pin "DO") (pinfunction "DO_DO") (pintype "output"))
      (node (ref "LED181") (pin "DI") (pinfunction "DI_DI") (pintype "input"))
    )
    (net (code "217") (name "Net-(LED181-PadDO)") (class "Default")
      (node (ref "LED181") (pin "DO") (pinfunction "DO_DO") (pintype "output"))
      (node (ref "LED182") (pin "DI") (pinfunction "DI_DI") (pintype "input"))
    )
    (net (code "218") (name "Net-(LED182-PadDO)") (class "Default")
      (node (ref "LED182") (pin "DO") (pinfunction "DO_DO") (pintype "output"))
      (node (ref "LED183") (pin "DI") (pinfunction "DI_DI") (pintype "input"))
    )
    (net (code "219") (name "Net-(LED183-PadDO)") (class "Default")
      (node (ref "LED183") (pin "DO") (pinfunction "DO_DO") (pintype "output"))
      (node (ref "LED184") (pin "DI") (pinfunction "DI_DI") (pintype "input"))
    )
    (net (code "220") (name "Net-(LED184-PadDO)") (class "Default")
      (node (ref "LED184") (pin "DO") (pinfunction "DO_DO") (pintype "output"))
      (node (ref "LED185") (pin "DI") (pinfunction "DI_DI") (pintype "input"))
    )
    (net (code "221") (name "Net-(LED185-PadDO)") (class "Default")
      (node (ref "LED185") (pin "DO") (pinfunction "DO_DO") (pintype "output"))
      (node (ref "LED186") (pin "DI") (pinfunction "DI_DI") (pintype "input"))
    )
    (net (code "222") (name "Net-(LED186-PadDO)") (class "Default")
      (node (ref "LED186") (pin "DO") (pinfunction "DO_DO") (pintype "output"))
      (node (ref "LED187") (pin "DI") (pinfunction "DI_DI") (pintype "input"))
    )
    (net (code "223") (name "Net-(LED187-PadDO)") (class "Default")
      (node (ref "LED187") (pin "DO") (pinfunction "DO_DO") (pintype "output"))
      (node (ref "LED188") (pin "DI") (pinfunction "DI_DI") (pintype "input"))
    )
    (net (code "224") (name "Net-(LED188-PadDO)") (class "Default")
      (node (ref "LED188") (pin "DO") (pinfunction "DO_DO") (pintype "output"))
      (node (ref "LED189") (pin "DI") (pinfunction "DI_DI") (pintype "input"))
    )
    (net (code "225") (name "Net-(LED189-PadDO)") (class "Default")
      (node (ref "LED189") (pin "DO") (pinfunction "DO_DO") (pintype "output"))
      (node (ref "LED190") (pin "DI") (pinfunction "DI_DI") (pintype "input"))
    )
    (net (code "226") (name "Net-(LED190-PadDO)") (class "Default")
      (node (ref "LED190") (pin "DO") (pinfunction "DO_DO") (pintype "output"))
      (node (ref "LED191") (pin "DI") (pinfunction "DI_DI") (pintype "input"))
    )
    (net (code "227") (name "Net-(LED191-PadDO)") (class "Default")
      (node (ref "LED191") (pin "DO") (pinfunction "DO_DO") (pintype "output"))
      (node (ref "LED192") (pin "DI") (pinfunction "DI_DI") (pintype "input"))
    )
    (net (code "228") (name "Net-(LED192-PadDO)") (class "Default")
      (node (ref "LED192") (pin "DO") (pinfunction "DO_DO") (pintype "output"))
      (node (ref "LED193") (pin "DI") (pinfunction "DI_DI") (pintype "input"))
    )
    (net (code "229") (name "Net-(LED193-PadDO)") (class "Default")
      (node (ref "LED193") (pin "DO") (pinfunction "DO_DO") (pintype "output"))
      (node (ref "LED194") (pin "DI") (pinfunction "DI_DI") (pintype "input"))
    )
    (net (code "230") (name "Net-(LED194-PadDO)") (class "Default")
      (node (ref "LED194") (pin "DO") (pinfunction "DO_DO") (pintype "output"))
      (node (ref "LED195") (pin "DI") (pinfunction "DI_DI") (pintype "input"))
    )
    (net (code "231") (name "Net-(LED195-PadDO)") (class "Default")
      (node (ref "LED195") (pin "DO") (pinfunction "DO_DO") (pintype "output"))
      (node (ref "LED196") (pin "DI") (pinfunction "DI_DI") (pintype "input"))
    )
    (net (code "232") (name "Net-(LED196-PadDO)") (class "Default")
      (node (ref "LED196") (pin "DO") (pinfunction "DO_DO") (pintype "output"))
      (node (ref "LED197") (pin "DI") (pinfunction "DI_DI") (pintype "input"))
    )
    (net (code "233") (name "Net-(LED197-PadDO)") (class "Default")
      (node (ref "LED197") (pin "DO") (pinfunction "DO_DO") (pintype "output"))
      (node (ref "LED198") (pin "DI") (pinfunction "DI_DI") (pintype "input"))
    )
    (net (code "234") (name "Net-(LED198-PadDO)") (class "Default")
      (node (ref "LED198") (pin "DO") (pinfunction "DO_DO") (pintype "output"))
      (node (ref "LED199") (pin "DI") (pinfunction "DI_DI") (pintype "input"))
    )
    (net (code "235") (name "Net-(LED199-PadDO)") (class "Default")
      (node (ref "LED199") (pin "DO") (pinfunction "DO_DO") (pintype "output"))
      (node (ref "LED200") (pin "DI") (pinfunction "DI_DI") (pintype "input"))
    )
    (net (code "236") (name "Net-(LED200-PadDO)") (class "Default")
      (node (ref "LED200") (pin "DO") (pinfunction "DO_DO") (pintype "output"))
      (node (ref "LED201") (pin "DI") (pinfunction "DI_DI") (pintype "input"))
    )
    (net (code "237") (name "Net-(LED201-PadDO)") (class "Default")
      (node (ref "LED201") (pin "DO") (pinfunction "DO_DO") (pintype "output"))
      (node (ref "LED202") (pin "DI") (pinfunction "DI_DI") (pintype "input"))
    )
    (net (code "238") (name "Net-(LED202-PadDO)") (class "Default")
      (node (ref "LED202") (pin "DO") (pinfunction "DO_DO") (pintype "output"))
      (node (ref "LED203") (pin "DI") (pinfunction "DI_DI") (pintype "input"))
    )
    (net (code "239") (name "Net-(LED203-PadDO)") (class "Default")
      (node (ref "LED203") (pin "DO") (pinfunction "DO_DO") (pintype "output"))
      (node (ref "LED204") (pin "DI") (pinfunction "DI_DI") (pintype "input"))
    )
    (net (code "240") (name "Net-(LED204-PadDO)") (class "Default")
      (node (ref "LED204") (pin "DO") (pinfunction "DO_DO") (pintype "output"))
      (node (ref "LED205") (pin "DI") (pinfunction "DI_DI") (pintype "input"))
    )
    (net (code "241") (name "Net-(LED205-PadDO)") (class "Default")
      (node (ref "LED205") (pin "DO") (pinfunction "DO_DO") (pintype "output"))
      (node (ref "LED206") (pin "DI") (pinfunction "DI_DI") (pintype "input"))
    )
    (net (code "242") (name "Net-(LED206-PadDO)") (class "Default")
      (node (ref "LED206") (pin "DO") (pinfunction "DO_DO") (pintype "output"))
      (node (ref "LED207") (pin "DI") (pinfunction "DI_DI") (pintype "input"))
    )
    (net (code "243") (name "Net-(LED207-PadDO)") (class "Default")
      (node (ref "LED207") (pin "DO") (pinfunction "DO_DO") (pintype "output"))
      (node (ref "LED208") (pin "DI") (pinfunction "DI_DI") (pintype "input"))
    )
    (net (code "244") (name "Net-(LED208-PadDO)") (class "Default")
      (node (ref "LED208") (pin "DO") (pinfunction "DO_DO") (pintype "output"))
      (node (ref "LED209") (pin "DI") (pinfunction "DI_DI") (pintype "input"))
    )
    (net (code "245") (name "Net-(LED209-PadDO)") (class "Default")
      (node (ref "LED209") (pin "DO") (pinfunction "DO_DO") (pintype "output"))
      (node (ref "LED210") (pin "DI") (pinfunction "DI_DI") (pintype "input"))
    )
    (net (code "246") (name "Net-(LED210-PadDO)") (class "Default")
      (node (ref "LED210") (pin "DO") (pinfunction "DO_DO") (pintype "output"))
      (node (ref "LED211") (pin "DI") (pinfunction "DI_DI") (pintype "input"))
    )
    (net (code "247") (name "Net-(LED211-PadDO)") (class "Default")
      (node (ref "LED211") (pin "DO") (pinfunction "DO_DO") (pintype "output"))
      (node (ref "LED212") (pin "DI") (pinfunction "DI_DI") (pintype "input"))
    )
    (net (code "248") (name "Net-(LED212-PadDO)") (class "Default")
      (node (ref "LED212") (pin "DO") (pinfunction "DO_DO") (pintype "output"))
      (node (ref "LED213") (pin "DI") (pinfunction "DI_DI") (pintype "input"))
    )
    (net (code "249") (name "Net-(LED213-PadDO)") (class "Default")
      (node (ref "LED213") (pin "DO") (pinfunction "DO_DO") (pintype "output"))
      (node (ref "LED214") (pin "DI") (pinfunction "DI_DI") (pintype "input"))
    )
    (net (code "250") (name "Net-(LED214-PadDO)") (class "Default")
      (node (ref "LED214") (pin "DO") (pinfunction "DO_DO") (pintype "output"))
      (node (ref "LED215") (pin "DI") (pinfunction "DI_DI") (pintype "input"))
    )
    (net (code "251") (name "Net-(LED215-PadDO)") (class "Default")
      (node (ref "LED215") (pin "DO") (pinfunction "DO_DO") (pintype "output"))
      (node (ref "LED216") (pin "DI") (pinfunction "DI_DI") (pintype "input"))
    )
    (net (code "252") (name "Net-(LED217-PadDO)") (class "Default")
      (node (ref "LED217") (pin "DO") (pinfunction "DO_DO") (pintype "output"))
      (node (ref "LED218") (pin "DI") (pinfunction "DI_DI") (pintype "input"))
    )
    (net (code "253") (name "Net-(LED218-PadDO)") (class "Default")
      (node (ref "LED218") (pin "DO") (pinfunction "DO_DO") (pintype "output"))
      (node (ref "LED219") (pin "DI") (pinfunction "DI_DI") (pintype "input"))
    )
    (net (code "254") (name "Net-(LED219-PadDO)") (class "Default")
      (node (ref "LED219") (pin "DO") (pinfunction "DO_DO") (pintype "output"))
      (node (ref "LED220") (pin "DI") (pinfunction "DI_DI") (pintype "input"))
    )
    (net (code "255") (name "Net-(LED220-PadDO)") (class "Default")
      (node (ref "LED220") (pin "DO") (pinfunction "DO_DO") (pintype "output"))
      (node (ref "LED221") (pin "DI") (pinfunction "DI_DI") (pintype "input"))
    )
    (net (code "256") (name "Net-(LED221-PadDO)") (class "Default")
      (node (ref "LED221") (pin "DO") (pinfunction "DO_DO") (pintype "output"))
      (node (ref "LED222") (pin "DI") (pinfunction "DI_DI") (pintype "input"))
    )
    (net (code "257") (name "Net-(LED222-PadDO)") (class "Default")
      (node (ref "LED222") (pin "DO") (pinfunction "DO_DO") (pintype "output"))
      (node (ref "LED223") (pin "DI") (pinfunction "DI_DI") (pintype "input"))
    )
    (net (code "258") (name "Net-(LED223-PadDO)") (class "Default")
      (node (ref "LED223") (pin "DO") (pinfunction "DO_DO") (pintype "output"))
      (node (ref "LED224") (pin "DI") (pinfunction "DI_DI") (pintype "input"))
    )
    (net (code "259") (name "Net-(LED224-PadDO)") (class "Default")
      (node (ref "LED224") (pin "DO") (pinfunction "DO_DO") (pintype "output"))
      (node (ref "LED225") (pin "DI") (pinfunction "DI_DI") (pintype "input"))
    )
    (net (code "260") (name "Net-(LED225-PadDO)") (class "Default")
      (node (ref "LED225") (pin "DO") (pinfunction "DO_DO") (pintype "output"))
      (node (ref "LED226") (pin "DI") (pinfunction "DI_DI") (pintype "input"))
    )
    (net (code "261") (name "Net-(LED226-PadDO)") (class "Default")
      (node (ref "LED226") (pin "DO") (pinfunction "DO_DO") (pintype "output"))
      (node (ref "LED227") (pin "DI") (pinfunction "DI_DI") (pintype "input"))
    )
    (net (code "262") (name "Net-(LED227-PadDO)") (class "Default")
      (node (ref "LED227") (pin "DO") (pinfunction "DO_DO") (pintype "output"))
      (node (ref "LED228") (pin "DI") (pinfunction "DI_DI") (pintype "input"))
    )
    (net (code "263") (name "Net-(LED228-PadDO)") (class "Default")
      (node (ref "LED228") (pin "DO") (pinfunction "DO_DO") (pintype "output"))
      (node (ref "LED229") (pin "DI") (pinfunction "DI_DI") (pintype "input"))
    )
    (net (code "264") (name "Net-(LED229-PadDO)") (class "Default")
      (node (ref "LED229") (pin "DO") (pinfunction "DO_DO") (pintype "output"))
      (node (ref "LED230") (pin "DI") (pinfunction "DI_DI") (pintype "input"))
    )
    (net (code "265") (name "Net-(LED230-PadDO)") (class "Default")
      (node (ref "LED230") (pin "DO") (pinfunction "DO_DO") (pintype "output"))
      (node (ref "LED231") (pin "DI") (pinfunction "DI_DI") (pintype "input"))
    )
    (net (code "266") (name "Net-(LED231-PadDO)") (class "Default")
      (node (ref "LED231") (pin "DO") (pinfunction "DO_DO") (pintype "output"))
      (node (ref "LED232") (pin "DI") (pinfunction "DI_DI") (pintype "input"))
    )
    (net (code "267") (name "Net-(LED232-PadDO)") (class "Default")
      (node (ref "LED232") (pin "DO") (pinfunction "DO_DO") (pintype "output"))
      (node (ref "LED233") (pin "DI") (pinfunction "DI_DI") (pintype "input"))
    )
    (net (code "268") (name "Net-(LED233-PadDO)") (class "Default")
      (node (ref "LED233") (pin "DO") (pinfunction "DO_DO") (pintype "output"))
      (node (ref "LED234") (pin "DI") (pinfunction "DI_DI") (pintype "input"))
    )
    (net (code "269") (name "Net-(LED234-PadDO)") (class "Default")
      (node (ref "LED234") (pin "DO") (pinfunction "DO_DO") (pintype "output"))
      (node (ref "LED235") (pin "DI") (pinfunction "DI_DI") (pintype "input"))
    )
    (net (code "270") (name "Net-(LED235-PadDO)") (class "Default")
      (node (ref "LED235") (pin "DO") (pinfunction "DO_DO") (pintype "output"))
      (node (ref "LED236") (pin "DI") (pinfunction "DI_DI") (pintype "input"))
    )
    (net (code "271") (name "Net-(LED236-PadDO)") (class "Default")
      (node (ref "LED236") (pin "DO") (pinfunction "DO_DO") (pintype "output"))
      (node (ref "LED237") (pin "DI") (pinfunction "DI_DI") (pintype "input"))
    )
    (net (code "272") (name "Net-(LED237-PadDO)") (class "Default")
      (node (ref "LED237") (pin "DO") (pinfunction "DO_DO") (pintype "output"))
      (node (ref "LED238") (pin "DI") (pinfunction "DI_DI") (pintype "input"))
    )
    (net (code "273") (name "Net-(LED238-PadDO)") (class "Default")
      (node (ref "LED238") (pin "DO") (pinfunction "DO_DO") (pintype "output"))
      (node (ref "LED239") (pin "DI") (pinfunction "DI_DI") (pintype "input"))
    )
    (net (code "274") (name "Net-(LED239-PadDO)") (class "Default")
      (node (ref "LED239") (pin "DO") (pinfunction "DO_DO") (pintype "output"))
      (node (ref "LED240") (pin "DI") (pinfunction "DI_DI") (pintype "input"))
    )
    (net (code "275") (name "Net-(LED240-PadDO)") (class "Default")
      (node (ref "LED240") (pin "DO") (pinfunction "DO_DO") (pintype "output"))
      (node (ref "LED241") (pin "DI") (pinfunction "DI_DI") (pintype "input"))
    )
    (net (code "276") (name "Net-(LED241-PadDO)") (class "Default")
      (node (ref "LED241") (pin "DO") (pinfunction "DO_DO") (pintype "output"))
      (node (ref "LED242") (pin "DI") (pinfunction "DI_DI") (pintype "input"))
    )
    (net (code "277") (name "Net-(LED242-PadDO)") (class "Default")
      (node (ref "LED242") (pin "DO") (pinfunction "DO_DO") (pintype "output"))
      (node (ref "LED243") (pin "DI") (pinfunction "DI_DI") (pintype "input"))
    )
    (net (code "278") (name "Net-(LED243-PadDO)") (class "Default")
      (node (ref "LED243") (pin "DO") (pinfunction "DO_DO") (pintype "output"))
      (node (ref "LED244") (pin "DI") (pinfunction "DI_DI") (pintype "input"))
    )
    (net (code "279") (name "Net-(LED244-PadDO)") (class "Default")
      (node (ref "LED244") (pin "DO") (pinfunction "DO_DO") (pintype "output"))
      (node (ref "LED245") (pin "DI") (pinfunction "DI_DI") (pintype "input"))
    )
    (net (code "280") (name "Net-(LED245-PadDO)") (class "Default")
      (node (ref "LED245") (pin "DO") (pinfunction "DO_DO") (pintype "output"))
      (node (ref "LED246") (pin "DI") (pinfunction "DI_DI") (pintype "input"))
    )
    (net (code "281") (name "Net-(LED246-PadDO)") (class "Default")
      (node (ref "LED246") (pin "DO") (pinfunction "DO_DO") (pintype "output"))
      (node (ref "LED247") (pin "DI") (pinfunction "DI_DI") (pintype "input"))
    )
    (net (code "282") (name "Net-(LED247-PadDO)") (class "Default")
      (node (ref "LED247") (pin "DO") (pinfunction "DO_DO") (pintype "output"))
      (node (ref "LED248") (pin "DI") (pinfunction "DI_DI") (pintype "input"))
    )
    (net (code "283") (name "Net-(LED248-PadDO)") (class "Default")
      (node (ref "LED248") (pin "DO") (pinfunction "DO_DO") (pintype "output"))
      (node (ref "LED249") (pin "DI") (pinfunction "DI_DI") (pintype "input"))
    )
    (net (code "284") (name "Net-(LED249-PadDO)") (class "Default")
      (node (ref "LED249") (pin "DO") (pinfunction "DO_DO") (pintype "output"))
      (node (ref "LED250") (pin "DI") (pinfunction "DI_DI") (pintype "input"))
    )
    (net (code "285") (name "Net-(LED250-PadDO)") (class "Default")
      (node (ref "LED250") (pin "DO") (pinfunction "DO_DO") (pintype "output"))
      (node (ref "LED251") (pin "DI") (pinfunction "DI_DI") (pintype "input"))
    )
    (net (code "286") (name "Net-(LED251-PadDO)") (class "Default")
      (node (ref "LED251") (pin "DO") (pinfunction "DO_DO") (pintype "output"))
      (node (ref "LED252") (pin "DI") (pinfunction "DI_DI") (pintype "input"))
    )
    (net (code "287") (name "Net-(LED252-PadDO)") (class "Default")
      (node (ref "LED252") (pin "DO") (pinfunction "DO_DO") (pintype "output"))
      (node (ref "LED253") (pin "DI") (pinfunction "DI_DI") (pintype "input"))
    )
    (net (code "288") (name "Net-(LED253-PadDO)") (class "Default")
      (node (ref "LED253") (pin "DO") (pinfunction "DO_DO") (pintype "output"))
      (node (ref "LED254") (pin "DI") (pinfunction "DI_DI") (pintype "input"))
    )
    (net (code "289") (name "Net-(LED254-PadDO)") (class "Default")
      (node (ref "LED254") (pin "DO") (pinfunction "DO_DO") (pintype "output"))
      (node (ref "LED255") (pin "DI") (pinfunction "DI_DI") (pintype "input"))
    )
    (net (code "290") (name "Net-(LED255-PadDO)") (class "Default")
      (node (ref "LED255") (pin "DO") (pinfunction "DO_DO") (pintype "output"))
      (node (ref "LED256") (pin "DI") (pinfunction "DI_DI") (pintype "input"))
    )
    (net (code "291") (name "Net-(LED256-PadDO)") (class "Default")
      (node (ref "LED256") (pin "DO") (pinfunction "DO_DO") (pintype "output"))
      (node (ref "LED257") (pin "DI") (pinfunction "DI_DI") (pintype "input"))
    )
    (net (code "292") (name "Net-(LED257-PadDO)") (class "Default")
      (node (ref "LED257") (pin "DO") (pinfunction "DO_DO") (pintype "output"))
      (node (ref "LED258") (pin "DI") (pinfunction "DI_DI") (pintype "input"))
    )
    (net (code "293") (name "Net-(LED258-PadDO)") (class "Default")
      (node (ref "LED258") (pin "DO") (pinfunction "DO_DO") (pintype "output"))
      (node (ref "LED259") (pin "DI") (pinfunction "DI_DI") (pintype "input"))
    )
    (net (code "294") (name "Net-(LED259-PadDO)") (class "Default")
      (node (ref "LED259") (pin "DO") (pinfunction "DO_DO") (pintype "output"))
      (node (ref "LED260") (pin "DI") (pinfunction "DI_DI") (pintype "input"))
    )
    (net (code "295") (name "Net-(LED260-PadDO)") (class "Default")
      (node (ref "LED260") (pin "DO") (pinfunction "DO_DO") (pintype "output"))
      (node (ref "LED261") (pin "DI") (pinfunction "DI_DI") (pintype "input"))
    )
    (net (code "296") (name "Net-(LED261-PadDO)") (class "Default")
      (node (ref "LED261") (pin "DO") (pinfunction "DO_DO") (pintype "output"))
      (node (ref "LED262") (pin "DI") (pinfunction "DI_DI") (pintype "input"))
    )
    (net (code "297") (name "Net-(LED262-PadDO)") (class "Default")
      (node (ref "LED262") (pin "DO") (pinfunction "DO_DO") (pintype "output"))
      (node (ref "LED263") (pin "DI") (pinfunction "DI_DI") (pintype "input"))
    )
    (net (code "298") (name "Net-(LED263-PadDO)") (class "Default")
      (node (ref "LED263") (pin "DO") (pinfunction "DO_DO") (pintype "output"))
      (node (ref "LED264") (pin "DI") (pinfunction "DI_DI") (pintype "input"))
    )
    (net (code "299") (name "Net-(LED264-PadDO)") (class "Default")
      (node (ref "LED264") (pin "DO") (pinfunction "DO_DO") (pintype "output"))
      (node (ref "LED265") (pin "DI") (pinfunction "DI_DI") (pintype "input"))
    )
    (net (code "300") (name "Net-(LED265-PadDO)") (class "Default")
      (node (ref "LED265") (pin "DO") (pinfunction "DO_DO") (pintype "output"))
      (node (ref "LED266") (pin "DI") (pinfunction "DI_DI") (pintype "input"))
    )
    (net (code "301") (name "Net-(LED266-PadDO)") (class "Default")
      (node (ref "LED266") (pin "DO") (pinfunction "DO_DO") (pintype "output"))
      (node (ref "LED267") (pin "DI") (pinfunction "DI_DI") (pintype "input"))
    )
    (net (code "302") (name "Net-(LED267-PadDO)") (class "Default")
      (node (ref "LED267") (pin "DO") (pinfunction "DO_DO") (pintype "output"))
      (node (ref "LED268") (pin "DI") (pinfunction "DI_DI") (pintype "input"))
    )
    (net (code "303") (name "Net-(LED268-PadDO)") (class "Default")
      (node (ref "LED268") (pin "DO") (pinfunction "DO_DO") (pintype "output"))
      (node (ref "LED269") (pin "DI") (pinfunction "DI_DI") (pintype "input"))
    )
    (net (code "304") (name "Net-(LED269-PadDO)") (class "Default")
      (node (ref "LED269") (pin "DO") (pinfunction "DO_DO") (pintype "output"))
      (node (ref "LED270") (pin "DI") (pinfunction "DI_DI") (pintype "input"))
    )
    (net (code "305") (name "Net-(LED270-PadDO)") (class "Default")
      (node (ref "LED270") (pin "DO") (pinfunction "DO_DO") (pintype "output"))
      (node (ref "LED271") (pin "DI") (pinfunction "DI_DI") (pintype "input"))
    )
    (net (code "306") (name "Net-(LED271-PadDO)") (class "Default")
      (node (ref "LED271") (pin "DO") (pinfunction "DO_DO") (pintype "output"))
      (node (ref "LED272") (pin "DI") (pinfunction "DI_DI") (pintype "input"))
    )
    (net (code "307") (name "Net-(LED272-PadDO)") (class "Default")
      (node (ref "LED272") (pin "DO") (pinfunction "DO_DO") (pintype "output"))
      (node (ref "LED273") (pin "DI") (pinfunction "DI_DI") (pintype "input"))
    )
    (net (code "308") (name "Net-(LED273-PadDO)") (class "Default")
      (node (ref "LED273") (pin "DO") (pinfunction "DO_DO") (pintype "output"))
      (node (ref "LED274") (pin "DI") (pinfunction "DI_DI") (pintype "input"))
    )
    (net (code "309") (name "Net-(LED274-PadDO)") (class "Default")
      (node (ref "LED274") (pin "DO") (pinfunction "DO_DO") (pintype "output"))
      (node (ref "LED275") (pin "DI") (pinfunction "DI_DI") (pintype "input"))
    )
    (net (code "310") (name "Net-(LED275-PadDO)") (class "Default")
      (node (ref "LED275") (pin "DO") (pinfunction "DO_DO") (pintype "output"))
      (node (ref "LED276") (pin "DI") (pinfunction "DI_DI") (pintype "input"))
    )
    (net (code "311") (name "Net-(LED276-PadDO)") (class "Default")
      (node (ref "LED276") (pin "DO") (pinfunction "DO_DO") (pintype "output"))
      (node (ref "LED277") (pin "DI") (pinfunction "DI_DI") (pintype "input"))
    )
    (net (code "312") (name "Net-(LED277-PadDO)") (class "Default")
      (node (ref "LED277") (pin "DO") (pinfunction "DO_DO") (pintype "output"))
      (node (ref "LED278") (pin "DI") (pinfunction "DI_DI") (pintype "input"))
    )
    (net (code "313") (name "Net-(LED278-PadDO)") (class "Default")
      (node (ref "LED278") (pin "DO") (pinfunction "DO_DO") (pintype "output"))
      (node (ref "LED279") (pin "DI") (pinfunction "DI_DI") (pintype "input"))
    )
    (net (code "314") (name "Net-(LED279-PadDO)") (class "Default")
      (node (ref "LED279") (pin "DO") (pinfunction "DO_DO") (pintype "output"))
      (node (ref "LED280") (pin "DI") (pinfunction "DI_DI") (pintype "input"))
    )
    (net (code "315") (name "Net-(LED280-PadDO)") (class "Default")
      (node (ref "LED280") (pin "DO") (pinfunction "DO_DO") (pintype "output"))
      (node (ref "LED281") (pin "DI") (pinfunction "DI_DI") (pintype "input"))
    )
    (net (code "316") (name "Net-(LED281-PadDO)") (class "Default")
      (node (ref "LED281") (pin "DO") (pinfunction "DO_DO") (pintype "output"))
      (node (ref "LED282") (pin "DI") (pinfunction "DI_DI") (pintype "input"))
    )
    (net (code "317") (name "Net-(LED282-PadDO)") (class "Default")
      (node (ref "LED282") (pin "DO") (pinfunction "DO_DO") (pintype "output"))
      (node (ref "LED283") (pin "DI") (pinfunction "DI_DI") (pintype "input"))
    )
    (net (code "318") (name "Net-(LED283-PadDO)") (class "Default")
      (node (ref "LED283") (pin "DO") (pinfunction "DO_DO") (pintype "output"))
      (node (ref "LED284") (pin "DI") (pinfunction "DI_DI") (pintype "input"))
    )
    (net (code "319") (name "Net-(LED284-PadDO)") (class "Default")
      (node (ref "LED284") (pin "DO") (pinfunction "DO_DO") (pintype "output"))
      (node (ref "LED285") (pin "DI") (pinfunction "DI_DI") (pintype "input"))
    )
    (net (code "320") (name "Net-(LED285-PadDO)") (class "Default")
      (node (ref "LED285") (pin "DO") (pinfunction "DO_DO") (pintype "output"))
      (node (ref "LED286") (pin "DI") (pinfunction "DI_DI") (pintype "input"))
    )
    (net (code "321") (name "Net-(LED286-PadDO)") (class "Default")
      (node (ref "LED286") (pin "DO") (pinfunction "DO_DO") (pintype "output"))
      (node (ref "LED287") (pin "DI") (pinfunction "DI_DI") (pintype "input"))
    )
    (net (code "322") (name "Net-(LED287-PadDO)") (class "Default")
      (node (ref "LED287") (pin "DO") (pinfunction "DO_DO") (pintype "output"))
      (node (ref "LED288") (pin "DI") (pinfunction "DI_DI") (pintype "input"))
    )
  )
)
